# untitled.net
KiCad netlist of a schematic drawn in EAGLE
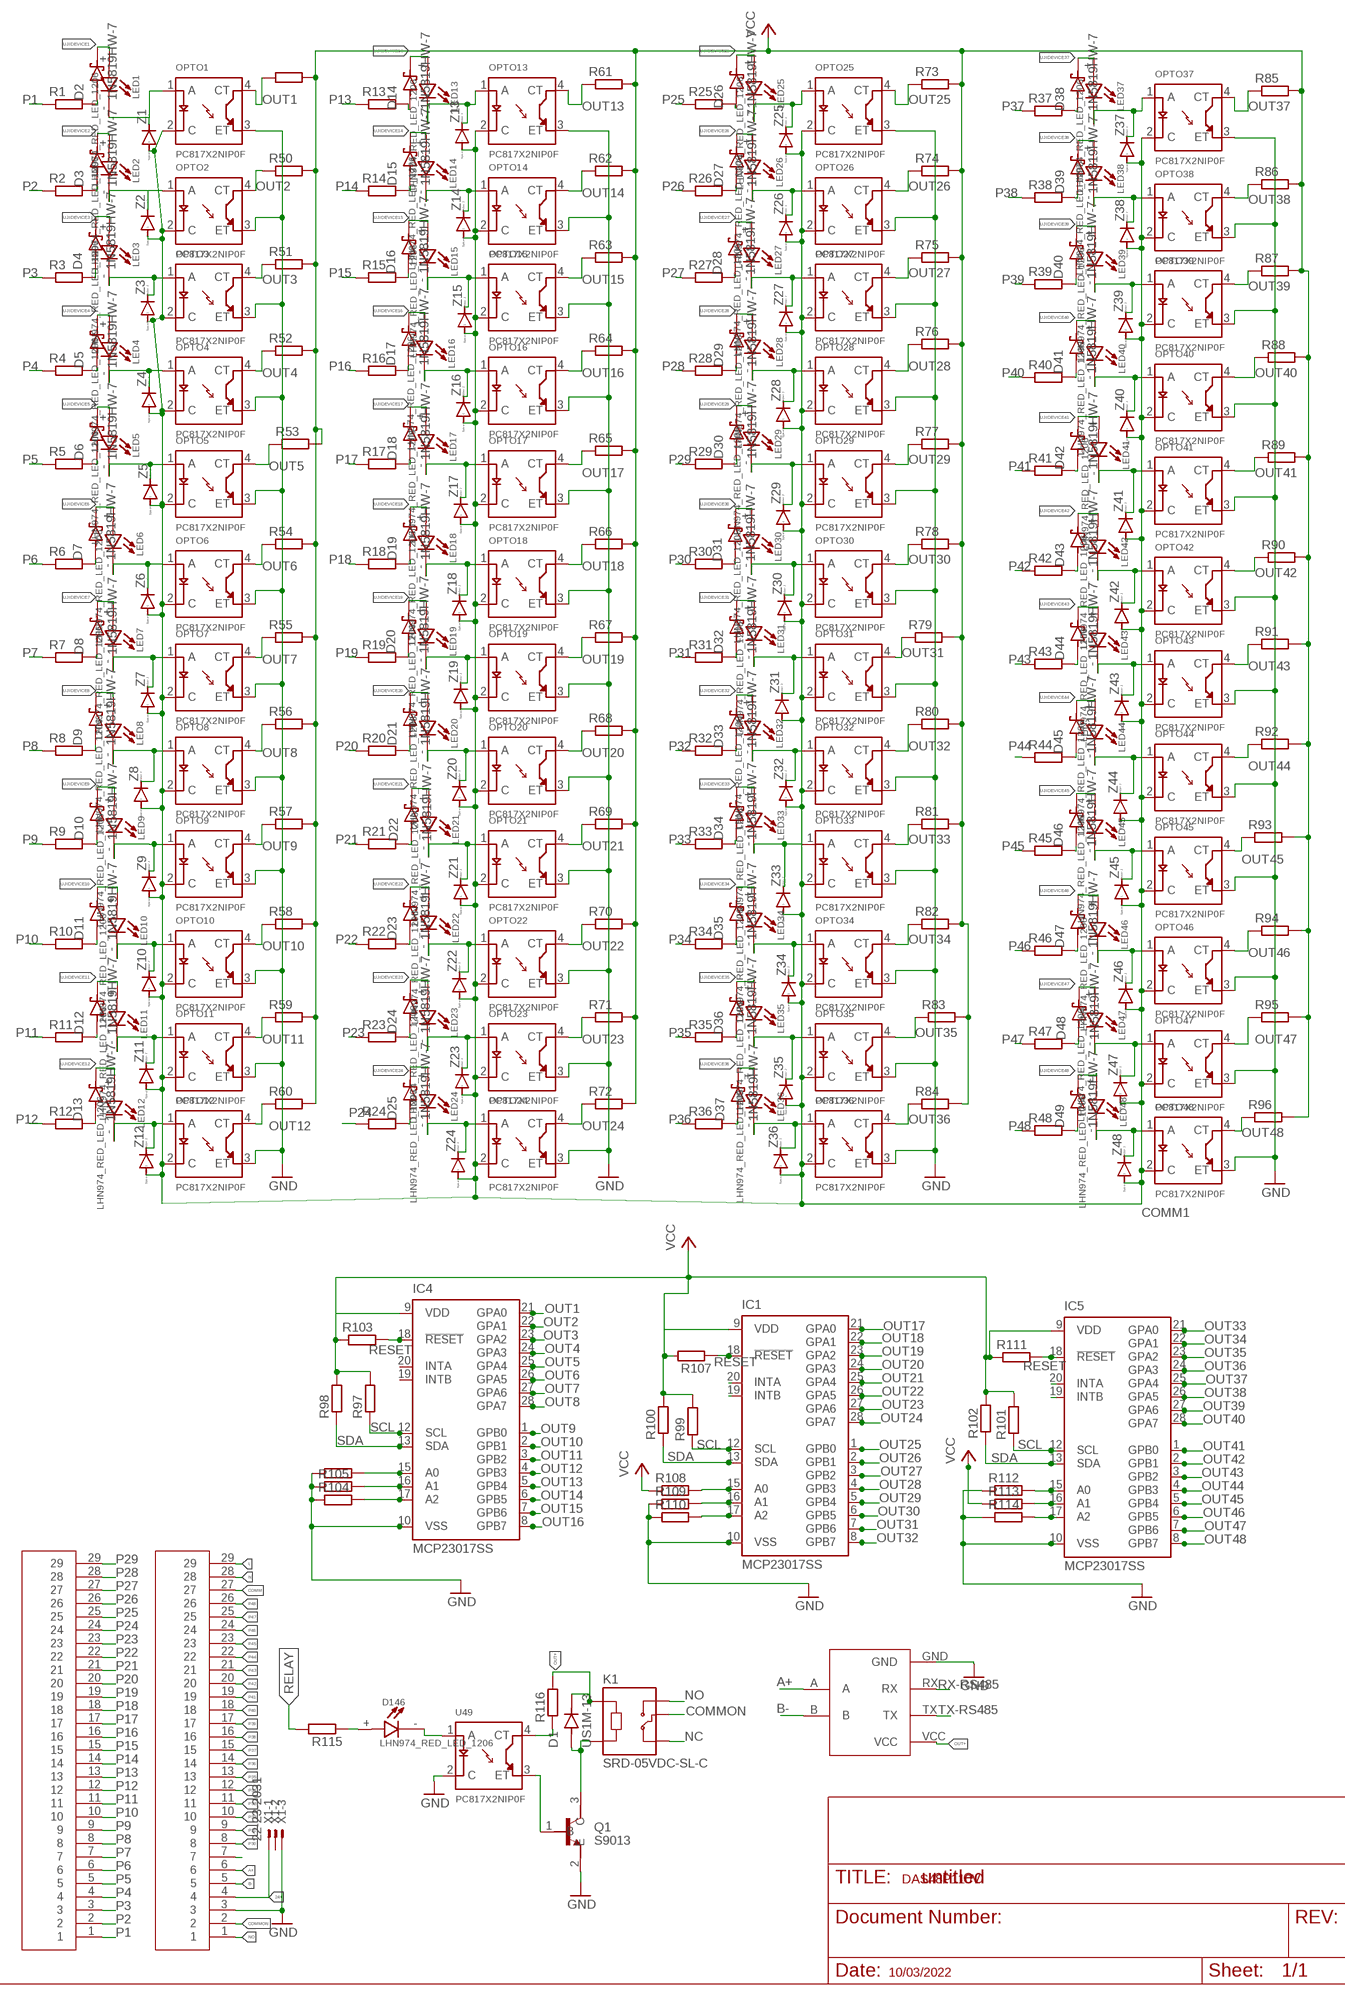
[diagram p0: schematic, sheet 1, part 1 of 2]
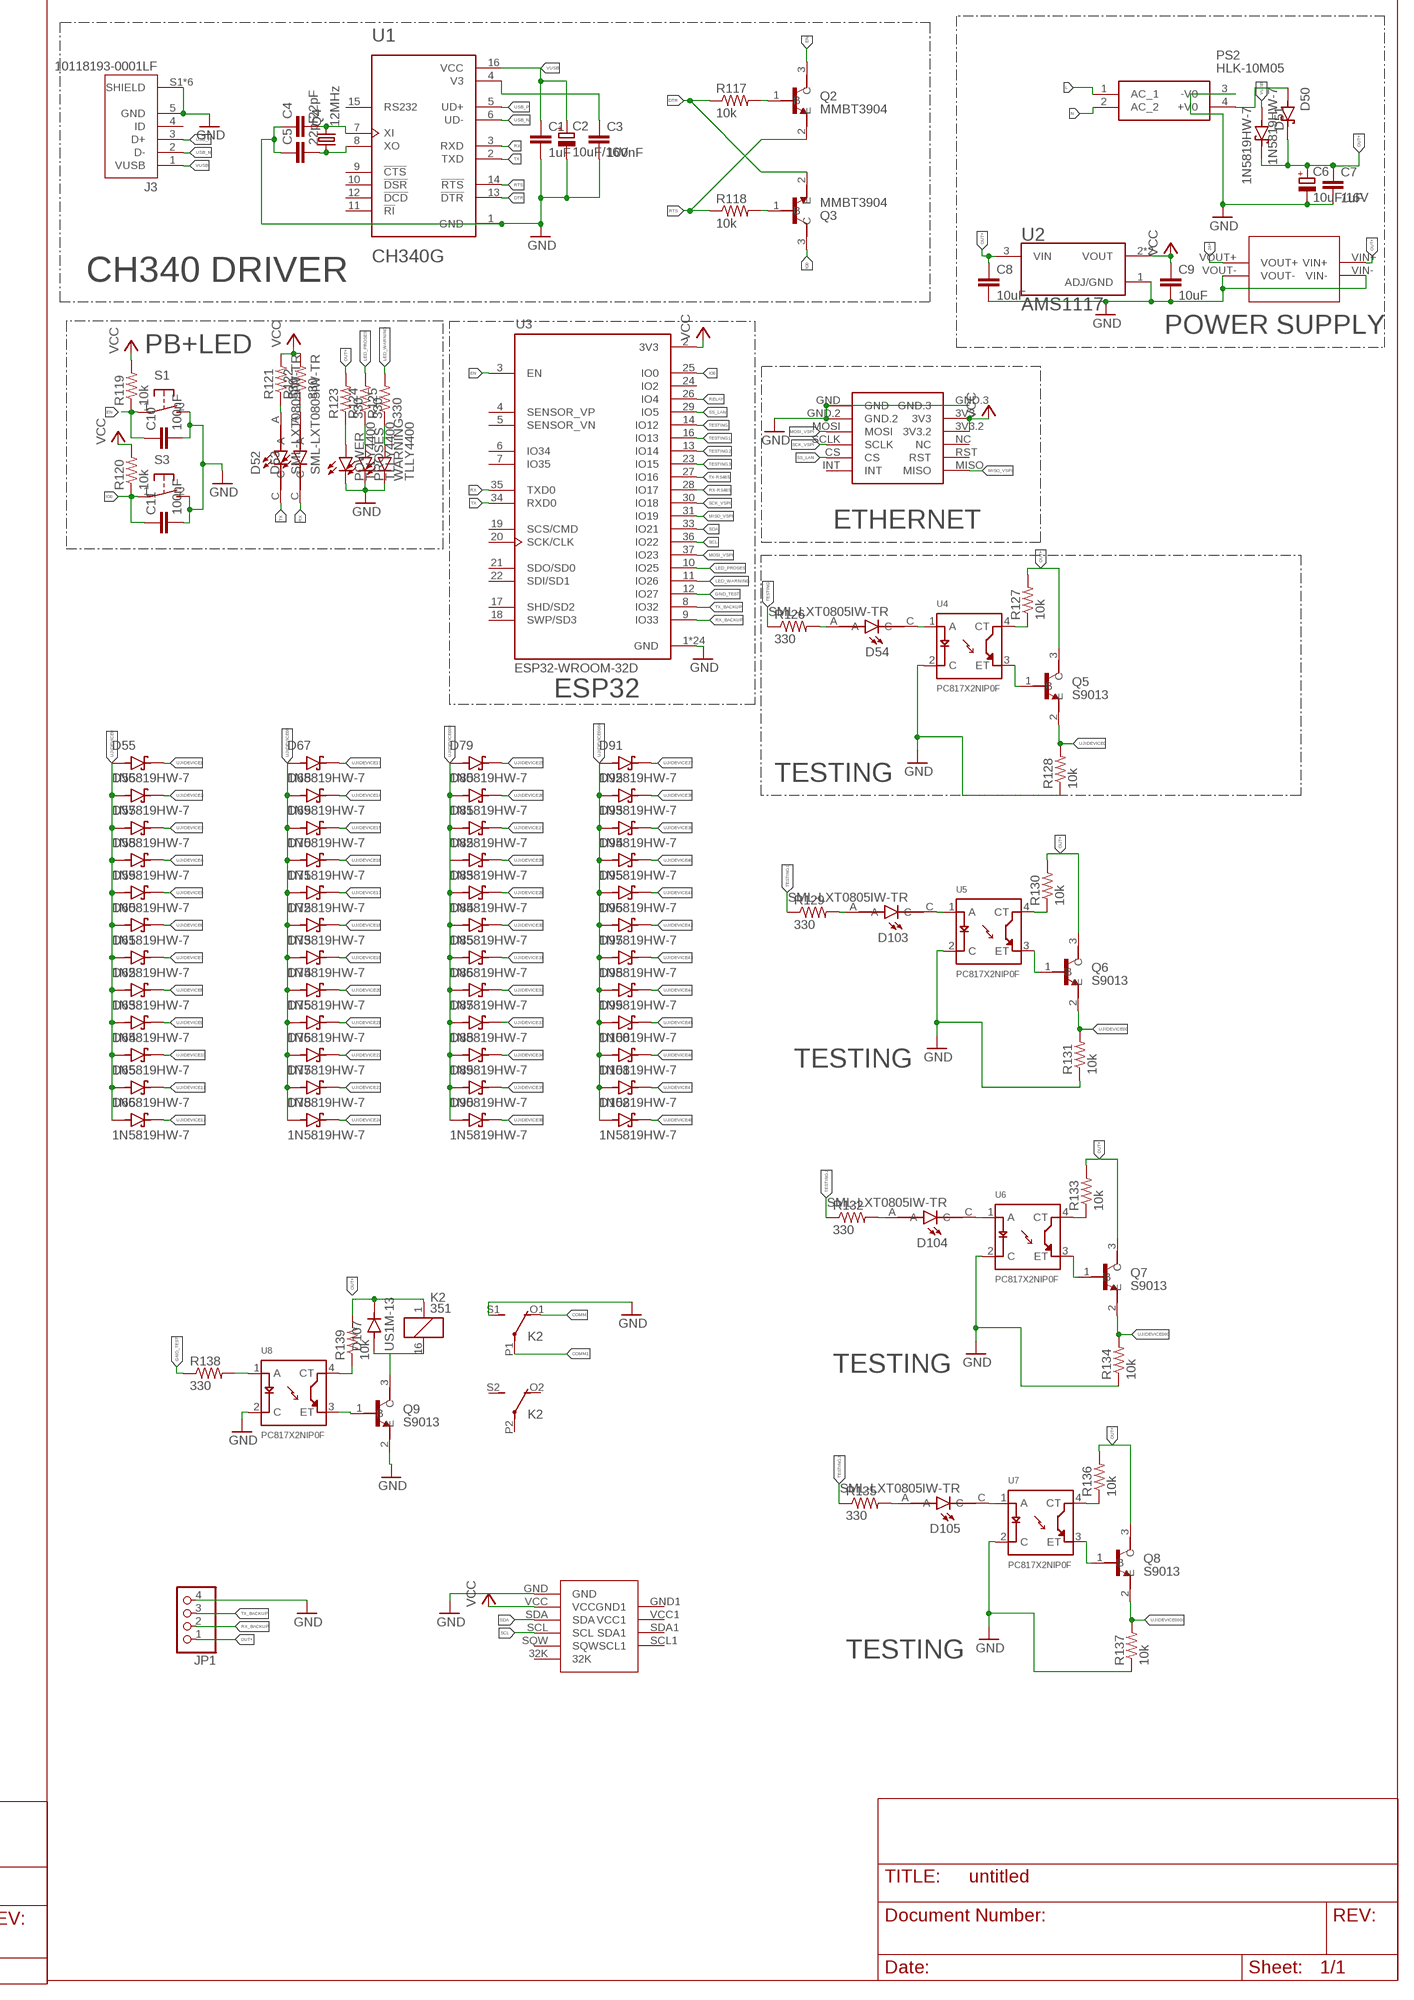
[diagram p1: schematic, sheet 1, part 2 of 2]

(export (version "E")
  (design (tool "Eeschema 10.0.6"))
  (components
    (comp (ref "C1")
      (value "1uF")
      (footprint "eagle-import:C0805K")
      (libsource (lib "eagle-import") (part "C-EUC0805K"))
    )
    (comp (ref "C2")
      (value "10uF/16V")
      (footprint "eagle-import:153CLV-0505")
      (libsource (lib "eagle-import") (part "CPOL-EU153CLV-0505"))
    )
    (comp (ref "C3")
      (value "100nF")
      (footprint "eagle-import:C0805K")
      (libsource (lib "eagle-import") (part "C-EUC0805K"))
    )
    (comp (ref "C4")
      (value "22pF")
      (footprint "eagle-import:C0805K")
      (libsource (lib "eagle-import") (part "C-EUC0805K"))
    )
    (comp (ref "C5")
      (value "22pF")
      (footprint "eagle-import:C0805K")
      (libsource (lib "eagle-import") (part "C-EUC0805K"))
    )
    (comp (ref "C6")
      (value "10uF/16V")
      (footprint "eagle-import:153CLV-0505")
      (libsource (lib "eagle-import") (part "CPOL-EU153CLV-0505"))
    )
    (comp (ref "C7")
      (value "1uF")
      (footprint "eagle-import:C0805K")
      (libsource (lib "eagle-import") (part "C-EUC0805K"))
    )
    (comp (ref "C8")
      (value "10uF")
      (footprint "eagle-import:C0805K")
      (libsource (lib "eagle-import") (part "C-EUC0805K"))
    )
    (comp (ref "C9")
      (value "10uF")
      (footprint "eagle-import:C0805K")
      (libsource (lib "eagle-import") (part "C-EUC0805K"))
    )
    (comp (ref "C10")
      (value "100nF")
      (footprint "eagle-import:C0805K")
      (libsource (lib "eagle-import") (part "C-EUC0805K"))
    )
    (comp (ref "C11")
      (value "100nF")
      (footprint "eagle-import:C0805K")
      (libsource (lib "eagle-import") (part "C-EUC0805K"))
    )
    (comp (ref "D1")
      (value "US1M-13")
      (footprint "eagle-import:DIOM5226X240N")
      (fields (field (name "MF") "Diodes Incorporated"))
      (libsource (lib "eagle-import") (part "US1M-13"))
    )
    (comp (ref "D2")
      (value "1N5819HW-7")
      (footprint "eagle-import:SOD3715X145N")
      (fields (field (name "MF") "Diodes Inc."))
      (libsource (lib "eagle-import") (part "1N5819HW-7"))
    )
    (comp (ref "D3")
      (value "1N5819HW-7")
      (footprint "eagle-import:SOD3715X145N")
      (fields (field (name "MF") "Diodes Inc."))
      (libsource (lib "eagle-import") (part "1N5819HW-7"))
    )
    (comp (ref "D4")
      (value "1N5819HW-7")
      (footprint "eagle-import:SOD3715X145N")
      (fields (field (name "MF") "Diodes Inc."))
      (libsource (lib "eagle-import") (part "1N5819HW-7"))
    )
    (comp (ref "D5")
      (value "1N5819HW-7")
      (footprint "eagle-import:SOD3715X145N")
      (fields (field (name "MF") "Diodes Inc."))
      (libsource (lib "eagle-import") (part "1N5819HW-7"))
    )
    (comp (ref "D6")
      (value "1N5819HW-7")
      (footprint "eagle-import:SOD3715X145N")
      (fields (field (name "MF") "Diodes Inc."))
      (libsource (lib "eagle-import") (part "1N5819HW-7"))
    )
    (comp (ref "D7")
      (value "1N5819HW-7")
      (footprint "eagle-import:SOD3715X145N")
      (fields (field (name "MF") "Diodes Inc."))
      (libsource (lib "eagle-import") (part "1N5819HW-7"))
    )
    (comp (ref "D8")
      (value "1N5819HW-7")
      (footprint "eagle-import:SOD3715X145N")
      (fields (field (name "MF") "Diodes Inc."))
      (libsource (lib "eagle-import") (part "1N5819HW-7"))
    )
    (comp (ref "D9")
      (value "1N5819HW-7")
      (footprint "eagle-import:SOD3715X145N")
      (fields (field (name "MF") "Diodes Inc."))
      (libsource (lib "eagle-import") (part "1N5819HW-7"))
    )
    (comp (ref "D10")
      (value "1N5819HW-7")
      (footprint "eagle-import:SOD3715X145N")
      (fields (field (name "MF") "Diodes Inc."))
      (libsource (lib "eagle-import") (part "1N5819HW-7"))
    )
    (comp (ref "D11")
      (value "1N5819HW-7")
      (footprint "eagle-import:SOD3715X145N")
      (fields (field (name "MF") "Diodes Inc."))
      (libsource (lib "eagle-import") (part "1N5819HW-7"))
    )
    (comp (ref "D12")
      (value "1N5819HW-7")
      (footprint "eagle-import:SOD3715X145N")
      (fields (field (name "MF") "Diodes Inc."))
      (libsource (lib "eagle-import") (part "1N5819HW-7"))
    )
    (comp (ref "D13")
      (value "1N5819HW-7")
      (footprint "eagle-import:SOD3715X145N")
      (fields (field (name "MF") "Diodes Inc."))
      (libsource (lib "eagle-import") (part "1N5819HW-7"))
    )
    (comp (ref "D14")
      (value "1N5819HW-7")
      (footprint "eagle-import:SOD3715X145N")
      (fields (field (name "MF") "Diodes Inc."))
      (libsource (lib "eagle-import") (part "1N5819HW-7"))
    )
    (comp (ref "D15")
      (value "1N5819HW-7")
      (footprint "eagle-import:SOD3715X145N")
      (fields (field (name "MF") "Diodes Inc."))
      (libsource (lib "eagle-import") (part "1N5819HW-7"))
    )
    (comp (ref "D16")
      (value "1N5819HW-7")
      (footprint "eagle-import:SOD3715X145N")
      (fields (field (name "MF") "Diodes Inc."))
      (libsource (lib "eagle-import") (part "1N5819HW-7"))
    )
    (comp (ref "D17")
      (value "1N5819HW-7")
      (footprint "eagle-import:SOD3715X145N")
      (fields (field (name "MF") "Diodes Inc."))
      (libsource (lib "eagle-import") (part "1N5819HW-7"))
    )
    (comp (ref "D18")
      (value "1N5819HW-7")
      (footprint "eagle-import:SOD3715X145N")
      (fields (field (name "MF") "Diodes Inc."))
      (libsource (lib "eagle-import") (part "1N5819HW-7"))
    )
    (comp (ref "D19")
      (value "1N5819HW-7")
      (footprint "eagle-import:SOD3715X145N")
      (fields (field (name "MF") "Diodes Inc."))
      (libsource (lib "eagle-import") (part "1N5819HW-7"))
    )
    (comp (ref "D20")
      (value "1N5819HW-7")
      (footprint "eagle-import:SOD3715X145N")
      (fields (field (name "MF") "Diodes Inc."))
      (libsource (lib "eagle-import") (part "1N5819HW-7"))
    )
    (comp (ref "D21")
      (value "1N5819HW-7")
      (footprint "eagle-import:SOD3715X145N")
      (fields (field (name "MF") "Diodes Inc."))
      (libsource (lib "eagle-import") (part "1N5819HW-7"))
    )
    (comp (ref "D22")
      (value "1N5819HW-7")
      (footprint "eagle-import:SOD3715X145N")
      (fields (field (name "MF") "Diodes Inc."))
      (libsource (lib "eagle-import") (part "1N5819HW-7"))
    )
    (comp (ref "D23")
      (value "1N5819HW-7")
      (footprint "eagle-import:SOD3715X145N")
      (fields (field (name "MF") "Diodes Inc."))
      (libsource (lib "eagle-import") (part "1N5819HW-7"))
    )
    (comp (ref "D24")
      (value "1N5819HW-7")
      (footprint "eagle-import:SOD3715X145N")
      (fields (field (name "MF") "Diodes Inc."))
      (libsource (lib "eagle-import") (part "1N5819HW-7"))
    )
    (comp (ref "D25")
      (value "1N5819HW-7")
      (footprint "eagle-import:SOD3715X145N")
      (fields (field (name "MF") "Diodes Inc."))
      (libsource (lib "eagle-import") (part "1N5819HW-7"))
    )
    (comp (ref "D26")
      (value "1N5819HW-7")
      (footprint "eagle-import:SOD3715X145N")
      (fields (field (name "MF") "Diodes Inc."))
      (libsource (lib "eagle-import") (part "1N5819HW-7"))
    )
    (comp (ref "D27")
      (value "1N5819HW-7")
      (footprint "eagle-import:SOD3715X145N")
      (fields (field (name "MF") "Diodes Inc."))
      (libsource (lib "eagle-import") (part "1N5819HW-7"))
    )
    (comp (ref "D28")
      (value "1N5819HW-7")
      (footprint "eagle-import:SOD3715X145N")
      (fields (field (name "MF") "Diodes Inc."))
      (libsource (lib "eagle-import") (part "1N5819HW-7"))
    )
    (comp (ref "D29")
      (value "1N5819HW-7")
      (footprint "eagle-import:SOD3715X145N")
      (fields (field (name "MF") "Diodes Inc."))
      (libsource (lib "eagle-import") (part "1N5819HW-7"))
    )
    (comp (ref "D30")
      (value "1N5819HW-7")
      (footprint "eagle-import:SOD3715X145N")
      (fields (field (name "MF") "Diodes Inc."))
      (libsource (lib "eagle-import") (part "1N5819HW-7"))
    )
    (comp (ref "D31")
      (value "1N5819HW-7")
      (footprint "eagle-import:SOD3715X145N")
      (fields (field (name "MF") "Diodes Inc."))
      (libsource (lib "eagle-import") (part "1N5819HW-7"))
    )
    (comp (ref "D32")
      (value "1N5819HW-7")
      (footprint "eagle-import:SOD3715X145N")
      (fields (field (name "MF") "Diodes Inc."))
      (libsource (lib "eagle-import") (part "1N5819HW-7"))
    )
    (comp (ref "D33")
      (value "1N5819HW-7")
      (footprint "eagle-import:SOD3715X145N")
      (fields (field (name "MF") "Diodes Inc."))
      (libsource (lib "eagle-import") (part "1N5819HW-7"))
    )
    (comp (ref "D34")
      (value "1N5819HW-7")
      (footprint "eagle-import:SOD3715X145N")
      (fields (field (name "MF") "Diodes Inc."))
      (libsource (lib "eagle-import") (part "1N5819HW-7"))
    )
    (comp (ref "D35")
      (value "1N5819HW-7")
      (footprint "eagle-import:SOD3715X145N")
      (fields (field (name "MF") "Diodes Inc."))
      (libsource (lib "eagle-import") (part "1N5819HW-7"))
    )
    (comp (ref "D36")
      (value "1N5819HW-7")
      (footprint "eagle-import:SOD3715X145N")
      (fields (field (name "MF") "Diodes Inc."))
      (libsource (lib "eagle-import") (part "1N5819HW-7"))
    )
    (comp (ref "D37")
      (value "1N5819HW-7")
      (footprint "eagle-import:SOD3715X145N")
      (fields (field (name "MF") "Diodes Inc."))
      (libsource (lib "eagle-import") (part "1N5819HW-7"))
    )
    (comp (ref "D38")
      (value "1N5819HW-7")
      (footprint "eagle-import:SOD3715X145N")
      (fields (field (name "MF") "Diodes Inc."))
      (libsource (lib "eagle-import") (part "1N5819HW-7"))
    )
    (comp (ref "D39")
      (value "1N5819HW-7")
      (footprint "eagle-import:SOD3715X145N")
      (fields (field (name "MF") "Diodes Inc."))
      (libsource (lib "eagle-import") (part "1N5819HW-7"))
    )
    (comp (ref "D40")
      (value "1N5819HW-7")
      (footprint "eagle-import:SOD3715X145N")
      (fields (field (name "MF") "Diodes Inc."))
      (libsource (lib "eagle-import") (part "1N5819HW-7"))
    )
    (comp (ref "D41")
      (value "1N5819HW-7")
      (footprint "eagle-import:SOD3715X145N")
      (fields (field (name "MF") "Diodes Inc."))
      (libsource (lib "eagle-import") (part "1N5819HW-7"))
    )
    (comp (ref "D42")
      (value "1N5819HW-7")
      (footprint "eagle-import:SOD3715X145N")
      (fields (field (name "MF") "Diodes Inc."))
      (libsource (lib "eagle-import") (part "1N5819HW-7"))
    )
    (comp (ref "D43")
      (value "1N5819HW-7")
      (footprint "eagle-import:SOD3715X145N")
      (fields (field (name "MF") "Diodes Inc."))
      (libsource (lib "eagle-import") (part "1N5819HW-7"))
    )
    (comp (ref "D44")
      (value "1N5819HW-7")
      (footprint "eagle-import:SOD3715X145N")
      (fields (field (name "MF") "Diodes Inc."))
      (libsource (lib "eagle-import") (part "1N5819HW-7"))
    )
    (comp (ref "D45")
      (value "1N5819HW-7")
      (footprint "eagle-import:SOD3715X145N")
      (fields (field (name "MF") "Diodes Inc."))
      (libsource (lib "eagle-import") (part "1N5819HW-7"))
    )
    (comp (ref "D46")
      (value "1N5819HW-7")
      (footprint "eagle-import:SOD3715X145N")
      (fields (field (name "MF") "Diodes Inc."))
      (libsource (lib "eagle-import") (part "1N5819HW-7"))
    )
    (comp (ref "D47")
      (value "1N5819HW-7")
      (footprint "eagle-import:SOD3715X145N")
      (fields (field (name "MF") "Diodes Inc."))
      (libsource (lib "eagle-import") (part "1N5819HW-7"))
    )
    (comp (ref "D48")
      (value "1N5819HW-7")
      (footprint "eagle-import:SOD3715X145N")
      (fields (field (name "MF") "Diodes Inc."))
      (libsource (lib "eagle-import") (part "1N5819HW-7"))
    )
    (comp (ref "D49")
      (value "1N5819HW-7")
      (footprint "eagle-import:SOD3715X145N")
      (fields (field (name "MF") "Diodes Inc."))
      (libsource (lib "eagle-import") (part "1N5819HW-7"))
    )
    (comp (ref "D50")
      (value "1N5819HW-7")
      (footprint "eagle-import:SOD3715X145N")
      (fields (field (name "MF") "Diodes Inc."))
      (libsource (lib "eagle-import") (part "1N5819HW-7"))
    )
    (comp (ref "D51")
      (value "1N5819HW-7")
      (footprint "eagle-import:SOD3715X145N")
      (fields (field (name "MF") "Diodes Inc."))
      (libsource (lib "eagle-import") (part "1N5819HW-7"))
    )
    (comp (ref "D52")
      (value "SML-LXT0805IW-TR")
      (footprint "eagle-import:LEDC2012X120N")
      (fields (field (name "MF") "Lumex Opto/Components"))
      (libsource (lib "eagle-import") (part "SML-LXT0805IW-TR"))
    )
    (comp (ref "D53")
      (value "SML-LXT0805IW-TR")
      (footprint "eagle-import:LEDC2012X120N")
      (fields (field (name "MF") "Lumex Opto/Components"))
      (libsource (lib "eagle-import") (part "SML-LXT0805IW-TR"))
    )
    (comp (ref "D54")
      (value "SML-LXT0805IW-TR")
      (footprint "eagle-import:LEDC2012X120N")
      (fields (field (name "MF") "Lumex Opto/Components"))
      (libsource (lib "eagle-import") (part "SML-LXT0805IW-TR"))
    )
    (comp (ref "D55")
      (value "1N5819HW-7")
      (footprint "eagle-import:SOD3715X145N")
      (fields (field (name "MF") "Diodes Inc."))
      (libsource (lib "eagle-import") (part "1N5819HW-7"))
    )
    (comp (ref "D56")
      (value "1N5819HW-7")
      (footprint "eagle-import:SOD3715X145N")
      (fields (field (name "MF") "Diodes Inc."))
      (libsource (lib "eagle-import") (part "1N5819HW-7"))
    )
    (comp (ref "D57")
      (value "1N5819HW-7")
      (footprint "eagle-import:SOD3715X145N")
      (fields (field (name "MF") "Diodes Inc."))
      (libsource (lib "eagle-import") (part "1N5819HW-7"))
    )
    (comp (ref "D58")
      (value "1N5819HW-7")
      (footprint "eagle-import:SOD3715X145N")
      (fields (field (name "MF") "Diodes Inc."))
      (libsource (lib "eagle-import") (part "1N5819HW-7"))
    )
    (comp (ref "D59")
      (value "1N5819HW-7")
      (footprint "eagle-import:SOD3715X145N")
      (fields (field (name "MF") "Diodes Inc."))
      (libsource (lib "eagle-import") (part "1N5819HW-7"))
    )
    (comp (ref "D60")
      (value "1N5819HW-7")
      (footprint "eagle-import:SOD3715X145N")
      (fields (field (name "MF") "Diodes Inc."))
      (libsource (lib "eagle-import") (part "1N5819HW-7"))
    )
    (comp (ref "D61")
      (value "1N5819HW-7")
      (footprint "eagle-import:SOD3715X145N")
      (fields (field (name "MF") "Diodes Inc."))
      (libsource (lib "eagle-import") (part "1N5819HW-7"))
    )
    (comp (ref "D62")
      (value "1N5819HW-7")
      (footprint "eagle-import:SOD3715X145N")
      (fields (field (name "MF") "Diodes Inc."))
      (libsource (lib "eagle-import") (part "1N5819HW-7"))
    )
    (comp (ref "D63")
      (value "1N5819HW-7")
      (footprint "eagle-import:SOD3715X145N")
      (fields (field (name "MF") "Diodes Inc."))
      (libsource (lib "eagle-import") (part "1N5819HW-7"))
    )
    (comp (ref "D64")
      (value "1N5819HW-7")
      (footprint "eagle-import:SOD3715X145N")
      (fields (field (name "MF") "Diodes Inc."))
      (libsource (lib "eagle-import") (part "1N5819HW-7"))
    )
    (comp (ref "D65")
      (value "1N5819HW-7")
      (footprint "eagle-import:SOD3715X145N")
      (fields (field (name "MF") "Diodes Inc."))
      (libsource (lib "eagle-import") (part "1N5819HW-7"))
    )
    (comp (ref "D66")
      (value "1N5819HW-7")
      (footprint "eagle-import:SOD3715X145N")
      (fields (field (name "MF") "Diodes Inc."))
      (libsource (lib "eagle-import") (part "1N5819HW-7"))
    )
    (comp (ref "D67")
      (value "1N5819HW-7")
      (footprint "eagle-import:SOD3715X145N")
      (fields (field (name "MF") "Diodes Inc."))
      (libsource (lib "eagle-import") (part "1N5819HW-7"))
    )
    (comp (ref "D68")
      (value "1N5819HW-7")
      (footprint "eagle-import:SOD3715X145N")
      (fields (field (name "MF") "Diodes Inc."))
      (libsource (lib "eagle-import") (part "1N5819HW-7"))
    )
    (comp (ref "D69")
      (value "1N5819HW-7")
      (footprint "eagle-import:SOD3715X145N")
      (fields (field (name "MF") "Diodes Inc."))
      (libsource (lib "eagle-import") (part "1N5819HW-7"))
    )
    (comp (ref "D70")
      (value "1N5819HW-7")
      (footprint "eagle-import:SOD3715X145N")
      (fields (field (name "MF") "Diodes Inc."))
      (libsource (lib "eagle-import") (part "1N5819HW-7"))
    )
    (comp (ref "D71")
      (value "1N5819HW-7")
      (footprint "eagle-import:SOD3715X145N")
      (fields (field (name "MF") "Diodes Inc."))
      (libsource (lib "eagle-import") (part "1N5819HW-7"))
    )
    (comp (ref "D72")
      (value "1N5819HW-7")
      (footprint "eagle-import:SOD3715X145N")
      (fields (field (name "MF") "Diodes Inc."))
      (libsource (lib "eagle-import") (part "1N5819HW-7"))
    )
    (comp (ref "D73")
      (value "1N5819HW-7")
      (footprint "eagle-import:SOD3715X145N")
      (fields (field (name "MF") "Diodes Inc."))
      (libsource (lib "eagle-import") (part "1N5819HW-7"))
    )
    (comp (ref "D74")
      (value "1N5819HW-7")
      (footprint "eagle-import:SOD3715X145N")
      (fields (field (name "MF") "Diodes Inc."))
      (libsource (lib "eagle-import") (part "1N5819HW-7"))
    )
    (comp (ref "D75")
      (value "1N5819HW-7")
      (footprint "eagle-import:SOD3715X145N")
      (fields (field (name "MF") "Diodes Inc."))
      (libsource (lib "eagle-import") (part "1N5819HW-7"))
    )
    (comp (ref "D76")
      (value "1N5819HW-7")
      (footprint "eagle-import:SOD3715X145N")
      (fields (field (name "MF") "Diodes Inc."))
      (libsource (lib "eagle-import") (part "1N5819HW-7"))
    )
    (comp (ref "D77")
      (value "1N5819HW-7")
      (footprint "eagle-import:SOD3715X145N")
      (fields (field (name "MF") "Diodes Inc."))
      (libsource (lib "eagle-import") (part "1N5819HW-7"))
    )
    (comp (ref "D78")
      (value "1N5819HW-7")
      (footprint "eagle-import:SOD3715X145N")
      (fields (field (name "MF") "Diodes Inc."))
      (libsource (lib "eagle-import") (part "1N5819HW-7"))
    )
    (comp (ref "D79")
      (value "1N5819HW-7")
      (footprint "eagle-import:SOD3715X145N")
      (fields (field (name "MF") "Diodes Inc."))
      (libsource (lib "eagle-import") (part "1N5819HW-7"))
    )
    (comp (ref "D80")
      (value "1N5819HW-7")
      (footprint "eagle-import:SOD3715X145N")
      (fields (field (name "MF") "Diodes Inc."))
      (libsource (lib "eagle-import") (part "1N5819HW-7"))
    )
    (comp (ref "D81")
      (value "1N5819HW-7")
      (footprint "eagle-import:SOD3715X145N")
      (fields (field (name "MF") "Diodes Inc."))
      (libsource (lib "eagle-import") (part "1N5819HW-7"))
    )
    (comp (ref "D82")
      (value "1N5819HW-7")
      (footprint "eagle-import:SOD3715X145N")
      (fields (field (name "MF") "Diodes Inc."))
      (libsource (lib "eagle-import") (part "1N5819HW-7"))
    )
    (comp (ref "D83")
      (value "1N5819HW-7")
      (footprint "eagle-import:SOD3715X145N")
      (fields (field (name "MF") "Diodes Inc."))
      (libsource (lib "eagle-import") (part "1N5819HW-7"))
    )
    (comp (ref "D84")
      (value "1N5819HW-7")
      (footprint "eagle-import:SOD3715X145N")
      (fields (field (name "MF") "Diodes Inc."))
      (libsource (lib "eagle-import") (part "1N5819HW-7"))
    )
    (comp (ref "D85")
      (value "1N5819HW-7")
      (footprint "eagle-import:SOD3715X145N")
      (fields (field (name "MF") "Diodes Inc."))
      (libsource (lib "eagle-import") (part "1N5819HW-7"))
    )
    (comp (ref "D86")
      (value "1N5819HW-7")
      (footprint "eagle-import:SOD3715X145N")
      (fields (field (name "MF") "Diodes Inc."))
      (libsource (lib "eagle-import") (part "1N5819HW-7"))
    )
    (comp (ref "D87")
      (value "1N5819HW-7")
      (footprint "eagle-import:SOD3715X145N")
      (fields (field (name "MF") "Diodes Inc."))
      (libsource (lib "eagle-import") (part "1N5819HW-7"))
    )
    (comp (ref "D88")
      (value "1N5819HW-7")
      (footprint "eagle-import:SOD3715X145N")
      (fields (field (name "MF") "Diodes Inc."))
      (libsource (lib "eagle-import") (part "1N5819HW-7"))
    )
    (comp (ref "D89")
      (value "1N5819HW-7")
      (footprint "eagle-import:SOD3715X145N")
      (fields (field (name "MF") "Diodes Inc."))
      (libsource (lib "eagle-import") (part "1N5819HW-7"))
    )
    (comp (ref "D90")
      (value "1N5819HW-7")
      (footprint "eagle-import:SOD3715X145N")
      (fields (field (name "MF") "Diodes Inc."))
      (libsource (lib "eagle-import") (part "1N5819HW-7"))
    )
    (comp (ref "D91")
      (value "1N5819HW-7")
      (footprint "eagle-import:SOD3715X145N")
      (fields (field (name "MF") "Diodes Inc."))
      (libsource (lib "eagle-import") (part "1N5819HW-7"))
    )
    (comp (ref "D92")
      (value "1N5819HW-7")
      (footprint "eagle-import:SOD3715X145N")
      (fields (field (name "MF") "Diodes Inc."))
      (libsource (lib "eagle-import") (part "1N5819HW-7"))
    )
    (comp (ref "D93")
      (value "1N5819HW-7")
      (footprint "eagle-import:SOD3715X145N")
      (fields (field (name "MF") "Diodes Inc."))
      (libsource (lib "eagle-import") (part "1N5819HW-7"))
    )
    (comp (ref "D94")
      (value "1N5819HW-7")
      (footprint "eagle-import:SOD3715X145N")
      (fields (field (name "MF") "Diodes Inc."))
      (libsource (lib "eagle-import") (part "1N5819HW-7"))
    )
    (comp (ref "D95")
      (value "1N5819HW-7")
      (footprint "eagle-import:SOD3715X145N")
      (fields (field (name "MF") "Diodes Inc."))
      (libsource (lib "eagle-import") (part "1N5819HW-7"))
    )
    (comp (ref "D96")
      (value "1N5819HW-7")
      (footprint "eagle-import:SOD3715X145N")
      (fields (field (name "MF") "Diodes Inc."))
      (libsource (lib "eagle-import") (part "1N5819HW-7"))
    )
    (comp (ref "D97")
      (value "1N5819HW-7")
      (footprint "eagle-import:SOD3715X145N")
      (fields (field (name "MF") "Diodes Inc."))
      (libsource (lib "eagle-import") (part "1N5819HW-7"))
    )
    (comp (ref "D98")
      (value "1N5819HW-7")
      (footprint "eagle-import:SOD3715X145N")
      (fields (field (name "MF") "Diodes Inc."))
      (libsource (lib "eagle-import") (part "1N5819HW-7"))
    )
    (comp (ref "D99")
      (value "1N5819HW-7")
      (footprint "eagle-import:SOD3715X145N")
      (fields (field (name "MF") "Diodes Inc."))
      (libsource (lib "eagle-import") (part "1N5819HW-7"))
    )
    (comp (ref "D100")
      (value "1N5819HW-7")
      (footprint "eagle-import:SOD3715X145N")
      (fields (field (name "MF") "Diodes Inc."))
      (libsource (lib "eagle-import") (part "1N5819HW-7"))
    )
    (comp (ref "D101")
      (value "1N5819HW-7")
      (footprint "eagle-import:SOD3715X145N")
      (fields (field (name "MF") "Diodes Inc."))
      (libsource (lib "eagle-import") (part "1N5819HW-7"))
    )
    (comp (ref "D102")
      (value "1N5819HW-7")
      (footprint "eagle-import:SOD3715X145N")
      (fields (field (name "MF") "Diodes Inc."))
      (libsource (lib "eagle-import") (part "1N5819HW-7"))
    )
    (comp (ref "D103")
      (value "SML-LXT0805IW-TR")
      (footprint "eagle-import:LEDC2012X120N")
      (fields (field (name "MF") "Lumex Opto/Components"))
      (libsource (lib "eagle-import") (part "SML-LXT0805IW-TR"))
    )
    (comp (ref "D104")
      (value "SML-LXT0805IW-TR")
      (footprint "eagle-import:LEDC2012X120N")
      (fields (field (name "MF") "Lumex Opto/Components"))
      (libsource (lib "eagle-import") (part "SML-LXT0805IW-TR"))
    )
    (comp (ref "D105")
      (value "SML-LXT0805IW-TR")
      (footprint "eagle-import:LEDC2012X120N")
      (fields (field (name "MF") "Lumex Opto/Components"))
      (libsource (lib "eagle-import") (part "SML-LXT0805IW-TR"))
    )
    (comp (ref "D107")
      (value "US1M-13")
      (footprint "eagle-import:DIOM5226X240N")
      (fields (field (name "MF") "Diodes Incorporated"))
      (libsource (lib "eagle-import") (part "US1M-13"))
    )
    (comp (ref "D146")
      (value "LHN974_RED_LED_1206")
      (footprint "eagle-import:LEDC3216X120N")
      (fields (field (name "MF") "Osram") (field (name "MP") "LHN974 RED LED 1206"))
      (libsource (lib "eagle-import") (part "LHN974_RED_LED_1206"))
    )
    (comp (ref "HEADER-29P1")
      (value "HEADER-29P")
      (footprint "eagle-import:HEADER-29P")
      (libsource (lib "eagle-import") (part "HEADER-29P"))
    )
    (comp (ref "HEADER-29P2")
      (value "HEADER-29P")
      (footprint "eagle-import:HEADER-29P")
      (libsource (lib "eagle-import") (part "HEADER-29P"))
    )
    (comp (ref "IC1")
      (value "MCP23017SS")
      (footprint "eagle-import:SSOP28DB")
      (libsource (lib "eagle-import") (part "MCP23017SS"))
    )
    (comp (ref "IC4")
      (value "MCP23017SS")
      (footprint "eagle-import:SSOP28DB")
      (libsource (lib "eagle-import") (part "MCP23017SS"))
    )
    (comp (ref "IC5")
      (value "MCP23017SS")
      (footprint "eagle-import:SSOP28DB")
      (libsource (lib "eagle-import") (part "MCP23017SS"))
    )
    (comp (ref "J3")
      (value "10118193-0001LF")
      (footprint "eagle-import:FCI_10118193-0001LF")
      (fields (field (name "MF") "FCI"))
      (libsource (lib "eagle-import") (part "10118193-0001LF"))
    )
    (comp (ref "JP1")
      (value "PINHD-1X4")
      (footprint "eagle-import:1X04")
      (libsource (lib "eagle-import") (part "PINHD-1X4"))
    )
    (comp (ref "K1")
      (value "SRD-05VDC-SL-C")
      (footprint "eagle-import:RELAY_SRD-05VDC-SL-C")
      (fields (field (name "MF") "Songle Relay"))
      (libsource (lib "eagle-import") (part "SRD-05VDC-SL-C"))
    )
    (comp (ref "K2")
      (value "351")
      (footprint "eagle-import:351")
      (libsource (lib "eagle-import") (part "351"))
    )
    (comp (ref "LED1")
      (value "LHN974_RED_LED_1206")
      (footprint "eagle-import:LEDC3216X120N")
      (fields (field (name "MF") "Osram") (field (name "MP") "LHN974 RED LED 1206"))
      (libsource (lib "eagle-import") (part "LHN974_RED_LED_1206"))
    )
    (comp (ref "LED2")
      (value "LHN974_RED_LED_1206")
      (footprint "eagle-import:LEDC3216X120N")
      (fields (field (name "MF") "Osram") (field (name "MP") "LHN974 RED LED 1206"))
      (libsource (lib "eagle-import") (part "LHN974_RED_LED_1206"))
    )
    (comp (ref "LED3")
      (value "LHN974_RED_LED_1206")
      (footprint "eagle-import:LEDC3216X120N")
      (fields (field (name "MF") "Osram") (field (name "MP") "LHN974 RED LED 1206"))
      (libsource (lib "eagle-import") (part "LHN974_RED_LED_1206"))
    )
    (comp (ref "LED4")
      (value "LHN974_RED_LED_1206")
      (footprint "eagle-import:LEDC3216X120N")
      (fields (field (name "MF") "Osram") (field (name "MP") "LHN974 RED LED 1206"))
      (libsource (lib "eagle-import") (part "LHN974_RED_LED_1206"))
    )
    (comp (ref "LED5")
      (value "LHN974_RED_LED_1206")
      (footprint "eagle-import:LEDC3216X120N")
      (fields (field (name "MF") "Osram") (field (name "MP") "LHN974 RED LED 1206"))
      (libsource (lib "eagle-import") (part "LHN974_RED_LED_1206"))
    )
    (comp (ref "LED6")
      (value "LHN974_RED_LED_1206")
      (footprint "eagle-import:LEDC3216X120N")
      (fields (field (name "MF") "Osram") (field (name "MP") "LHN974 RED LED 1206"))
      (libsource (lib "eagle-import") (part "LHN974_RED_LED_1206"))
    )
    (comp (ref "LED7")
      (value "LHN974_RED_LED_1206")
      (footprint "eagle-import:LEDC3216X120N")
      (fields (field (name "MF") "Osram") (field (name "MP") "LHN974 RED LED 1206"))
      (libsource (lib "eagle-import") (part "LHN974_RED_LED_1206"))
    )
    (comp (ref "LED8")
      (value "LHN974_RED_LED_1206")
      (footprint "eagle-import:LEDC3216X120N")
      (fields (field (name "MF") "Osram") (field (name "MP") "LHN974 RED LED 1206"))
      (libsource (lib "eagle-import") (part "LHN974_RED_LED_1206"))
    )
    (comp (ref "LED9")
      (value "LHN974_RED_LED_1206")
      (footprint "eagle-import:LEDC3216X120N")
      (fields (field (name "MF") "Osram") (field (name "MP") "LHN974 RED LED 1206"))
      (libsource (lib "eagle-import") (part "LHN974_RED_LED_1206"))
    )
    (comp (ref "LED10")
      (value "LHN974_RED_LED_1206")
      (footprint "eagle-import:LEDC3216X120N")
      (fields (field (name "MF") "Osram") (field (name "MP") "LHN974 RED LED 1206"))
      (libsource (lib "eagle-import") (part "LHN974_RED_LED_1206"))
    )
    (comp (ref "LED11")
      (value "LHN974_RED_LED_1206")
      (footprint "eagle-import:LEDC3216X120N")
      (fields (field (name "MF") "Osram") (field (name "MP") "LHN974 RED LED 1206"))
      (libsource (lib "eagle-import") (part "LHN974_RED_LED_1206"))
    )
    (comp (ref "LED12")
      (value "LHN974_RED_LED_1206")
      (footprint "eagle-import:LEDC3216X120N")
      (fields (field (name "MF") "Osram") (field (name "MP") "LHN974 RED LED 1206"))
      (libsource (lib "eagle-import") (part "LHN974_RED_LED_1206"))
    )
    (comp (ref "LED13")
      (value "LHN974_RED_LED_1206")
      (footprint "eagle-import:LEDC3216X120N")
      (fields (field (name "MF") "Osram") (field (name "MP") "LHN974 RED LED 1206"))
      (libsource (lib "eagle-import") (part "LHN974_RED_LED_1206"))
    )
    (comp (ref "LED14")
      (value "LHN974_RED_LED_1206")
      (footprint "eagle-import:LEDC3216X120N")
      (fields (field (name "MF") "Osram") (field (name "MP") "LHN974 RED LED 1206"))
      (libsource (lib "eagle-import") (part "LHN974_RED_LED_1206"))
    )
    (comp (ref "LED15")
      (value "LHN974_RED_LED_1206")
      (footprint "eagle-import:LEDC3216X120N")
      (fields (field (name "MF") "Osram") (field (name "MP") "LHN974 RED LED 1206"))
      (libsource (lib "eagle-import") (part "LHN974_RED_LED_1206"))
    )
    (comp (ref "LED16")
      (value "LHN974_RED_LED_1206")
      (footprint "eagle-import:LEDC3216X120N")
      (fields (field (name "MF") "Osram") (field (name "MP") "LHN974 RED LED 1206"))
      (libsource (lib "eagle-import") (part "LHN974_RED_LED_1206"))
    )
    (comp (ref "LED17")
      (value "LHN974_RED_LED_1206")
      (footprint "eagle-import:LEDC3216X120N")
      (fields (field (name "MF") "Osram") (field (name "MP") "LHN974 RED LED 1206"))
      (libsource (lib "eagle-import") (part "LHN974_RED_LED_1206"))
    )
    (comp (ref "LED18")
      (value "LHN974_RED_LED_1206")
      (footprint "eagle-import:LEDC3216X120N")
      (fields (field (name "MF") "Osram") (field (name "MP") "LHN974 RED LED 1206"))
      (libsource (lib "eagle-import") (part "LHN974_RED_LED_1206"))
    )
    (comp (ref "LED19")
      (value "LHN974_RED_LED_1206")
      (footprint "eagle-import:LEDC3216X120N")
      (fields (field (name "MF") "Osram") (field (name "MP") "LHN974 RED LED 1206"))
      (libsource (lib "eagle-import") (part "LHN974_RED_LED_1206"))
    )
    (comp (ref "LED20")
      (value "LHN974_RED_LED_1206")
      (footprint "eagle-import:LEDC3216X120N")
      (fields (field (name "MF") "Osram") (field (name "MP") "LHN974 RED LED 1206"))
      (libsource (lib "eagle-import") (part "LHN974_RED_LED_1206"))
    )
    (comp (ref "LED21")
      (value "LHN974_RED_LED_1206")
      (footprint "eagle-import:LEDC3216X120N")
      (fields (field (name "MF") "Osram") (field (name "MP") "LHN974 RED LED 1206"))
      (libsource (lib "eagle-import") (part "LHN974_RED_LED_1206"))
    )
    (comp (ref "LED22")
      (value "LHN974_RED_LED_1206")
      (footprint "eagle-import:LEDC3216X120N")
      (fields (field (name "MF") "Osram") (field (name "MP") "LHN974 RED LED 1206"))
      (libsource (lib "eagle-import") (part "LHN974_RED_LED_1206"))
    )
    (comp (ref "LED23")
      (value "LHN974_RED_LED_1206")
      (footprint "eagle-import:LEDC3216X120N")
      (fields (field (name "MF") "Osram") (field (name "MP") "LHN974 RED LED 1206"))
      (libsource (lib "eagle-import") (part "LHN974_RED_LED_1206"))
    )
    (comp (ref "LED24")
      (value "LHN974_RED_LED_1206")
      (footprint "eagle-import:LEDC3216X120N")
      (fields (field (name "MF") "Osram") (field (name "MP") "LHN974 RED LED 1206"))
      (libsource (lib "eagle-import") (part "LHN974_RED_LED_1206"))
    )
    (comp (ref "LED25")
      (value "LHN974_RED_LED_1206")
      (footprint "eagle-import:LEDC3216X120N")
      (fields (field (name "MF") "Osram") (field (name "MP") "LHN974 RED LED 1206"))
      (libsource (lib "eagle-import") (part "LHN974_RED_LED_1206"))
    )
    (comp (ref "LED26")
      (value "LHN974_RED_LED_1206")
      (footprint "eagle-import:LEDC3216X120N")
      (fields (field (name "MF") "Osram") (field (name "MP") "LHN974 RED LED 1206"))
      (libsource (lib "eagle-import") (part "LHN974_RED_LED_1206"))
    )
    (comp (ref "LED27")
      (value "LHN974_RED_LED_1206")
      (footprint "eagle-import:LEDC3216X120N")
      (fields (field (name "MF") "Osram") (field (name "MP") "LHN974 RED LED 1206"))
      (libsource (lib "eagle-import") (part "LHN974_RED_LED_1206"))
    )
    (comp (ref "LED28")
      (value "LHN974_RED_LED_1206")
      (footprint "eagle-import:LEDC3216X120N")
      (fields (field (name "MF") "Osram") (field (name "MP") "LHN974 RED LED 1206"))
      (libsource (lib "eagle-import") (part "LHN974_RED_LED_1206"))
    )
    (comp (ref "LED29")
      (value "LHN974_RED_LED_1206")
      (footprint "eagle-import:LEDC3216X120N")
      (fields (field (name "MF") "Osram") (field (name "MP") "LHN974 RED LED 1206"))
      (libsource (lib "eagle-import") (part "LHN974_RED_LED_1206"))
    )
    (comp (ref "LED30")
      (value "LHN974_RED_LED_1206")
      (footprint "eagle-import:LEDC3216X120N")
      (fields (field (name "MF") "Osram") (field (name "MP") "LHN974 RED LED 1206"))
      (libsource (lib "eagle-import") (part "LHN974_RED_LED_1206"))
    )
    (comp (ref "LED31")
      (value "LHN974_RED_LED_1206")
      (footprint "eagle-import:LEDC3216X120N")
      (fields (field (name "MF") "Osram") (field (name "MP") "LHN974 RED LED 1206"))
      (libsource (lib "eagle-import") (part "LHN974_RED_LED_1206"))
    )
    (comp (ref "LED32")
      (value "LHN974_RED_LED_1206")
      (footprint "eagle-import:LEDC3216X120N")
      (fields (field (name "MF") "Osram") (field (name "MP") "LHN974 RED LED 1206"))
      (libsource (lib "eagle-import") (part "LHN974_RED_LED_1206"))
    )
    (comp (ref "LED33")
      (value "LHN974_RED_LED_1206")
      (footprint "eagle-import:LEDC3216X120N")
      (fields (field (name "MF") "Osram") (field (name "MP") "LHN974 RED LED 1206"))
      (libsource (lib "eagle-import") (part "LHN974_RED_LED_1206"))
    )
    (comp (ref "LED34")
      (value "LHN974_RED_LED_1206")
      (footprint "eagle-import:LEDC3216X120N")
      (fields (field (name "MF") "Osram") (field (name "MP") "LHN974 RED LED 1206"))
      (libsource (lib "eagle-import") (part "LHN974_RED_LED_1206"))
    )
    (comp (ref "LED35")
      (value "LHN974_RED_LED_1206")
      (footprint "eagle-import:LEDC3216X120N")
      (fields (field (name "MF") "Osram") (field (name "MP") "LHN974 RED LED 1206"))
      (libsource (lib "eagle-import") (part "LHN974_RED_LED_1206"))
    )
    (comp (ref "LED36")
      (value "LHN974_RED_LED_1206")
      (footprint "eagle-import:LEDC3216X120N")
      (fields (field (name "MF") "Osram") (field (name "MP") "LHN974 RED LED 1206"))
      (libsource (lib "eagle-import") (part "LHN974_RED_LED_1206"))
    )
    (comp (ref "LED37")
      (value "LHN974_RED_LED_1206")
      (footprint "eagle-import:LEDC3216X120N")
      (fields (field (name "MF") "Osram") (field (name "MP") "LHN974 RED LED 1206"))
      (libsource (lib "eagle-import") (part "LHN974_RED_LED_1206"))
    )
    (comp (ref "LED38")
      (value "LHN974_RED_LED_1206")
      (footprint "eagle-import:LEDC3216X120N")
      (fields (field (name "MF") "Osram") (field (name "MP") "LHN974 RED LED 1206"))
      (libsource (lib "eagle-import") (part "LHN974_RED_LED_1206"))
    )
    (comp (ref "LED39")
      (value "LHN974_RED_LED_1206")
      (footprint "eagle-import:LEDC3216X120N")
      (fields (field (name "MF") "Osram") (field (name "MP") "LHN974 RED LED 1206"))
      (libsource (lib "eagle-import") (part "LHN974_RED_LED_1206"))
    )
    (comp (ref "LED40")
      (value "LHN974_RED_LED_1206")
      (footprint "eagle-import:LEDC3216X120N")
      (fields (field (name "MF") "Osram") (field (name "MP") "LHN974 RED LED 1206"))
      (libsource (lib "eagle-import") (part "LHN974_RED_LED_1206"))
    )
    (comp (ref "LED41")
      (value "LHN974_RED_LED_1206")
      (footprint "eagle-import:LEDC3216X120N")
      (fields (field (name "MF") "Osram") (field (name "MP") "LHN974 RED LED 1206"))
      (libsource (lib "eagle-import") (part "LHN974_RED_LED_1206"))
    )
    (comp (ref "LED42")
      (value "LHN974_RED_LED_1206")
      (footprint "eagle-import:LEDC3216X120N")
      (fields (field (name "MF") "Osram") (field (name "MP") "LHN974 RED LED 1206"))
      (libsource (lib "eagle-import") (part "LHN974_RED_LED_1206"))
    )
    (comp (ref "LED43")
      (value "LHN974_RED_LED_1206")
      (footprint "eagle-import:LEDC3216X120N")
      (fields (field (name "MF") "Osram") (field (name "MP") "LHN974 RED LED 1206"))
      (libsource (lib "eagle-import") (part "LHN974_RED_LED_1206"))
    )
    (comp (ref "LED44")
      (value "LHN974_RED_LED_1206")
      (footprint "eagle-import:LEDC3216X120N")
      (fields (field (name "MF") "Osram") (field (name "MP") "LHN974 RED LED 1206"))
      (libsource (lib "eagle-import") (part "LHN974_RED_LED_1206"))
    )
    (comp (ref "LED45")
      (value "LHN974_RED_LED_1206")
      (footprint "eagle-import:LEDC3216X120N")
      (fields (field (name "MF") "Osram") (field (name "MP") "LHN974 RED LED 1206"))
      (libsource (lib "eagle-import") (part "LHN974_RED_LED_1206"))
    )
    (comp (ref "LED46")
      (value "LHN974_RED_LED_1206")
      (footprint "eagle-import:LEDC3216X120N")
      (fields (field (name "MF") "Osram") (field (name "MP") "LHN974 RED LED 1206"))
      (libsource (lib "eagle-import") (part "LHN974_RED_LED_1206"))
    )
    (comp (ref "LED47")
      (value "LHN974_RED_LED_1206")
      (footprint "eagle-import:LEDC3216X120N")
      (fields (field (name "MF") "Osram") (field (name "MP") "LHN974 RED LED 1206"))
      (libsource (lib "eagle-import") (part "LHN974_RED_LED_1206"))
    )
    (comp (ref "LED48")
      (value "LHN974_RED_LED_1206")
      (footprint "eagle-import:LEDC3216X120N")
      (fields (field (name "MF") "Osram") (field (name "MP") "LHN974 RED LED 1206"))
      (libsource (lib "eagle-import") (part "LHN974_RED_LED_1206"))
    )
    (comp (ref "MT1")
      (value "MT3608")
      (footprint "eagle-import:MT3608")
      (libsource (lib "eagle-import") (part "MT3608"))
    )
    (comp (ref "OPTO1")
      (value "PC817X2NIP0F")
      (footprint "eagle-import:SOT254P975X400-4N")
      (fields (field (name "MF") "Sharp Microelectronics"))
      (libsource (lib "eagle-import") (part "PC817X2NIP0F"))
    )
    (comp (ref "OPTO2")
      (value "PC817X2NIP0F")
      (footprint "eagle-import:SOT254P975X400-4N")
      (fields (field (name "MF") "Sharp Microelectronics"))
      (libsource (lib "eagle-import") (part "PC817X2NIP0F"))
    )
    (comp (ref "OPTO3")
      (value "PC817X2NIP0F")
      (footprint "eagle-import:SOT254P975X400-4N")
      (fields (field (name "MF") "Sharp Microelectronics"))
      (libsource (lib "eagle-import") (part "PC817X2NIP0F"))
    )
    (comp (ref "OPTO4")
      (value "PC817X2NIP0F")
      (footprint "eagle-import:SOT254P975X400-4N")
      (fields (field (name "MF") "Sharp Microelectronics"))
      (libsource (lib "eagle-import") (part "PC817X2NIP0F"))
    )
    (comp (ref "OPTO5")
      (value "PC817X2NIP0F")
      (footprint "eagle-import:SOT254P975X400-4N")
      (fields (field (name "MF") "Sharp Microelectronics"))
      (libsource (lib "eagle-import") (part "PC817X2NIP0F"))
    )
    (comp (ref "OPTO6")
      (value "PC817X2NIP0F")
      (footprint "eagle-import:SOT254P975X400-4N")
      (fields (field (name "MF") "Sharp Microelectronics"))
      (libsource (lib "eagle-import") (part "PC817X2NIP0F"))
    )
    (comp (ref "OPTO7")
      (value "PC817X2NIP0F")
      (footprint "eagle-import:SOT254P975X400-4N")
      (fields (field (name "MF") "Sharp Microelectronics"))
      (libsource (lib "eagle-import") (part "PC817X2NIP0F"))
    )
    (comp (ref "OPTO8")
      (value "PC817X2NIP0F")
      (footprint "eagle-import:SOT254P975X400-4N")
      (fields (field (name "MF") "Sharp Microelectronics"))
      (libsource (lib "eagle-import") (part "PC817X2NIP0F"))
    )
    (comp (ref "OPTO9")
      (value "PC817X2NIP0F")
      (footprint "eagle-import:SOT254P975X400-4N")
      (fields (field (name "MF") "Sharp Microelectronics"))
      (libsource (lib "eagle-import") (part "PC817X2NIP0F"))
    )
    (comp (ref "OPTO10")
      (value "PC817X2NIP0F")
      (footprint "eagle-import:SOT254P975X400-4N")
      (fields (field (name "MF") "Sharp Microelectronics"))
      (libsource (lib "eagle-import") (part "PC817X2NIP0F"))
    )
    (comp (ref "OPTO11")
      (value "PC817X2NIP0F")
      (footprint "eagle-import:SOT254P975X400-4N")
      (fields (field (name "MF") "Sharp Microelectronics"))
      (libsource (lib "eagle-import") (part "PC817X2NIP0F"))
    )
    (comp (ref "OPTO12")
      (value "PC817X2NIP0F")
      (footprint "eagle-import:SOT254P975X400-4N")
      (fields (field (name "MF") "Sharp Microelectronics"))
      (libsource (lib "eagle-import") (part "PC817X2NIP0F"))
    )
    (comp (ref "OPTO13")
      (value "PC817X2NIP0F")
      (footprint "eagle-import:SOT254P975X400-4N")
      (fields (field (name "MF") "Sharp Microelectronics"))
      (libsource (lib "eagle-import") (part "PC817X2NIP0F"))
    )
    (comp (ref "OPTO14")
      (value "PC817X2NIP0F")
      (footprint "eagle-import:SOT254P975X400-4N")
      (fields (field (name "MF") "Sharp Microelectronics"))
      (libsource (lib "eagle-import") (part "PC817X2NIP0F"))
    )
    (comp (ref "OPTO15")
      (value "PC817X2NIP0F")
      (footprint "eagle-import:SOT254P975X400-4N")
      (fields (field (name "MF") "Sharp Microelectronics"))
      (libsource (lib "eagle-import") (part "PC817X2NIP0F"))
    )
    (comp (ref "OPTO16")
      (value "PC817X2NIP0F")
      (footprint "eagle-import:SOT254P975X400-4N")
      (fields (field (name "MF") "Sharp Microelectronics"))
      (libsource (lib "eagle-import") (part "PC817X2NIP0F"))
    )
    (comp (ref "OPTO17")
      (value "PC817X2NIP0F")
      (footprint "eagle-import:SOT254P975X400-4N")
      (fields (field (name "MF") "Sharp Microelectronics"))
      (libsource (lib "eagle-import") (part "PC817X2NIP0F"))
    )
    (comp (ref "OPTO18")
      (value "PC817X2NIP0F")
      (footprint "eagle-import:SOT254P975X400-4N")
      (fields (field (name "MF") "Sharp Microelectronics"))
      (libsource (lib "eagle-import") (part "PC817X2NIP0F"))
    )
    (comp (ref "OPTO19")
      (value "PC817X2NIP0F")
      (footprint "eagle-import:SOT254P975X400-4N")
      (fields (field (name "MF") "Sharp Microelectronics"))
      (libsource (lib "eagle-import") (part "PC817X2NIP0F"))
    )
    (comp (ref "OPTO20")
      (value "PC817X2NIP0F")
      (footprint "eagle-import:SOT254P975X400-4N")
      (fields (field (name "MF") "Sharp Microelectronics"))
      (libsource (lib "eagle-import") (part "PC817X2NIP0F"))
    )
    (comp (ref "OPTO21")
      (value "PC817X2NIP0F")
      (footprint "eagle-import:SOT254P975X400-4N")
      (fields (field (name "MF") "Sharp Microelectronics"))
      (libsource (lib "eagle-import") (part "PC817X2NIP0F"))
    )
    (comp (ref "OPTO22")
      (value "PC817X2NIP0F")
      (footprint "eagle-import:SOT254P975X400-4N")
      (fields (field (name "MF") "Sharp Microelectronics"))
      (libsource (lib "eagle-import") (part "PC817X2NIP0F"))
    )
    (comp (ref "OPTO23")
      (value "PC817X2NIP0F")
      (footprint "eagle-import:SOT254P975X400-4N")
      (fields (field (name "MF") "Sharp Microelectronics"))
      (libsource (lib "eagle-import") (part "PC817X2NIP0F"))
    )
    (comp (ref "OPTO24")
      (value "PC817X2NIP0F")
      (footprint "eagle-import:SOT254P975X400-4N")
      (fields (field (name "MF") "Sharp Microelectronics"))
      (libsource (lib "eagle-import") (part "PC817X2NIP0F"))
    )
    (comp (ref "OPTO25")
      (value "PC817X2NIP0F")
      (footprint "eagle-import:SOT254P975X400-4N")
      (fields (field (name "MF") "Sharp Microelectronics"))
      (libsource (lib "eagle-import") (part "PC817X2NIP0F"))
    )
    (comp (ref "OPTO26")
      (value "PC817X2NIP0F")
      (footprint "eagle-import:SOT254P975X400-4N")
      (fields (field (name "MF") "Sharp Microelectronics"))
      (libsource (lib "eagle-import") (part "PC817X2NIP0F"))
    )
    (comp (ref "OPTO27")
      (value "PC817X2NIP0F")
      (footprint "eagle-import:SOT254P975X400-4N")
      (fields (field (name "MF") "Sharp Microelectronics"))
      (libsource (lib "eagle-import") (part "PC817X2NIP0F"))
    )
    (comp (ref "OPTO28")
      (value "PC817X2NIP0F")
      (footprint "eagle-import:SOT254P975X400-4N")
      (fields (field (name "MF") "Sharp Microelectronics"))
      (libsource (lib "eagle-import") (part "PC817X2NIP0F"))
    )
    (comp (ref "OPTO29")
      (value "PC817X2NIP0F")
      (footprint "eagle-import:SOT254P975X400-4N")
      (fields (field (name "MF") "Sharp Microelectronics"))
      (libsource (lib "eagle-import") (part "PC817X2NIP0F"))
    )
    (comp (ref "OPTO30")
      (value "PC817X2NIP0F")
      (footprint "eagle-import:SOT254P975X400-4N")
      (fields (field (name "MF") "Sharp Microelectronics"))
      (libsource (lib "eagle-import") (part "PC817X2NIP0F"))
    )
    (comp (ref "OPTO31")
      (value "PC817X2NIP0F")
      (footprint "eagle-import:SOT254P975X400-4N")
      (fields (field (name "MF") "Sharp Microelectronics"))
      (libsource (lib "eagle-import") (part "PC817X2NIP0F"))
    )
    (comp (ref "OPTO32")
      (value "PC817X2NIP0F")
      (footprint "eagle-import:SOT254P975X400-4N")
      (fields (field (name "MF") "Sharp Microelectronics"))
      (libsource (lib "eagle-import") (part "PC817X2NIP0F"))
    )
    (comp (ref "OPTO33")
      (value "PC817X2NIP0F")
      (footprint "eagle-import:SOT254P975X400-4N")
      (fields (field (name "MF") "Sharp Microelectronics"))
      (libsource (lib "eagle-import") (part "PC817X2NIP0F"))
    )
    (comp (ref "OPTO34")
      (value "PC817X2NIP0F")
      (footprint "eagle-import:SOT254P975X400-4N")
      (fields (field (name "MF") "Sharp Microelectronics"))
      (libsource (lib "eagle-import") (part "PC817X2NIP0F"))
    )
    (comp (ref "OPTO35")
      (value "PC817X2NIP0F")
      (footprint "eagle-import:SOT254P975X400-4N")
      (fields (field (name "MF") "Sharp Microelectronics"))
      (libsource (lib "eagle-import") (part "PC817X2NIP0F"))
    )
    (comp (ref "OPTO36")
      (value "PC817X2NIP0F")
      (footprint "eagle-import:SOT254P975X400-4N")
      (fields (field (name "MF") "Sharp Microelectronics"))
      (libsource (lib "eagle-import") (part "PC817X2NIP0F"))
    )
    (comp (ref "OPTO37")
      (value "PC817X2NIP0F")
      (footprint "eagle-import:SOT254P975X400-4N")
      (fields (field (name "MF") "Sharp Microelectronics"))
      (libsource (lib "eagle-import") (part "PC817X2NIP0F"))
    )
    (comp (ref "OPTO38")
      (value "PC817X2NIP0F")
      (footprint "eagle-import:SOT254P975X400-4N")
      (fields (field (name "MF") "Sharp Microelectronics"))
      (libsource (lib "eagle-import") (part "PC817X2NIP0F"))
    )
    (comp (ref "OPTO39")
      (value "PC817X2NIP0F")
      (footprint "eagle-import:SOT254P975X400-4N")
      (fields (field (name "MF") "Sharp Microelectronics"))
      (libsource (lib "eagle-import") (part "PC817X2NIP0F"))
    )
    (comp (ref "OPTO40")
      (value "PC817X2NIP0F")
      (footprint "eagle-import:SOT254P975X400-4N")
      (fields (field (name "MF") "Sharp Microelectronics"))
      (libsource (lib "eagle-import") (part "PC817X2NIP0F"))
    )
    (comp (ref "OPTO41")
      (value "PC817X2NIP0F")
      (footprint "eagle-import:SOT254P975X400-4N")
      (fields (field (name "MF") "Sharp Microelectronics"))
      (libsource (lib "eagle-import") (part "PC817X2NIP0F"))
    )
    (comp (ref "OPTO42")
      (value "PC817X2NIP0F")
      (footprint "eagle-import:SOT254P975X400-4N")
      (fields (field (name "MF") "Sharp Microelectronics"))
      (libsource (lib "eagle-import") (part "PC817X2NIP0F"))
    )
    (comp (ref "OPTO43")
      (value "PC817X2NIP0F")
      (footprint "eagle-import:SOT254P975X400-4N")
      (fields (field (name "MF") "Sharp Microelectronics"))
      (libsource (lib "eagle-import") (part "PC817X2NIP0F"))
    )
    (comp (ref "OPTO44")
      (value "PC817X2NIP0F")
      (footprint "eagle-import:SOT254P975X400-4N")
      (fields (field (name "MF") "Sharp Microelectronics"))
      (libsource (lib "eagle-import") (part "PC817X2NIP0F"))
    )
    (comp (ref "OPTO45")
      (value "PC817X2NIP0F")
      (footprint "eagle-import:SOT254P975X400-4N")
      (fields (field (name "MF") "Sharp Microelectronics"))
      (libsource (lib "eagle-import") (part "PC817X2NIP0F"))
    )
    (comp (ref "OPTO46")
      (value "PC817X2NIP0F")
      (footprint "eagle-import:SOT254P975X400-4N")
      (fields (field (name "MF") "Sharp Microelectronics"))
      (libsource (lib "eagle-import") (part "PC817X2NIP0F"))
    )
    (comp (ref "OPTO47")
      (value "PC817X2NIP0F")
      (footprint "eagle-import:SOT254P975X400-4N")
      (fields (field (name "MF") "Sharp Microelectronics"))
      (libsource (lib "eagle-import") (part "PC817X2NIP0F"))
    )
    (comp (ref "OPTO48")
      (value "PC817X2NIP0F")
      (footprint "eagle-import:SOT254P975X400-4N")
      (fields (field (name "MF") "Sharp Microelectronics"))
      (libsource (lib "eagle-import") (part "PC817X2NIP0F"))
    )
    (comp (ref "POWER")
      (value "TLLY4400")
      (footprint "eagle-import:LED3MM")
      (fields (field (name "MF") "VISHAY SEMICONDUCTOR"))
      (libsource (lib "eagle-import") (part "TLLY4400"))
    )
    (comp (ref "PROSES")
      (value "TLLY4400")
      (footprint "eagle-import:LED3MM")
      (fields (field (name "MF") "VISHAY SEMICONDUCTOR"))
      (libsource (lib "eagle-import") (part "TLLY4400"))
    )
    (comp (ref "PS2")
      (value "HLK-10M05")
      (footprint "eagle-import:HLK10M05")
      (fields (field (name "MF") "Hi-link"))
      (libsource (lib "eagle-import") (part "HLK-10M05"))
    )
    (comp (ref "Q1")
      (value "S9013")
      (footprint "eagle-import:SOT95P240X120-3N")
      (fields (field (name "MF") "JCET"))
      (libsource (lib "eagle-import") (part "S9013"))
    )
    (comp (ref "Q2")
      (value "MMBT3904")
      (footprint "eagle-import:SOT95P240X120-3N")
      (fields (field (name "MF") "ON Semiconductor"))
      (libsource (lib "eagle-import") (part "MMBT3904"))
    )
    (comp (ref "Q3")
      (value "MMBT3904")
      (footprint "eagle-import:SOT95P240X120-3N")
      (fields (field (name "MF") "ON Semiconductor"))
      (libsource (lib "eagle-import") (part "MMBT3904"))
    )
    (comp (ref "Q4")
      (value "12MHz")
      (footprint "eagle-import:SM49")
      (libsource (lib "eagle-import") (part "CRYSTALSM49"))
    )
    (comp (ref "Q5")
      (value "S9013")
      (footprint "eagle-import:SOT95P240X120-3N")
      (fields (field (name "MF") "JCET"))
      (libsource (lib "eagle-import") (part "S9013"))
    )
    (comp (ref "Q6")
      (value "S9013")
      (footprint "eagle-import:SOT95P240X120-3N")
      (fields (field (name "MF") "JCET"))
      (libsource (lib "eagle-import") (part "S9013"))
    )
    (comp (ref "Q7")
      (value "S9013")
      (footprint "eagle-import:SOT95P240X120-3N")
      (fields (field (name "MF") "JCET"))
      (libsource (lib "eagle-import") (part "S9013"))
    )
    (comp (ref "Q8")
      (value "S9013")
      (footprint "eagle-import:SOT95P240X120-3N")
      (fields (field (name "MF") "JCET"))
      (libsource (lib "eagle-import") (part "S9013"))
    )
    (comp (ref "Q9")
      (value "S9013")
      (footprint "eagle-import:SOT95P240X120-3N")
      (fields (field (name "MF") "JCET"))
      (libsource (lib "eagle-import") (part "S9013"))
    )
    (comp (ref "R1")
      (value "R-EU_0617/17")
      (footprint "eagle-import:0617_17")
      (libsource (lib "eagle-import") (part "R-EU_0617/17"))
    )
    (comp (ref "R2")
      (value "R-EU_0617/17")
      (footprint "eagle-import:0617_17")
      (libsource (lib "eagle-import") (part "R-EU_0617/17"))
    )
    (comp (ref "R3")
      (value "R-EU_0617/17")
      (footprint "eagle-import:0617_17")
      (libsource (lib "eagle-import") (part "R-EU_0617/17"))
    )
    (comp (ref "R4")
      (value "R-EU_0617/17")
      (footprint "eagle-import:0617_17")
      (libsource (lib "eagle-import") (part "R-EU_0617/17"))
    )
    (comp (ref "R5")
      (value "R-EU_0617/17")
      (footprint "eagle-import:0617_17")
      (libsource (lib "eagle-import") (part "R-EU_0617/17"))
    )
    (comp (ref "R6")
      (value "R-EU_0617/17")
      (footprint "eagle-import:0617_17")
      (libsource (lib "eagle-import") (part "R-EU_0617/17"))
    )
    (comp (ref "R7")
      (value "R-EU_0617/17")
      (footprint "eagle-import:0617_17")
      (libsource (lib "eagle-import") (part "R-EU_0617/17"))
    )
    (comp (ref "R8")
      (value "R-EU_0617/17")
      (footprint "eagle-import:0617_17")
      (libsource (lib "eagle-import") (part "R-EU_0617/17"))
    )
    (comp (ref "R9")
      (value "R-EU_0617/17")
      (footprint "eagle-import:0617_17")
      (libsource (lib "eagle-import") (part "R-EU_0617/17"))
    )
    (comp (ref "R10")
      (value "R-EU_0617/17")
      (footprint "eagle-import:0617_17")
      (libsource (lib "eagle-import") (part "R-EU_0617/17"))
    )
    (comp (ref "R11")
      (value "R-EU_0617/17")
      (footprint "eagle-import:0617_17")
      (libsource (lib "eagle-import") (part "R-EU_0617/17"))
    )
    (comp (ref "R12")
      (value "R-EU_0617/17")
      (footprint "eagle-import:0617_17")
      (libsource (lib "eagle-import") (part "R-EU_0617/17"))
    )
    (comp (ref "R13")
      (value "R-EU_0617/17")
      (footprint "eagle-import:0617_17")
      (libsource (lib "eagle-import") (part "R-EU_0617/17"))
    )
    (comp (ref "R14")
      (value "R-EU_0617/17")
      (footprint "eagle-import:0617_17")
      (libsource (lib "eagle-import") (part "R-EU_0617/17"))
    )
    (comp (ref "R15")
      (value "R-EU_0617/17")
      (footprint "eagle-import:0617_17")
      (libsource (lib "eagle-import") (part "R-EU_0617/17"))
    )
    (comp (ref "R16")
      (value "R-EU_0617/17")
      (footprint "eagle-import:0617_17")
      (libsource (lib "eagle-import") (part "R-EU_0617/17"))
    )
    (comp (ref "R17")
      (value "R-EU_0617/17")
      (footprint "eagle-import:0617_17")
      (libsource (lib "eagle-import") (part "R-EU_0617/17"))
    )
    (comp (ref "R18")
      (value "R-EU_0617/17")
      (footprint "eagle-import:0617_17")
      (libsource (lib "eagle-import") (part "R-EU_0617/17"))
    )
    (comp (ref "R19")
      (value "R-EU_0617/17")
      (footprint "eagle-import:0617_17")
      (libsource (lib "eagle-import") (part "R-EU_0617/17"))
    )
    (comp (ref "R20")
      (value "R-EU_0617/17")
      (footprint "eagle-import:0617_17")
      (libsource (lib "eagle-import") (part "R-EU_0617/17"))
    )
    (comp (ref "R21")
      (value "R-EU_0617/17")
      (footprint "eagle-import:0617_17")
      (libsource (lib "eagle-import") (part "R-EU_0617/17"))
    )
    (comp (ref "R22")
      (value "R-EU_0617/17")
      (footprint "eagle-import:0617_17")
      (libsource (lib "eagle-import") (part "R-EU_0617/17"))
    )
    (comp (ref "R23")
      (value "R-EU_0617/17")
      (footprint "eagle-import:0617_17")
      (libsource (lib "eagle-import") (part "R-EU_0617/17"))
    )
    (comp (ref "R24")
      (value "R-EU_0617/17")
      (footprint "eagle-import:0617_17")
      (libsource (lib "eagle-import") (part "R-EU_0617/17"))
    )
    (comp (ref "R25")
      (value "R-EU_0617/17")
      (footprint "eagle-import:0617_17")
      (libsource (lib "eagle-import") (part "R-EU_0617/17"))
    )
    (comp (ref "R26")
      (value "R-EU_0617/17")
      (footprint "eagle-import:0617_17")
      (libsource (lib "eagle-import") (part "R-EU_0617/17"))
    )
    (comp (ref "R27")
      (value "R-EU_0617/17")
      (footprint "eagle-import:0617_17")
      (libsource (lib "eagle-import") (part "R-EU_0617/17"))
    )
    (comp (ref "R28")
      (value "R-EU_0617/17")
      (footprint "eagle-import:0617_17")
      (libsource (lib "eagle-import") (part "R-EU_0617/17"))
    )
    (comp (ref "R29")
      (value "R-EU_0617/17")
      (footprint "eagle-import:0617_17")
      (libsource (lib "eagle-import") (part "R-EU_0617/17"))
    )
    (comp (ref "R30")
      (value "R-EU_0617/17")
      (footprint "eagle-import:0617_17")
      (libsource (lib "eagle-import") (part "R-EU_0617/17"))
    )
    (comp (ref "R31")
      (value "R-EU_0617/17")
      (footprint "eagle-import:0617_17")
      (libsource (lib "eagle-import") (part "R-EU_0617/17"))
    )
    (comp (ref "R32")
      (value "R-EU_0617/17")
      (footprint "eagle-import:0617_17")
      (libsource (lib "eagle-import") (part "R-EU_0617/17"))
    )
    (comp (ref "R33")
      (value "R-EU_0617/17")
      (footprint "eagle-import:0617_17")
      (libsource (lib "eagle-import") (part "R-EU_0617/17"))
    )
    (comp (ref "R34")
      (value "R-EU_0617/17")
      (footprint "eagle-import:0617_17")
      (libsource (lib "eagle-import") (part "R-EU_0617/17"))
    )
    (comp (ref "R35")
      (value "R-EU_0617/17")
      (footprint "eagle-import:0617_17")
      (libsource (lib "eagle-import") (part "R-EU_0617/17"))
    )
    (comp (ref "R36")
      (value "R-EU_0617/17")
      (footprint "eagle-import:0617_17")
      (libsource (lib "eagle-import") (part "R-EU_0617/17"))
    )
    (comp (ref "R37")
      (value "R-EU_0617/17")
      (footprint "eagle-import:0617_17")
      (libsource (lib "eagle-import") (part "R-EU_0617/17"))
    )
    (comp (ref "R38")
      (value "R-EU_0617/17")
      (footprint "eagle-import:0617_17")
      (libsource (lib "eagle-import") (part "R-EU_0617/17"))
    )
    (comp (ref "R39")
      (value "R-EU_0617/17")
      (footprint "eagle-import:0617_17")
      (libsource (lib "eagle-import") (part "R-EU_0617/17"))
    )
    (comp (ref "R40")
      (value "R-EU_0617/17")
      (footprint "eagle-import:0617_17")
      (libsource (lib "eagle-import") (part "R-EU_0617/17"))
    )
    (comp (ref "R41")
      (value "R-EU_0617/17")
      (footprint "eagle-import:0617_17")
      (libsource (lib "eagle-import") (part "R-EU_0617/17"))
    )
    (comp (ref "R42")
      (value "R-EU_0617/17")
      (footprint "eagle-import:0617_17")
      (libsource (lib "eagle-import") (part "R-EU_0617/17"))
    )
    (comp (ref "R43")
      (value "R-EU_0617/17")
      (footprint "eagle-import:0617_17")
      (libsource (lib "eagle-import") (part "R-EU_0617/17"))
    )
    (comp (ref "R44")
      (value "R-EU_0617/17")
      (footprint "eagle-import:0617_17")
      (libsource (lib "eagle-import") (part "R-EU_0617/17"))
    )
    (comp (ref "R45")
      (value "R-EU_0617/17")
      (footprint "eagle-import:0617_17")
      (libsource (lib "eagle-import") (part "R-EU_0617/17"))
    )
    (comp (ref "R46")
      (value "R-EU_0617/17")
      (footprint "eagle-import:0617_17")
      (libsource (lib "eagle-import") (part "R-EU_0617/17"))
    )
    (comp (ref "R47")
      (value "R-EU_0617/17")
      (footprint "eagle-import:0617_17")
      (libsource (lib "eagle-import") (part "R-EU_0617/17"))
    )
    (comp (ref "R48")
      (value "R-EU_0617/17")
      (footprint "eagle-import:0617_17")
      (libsource (lib "eagle-import") (part "R-EU_0617/17"))
    )
    (comp (ref "R49")
      (value "R-EU_R0805")
      (footprint "eagle-import:R0805")
      (libsource (lib "eagle-import") (part "R-EU_R0805"))
    )
    (comp (ref "R50")
      (value "R-EU_R0805")
      (footprint "eagle-import:R0805")
      (libsource (lib "eagle-import") (part "R-EU_R0805"))
    )
    (comp (ref "R51")
      (value "R-EU_R0805")
      (footprint "eagle-import:R0805")
      (libsource (lib "eagle-import") (part "R-EU_R0805"))
    )
    (comp (ref "R52")
      (value "R-EU_R0805")
      (footprint "eagle-import:R0805")
      (libsource (lib "eagle-import") (part "R-EU_R0805"))
    )
    (comp (ref "R53")
      (value "R-EU_R0805")
      (footprint "eagle-import:R0805")
      (libsource (lib "eagle-import") (part "R-EU_R0805"))
    )
    (comp (ref "R54")
      (value "R-EU_R0805")
      (footprint "eagle-import:R0805")
      (libsource (lib "eagle-import") (part "R-EU_R0805"))
    )
    (comp (ref "R55")
      (value "R-EU_R0805")
      (footprint "eagle-import:R0805")
      (libsource (lib "eagle-import") (part "R-EU_R0805"))
    )
    (comp (ref "R56")
      (value "R-EU_R0805")
      (footprint "eagle-import:R0805")
      (libsource (lib "eagle-import") (part "R-EU_R0805"))
    )
    (comp (ref "R57")
      (value "R-EU_R0805")
      (footprint "eagle-import:R0805")
      (libsource (lib "eagle-import") (part "R-EU_R0805"))
    )
    (comp (ref "R58")
      (value "R-EU_R0805")
      (footprint "eagle-import:R0805")
      (libsource (lib "eagle-import") (part "R-EU_R0805"))
    )
    (comp (ref "R59")
      (value "R-EU_R0805")
      (footprint "eagle-import:R0805")
      (libsource (lib "eagle-import") (part "R-EU_R0805"))
    )
    (comp (ref "R60")
      (value "R-EU_R0805")
      (footprint "eagle-import:R0805")
      (libsource (lib "eagle-import") (part "R-EU_R0805"))
    )
    (comp (ref "R61")
      (value "R-EU_R0805")
      (footprint "eagle-import:R0805")
      (libsource (lib "eagle-import") (part "R-EU_R0805"))
    )
    (comp (ref "R62")
      (value "R-EU_R0805")
      (footprint "eagle-import:R0805")
      (libsource (lib "eagle-import") (part "R-EU_R0805"))
    )
    (comp (ref "R63")
      (value "R-EU_R0805")
      (footprint "eagle-import:R0805")
      (libsource (lib "eagle-import") (part "R-EU_R0805"))
    )
    (comp (ref "R64")
      (value "R-EU_R0805")
      (footprint "eagle-import:R0805")
      (libsource (lib "eagle-import") (part "R-EU_R0805"))
    )
    (comp (ref "R65")
      (value "R-EU_R0805")
      (footprint "eagle-import:R0805")
      (libsource (lib "eagle-import") (part "R-EU_R0805"))
    )
    (comp (ref "R66")
      (value "R-EU_R0805")
      (footprint "eagle-import:R0805")
      (libsource (lib "eagle-import") (part "R-EU_R0805"))
    )
    (comp (ref "R67")
      (value "R-EU_R0805")
      (footprint "eagle-import:R0805")
      (libsource (lib "eagle-import") (part "R-EU_R0805"))
    )
    (comp (ref "R68")
      (value "R-EU_R0805")
      (footprint "eagle-import:R0805")
      (libsource (lib "eagle-import") (part "R-EU_R0805"))
    )
    (comp (ref "R69")
      (value "R-EU_R0805")
      (footprint "eagle-import:R0805")
      (libsource (lib "eagle-import") (part "R-EU_R0805"))
    )
    (comp (ref "R70")
      (value "R-EU_R0805")
      (footprint "eagle-import:R0805")
      (libsource (lib "eagle-import") (part "R-EU_R0805"))
    )
    (comp (ref "R71")
      (value "R-EU_R0805")
      (footprint "eagle-import:R0805")
      (libsource (lib "eagle-import") (part "R-EU_R0805"))
    )
    (comp (ref "R72")
      (value "R-EU_R0805")
      (footprint "eagle-import:R0805")
      (libsource (lib "eagle-import") (part "R-EU_R0805"))
    )
    (comp (ref "R73")
      (value "R-EU_R0805")
      (footprint "eagle-import:R0805")
      (libsource (lib "eagle-import") (part "R-EU_R0805"))
    )
    (comp (ref "R74")
      (value "R-EU_R0805")
      (footprint "eagle-import:R0805")
      (libsource (lib "eagle-import") (part "R-EU_R0805"))
    )
    (comp (ref "R75")
      (value "R-EU_R0805")
      (footprint "eagle-import:R0805")
      (libsource (lib "eagle-import") (part "R-EU_R0805"))
    )
    (comp (ref "R76")
      (value "R-EU_R0805")
      (footprint "eagle-import:R0805")
      (libsource (lib "eagle-import") (part "R-EU_R0805"))
    )
    (comp (ref "R77")
      (value "R-EU_R0805")
      (footprint "eagle-import:R0805")
      (libsource (lib "eagle-import") (part "R-EU_R0805"))
    )
    (comp (ref "R78")
      (value "R-EU_R0805")
      (footprint "eagle-import:R0805")
      (libsource (lib "eagle-import") (part "R-EU_R0805"))
    )
    (comp (ref "R79")
      (value "R-EU_R0805")
      (footprint "eagle-import:R0805")
      (libsource (lib "eagle-import") (part "R-EU_R0805"))
    )
    (comp (ref "R80")
      (value "R-EU_R0805")
      (footprint "eagle-import:R0805")
      (libsource (lib "eagle-import") (part "R-EU_R0805"))
    )
    (comp (ref "R81")
      (value "R-EU_R0805")
      (footprint "eagle-import:R0805")
      (libsource (lib "eagle-import") (part "R-EU_R0805"))
    )
    (comp (ref "R82")
      (value "R-EU_R0805")
      (footprint "eagle-import:R0805")
      (libsource (lib "eagle-import") (part "R-EU_R0805"))
    )
    (comp (ref "R83")
      (value "R-EU_R0805")
      (footprint "eagle-import:R0805")
      (libsource (lib "eagle-import") (part "R-EU_R0805"))
    )
    (comp (ref "R84")
      (value "R-EU_R0805")
      (footprint "eagle-import:R0805")
      (libsource (lib "eagle-import") (part "R-EU_R0805"))
    )
    (comp (ref "R85")
      (value "R-EU_R0805")
      (footprint "eagle-import:R0805")
      (libsource (lib "eagle-import") (part "R-EU_R0805"))
    )
    (comp (ref "R86")
      (value "R-EU_R0805")
      (footprint "eagle-import:R0805")
      (libsource (lib "eagle-import") (part "R-EU_R0805"))
    )
    (comp (ref "R87")
      (value "R-EU_R0805")
      (footprint "eagle-import:R0805")
      (libsource (lib "eagle-import") (part "R-EU_R0805"))
    )
    (comp (ref "R88")
      (value "R-EU_R0805")
      (footprint "eagle-import:R0805")
      (libsource (lib "eagle-import") (part "R-EU_R0805"))
    )
    (comp (ref "R89")
      (value "R-EU_R0805")
      (footprint "eagle-import:R0805")
      (libsource (lib "eagle-import") (part "R-EU_R0805"))
    )
    (comp (ref "R90")
      (value "R-EU_R0805")
      (footprint "eagle-import:R0805")
      (libsource (lib "eagle-import") (part "R-EU_R0805"))
    )
    (comp (ref "R91")
      (value "R-EU_R0805")
      (footprint "eagle-import:R0805")
      (libsource (lib "eagle-import") (part "R-EU_R0805"))
    )
    (comp (ref "R92")
      (value "R-EU_R0805")
      (footprint "eagle-import:R0805")
      (libsource (lib "eagle-import") (part "R-EU_R0805"))
    )
    (comp (ref "R93")
      (value "R-EU_R0805")
      (footprint "eagle-import:R0805")
      (libsource (lib "eagle-import") (part "R-EU_R0805"))
    )
    (comp (ref "R94")
      (value "R-EU_R0805")
      (footprint "eagle-import:R0805")
      (libsource (lib "eagle-import") (part "R-EU_R0805"))
    )
    (comp (ref "R95")
      (value "R-EU_R0805")
      (footprint "eagle-import:R0805")
      (libsource (lib "eagle-import") (part "R-EU_R0805"))
    )
    (comp (ref "R96")
      (value "R-EU_R0805")
      (footprint "eagle-import:R0805")
      (libsource (lib "eagle-import") (part "R-EU_R0805"))
    )
    (comp (ref "R97")
      (value "R-EU_R0805")
      (footprint "eagle-import:R0805")
      (libsource (lib "eagle-import") (part "R-EU_R0805"))
    )
    (comp (ref "R98")
      (value "R-EU_R0805")
      (footprint "eagle-import:R0805")
      (libsource (lib "eagle-import") (part "R-EU_R0805"))
    )
    (comp (ref "R99")
      (value "R-EU_R0805")
      (footprint "eagle-import:R0805")
      (libsource (lib "eagle-import") (part "R-EU_R0805"))
    )
    (comp (ref "R100")
      (value "R-EU_R0805")
      (footprint "eagle-import:R0805")
      (libsource (lib "eagle-import") (part "R-EU_R0805"))
    )
    (comp (ref "R101")
      (value "R-EU_R0805")
      (footprint "eagle-import:R0805")
      (libsource (lib "eagle-import") (part "R-EU_R0805"))
    )
    (comp (ref "R102")
      (value "R-EU_R0805")
      (footprint "eagle-import:R0805")
      (libsource (lib "eagle-import") (part "R-EU_R0805"))
    )
    (comp (ref "R103")
      (value "R-EU_R0805")
      (footprint "eagle-import:R0805")
      (libsource (lib "eagle-import") (part "R-EU_R0805"))
    )
    (comp (ref "R104")
      (value "R-EU_R0805")
      (footprint "eagle-import:R0805")
      (libsource (lib "eagle-import") (part "R-EU_R0805"))
    )
    (comp (ref "R105")
      (value "R-EU_R0805")
      (footprint "eagle-import:R0805")
      (libsource (lib "eagle-import") (part "R-EU_R0805"))
    )
    (comp (ref "R106")
      (value "R-EU_R0805")
      (footprint "eagle-import:R0805")
      (libsource (lib "eagle-import") (part "R-EU_R0805"))
    )
    (comp (ref "R107")
      (value "R-EU_R0805")
      (footprint "eagle-import:R0805")
      (libsource (lib "eagle-import") (part "R-EU_R0805"))
    )
    (comp (ref "R108")
      (value "R-EU_R0805")
      (footprint "eagle-import:R0805")
      (libsource (lib "eagle-import") (part "R-EU_R0805"))
    )
    (comp (ref "R109")
      (value "R-EU_R0805")
      (footprint "eagle-import:R0805")
      (libsource (lib "eagle-import") (part "R-EU_R0805"))
    )
    (comp (ref "R110")
      (value "R-EU_R0805")
      (footprint "eagle-import:R0805")
      (libsource (lib "eagle-import") (part "R-EU_R0805"))
    )
    (comp (ref "R111")
      (value "R-EU_R0805")
      (footprint "eagle-import:R0805")
      (libsource (lib "eagle-import") (part "R-EU_R0805"))
    )
    (comp (ref "R112")
      (value "R-EU_R0805")
      (footprint "eagle-import:R0805")
      (libsource (lib "eagle-import") (part "R-EU_R0805"))
    )
    (comp (ref "R113")
      (value "R-EU_R0805")
      (footprint "eagle-import:R0805")
      (libsource (lib "eagle-import") (part "R-EU_R0805"))
    )
    (comp (ref "R114")
      (value "R-EU_R0805")
      (footprint "eagle-import:R0805")
      (libsource (lib "eagle-import") (part "R-EU_R0805"))
    )
    (comp (ref "R115")
      (value "R-EU_R0805")
      (footprint "eagle-import:R0805")
      (libsource (lib "eagle-import") (part "R-EU_R0805"))
    )
    (comp (ref "R116")
      (value "R-EU_R0805")
      (footprint "eagle-import:R0805")
      (libsource (lib "eagle-import") (part "R-EU_R0805"))
    )
    (comp (ref "R117")
      (value "10k")
      (footprint "eagle-import:M0805")
      (libsource (lib "eagle-import") (part "R-US_M0805"))
    )
    (comp (ref "R118")
      (value "10k")
      (footprint "eagle-import:M0805")
      (libsource (lib "eagle-import") (part "R-US_M0805"))
    )
    (comp (ref "R119")
      (value "10k")
      (footprint "eagle-import:M0805")
      (libsource (lib "eagle-import") (part "R-US_M0805"))
    )
    (comp (ref "R120")
      (value "10k")
      (footprint "eagle-import:M0805")
      (libsource (lib "eagle-import") (part "R-US_M0805"))
    )
    (comp (ref "R121")
      (value "330")
      (footprint "eagle-import:M0805")
      (libsource (lib "eagle-import") (part "R-US_M0805"))
    )
    (comp (ref "R122")
      (value "330")
      (footprint "eagle-import:M0805")
      (libsource (lib "eagle-import") (part "R-US_M0805"))
    )
    (comp (ref "R123")
      (value "330")
      (footprint "eagle-import:M0805")
      (libsource (lib "eagle-import") (part "R-US_M0805"))
    )
    (comp (ref "R124")
      (value "330")
      (footprint "eagle-import:M0805")
      (libsource (lib "eagle-import") (part "R-US_M0805"))
    )
    (comp (ref "R125")
      (value "330")
      (footprint "eagle-import:M0805")
      (libsource (lib "eagle-import") (part "R-US_M0805"))
    )
    (comp (ref "R126")
      (value "330")
      (footprint "eagle-import:M0805")
      (libsource (lib "eagle-import") (part "R-US_M0805"))
    )
    (comp (ref "R127")
      (value "10k")
      (footprint "eagle-import:M0805")
      (libsource (lib "eagle-import") (part "R-US_M0805"))
    )
    (comp (ref "R128")
      (value "10k")
      (footprint "eagle-import:M0805")
      (libsource (lib "eagle-import") (part "R-US_M0805"))
    )
    (comp (ref "R129")
      (value "330")
      (footprint "eagle-import:M0805")
      (libsource (lib "eagle-import") (part "R-US_M0805"))
    )
    (comp (ref "R130")
      (value "10k")
      (footprint "eagle-import:M0805")
      (libsource (lib "eagle-import") (part "R-US_M0805"))
    )
    (comp (ref "R131")
      (value "10k")
      (footprint "eagle-import:M0805")
      (libsource (lib "eagle-import") (part "R-US_M0805"))
    )
    (comp (ref "R132")
      (value "330")
      (footprint "eagle-import:M0805")
      (libsource (lib "eagle-import") (part "R-US_M0805"))
    )
    (comp (ref "R133")
      (value "10k")
      (footprint "eagle-import:M0805")
      (libsource (lib "eagle-import") (part "R-US_M0805"))
    )
    (comp (ref "R134")
      (value "10k")
      (footprint "eagle-import:M0805")
      (libsource (lib "eagle-import") (part "R-US_M0805"))
    )
    (comp (ref "R135")
      (value "330")
      (footprint "eagle-import:M0805")
      (libsource (lib "eagle-import") (part "R-US_M0805"))
    )
    (comp (ref "R136")
      (value "10k")
      (footprint "eagle-import:M0805")
      (libsource (lib "eagle-import") (part "R-US_M0805"))
    )
    (comp (ref "R137")
      (value "10k")
      (footprint "eagle-import:M0805")
      (libsource (lib "eagle-import") (part "R-US_M0805"))
    )
    (comp (ref "R138")
      (value "330")
      (footprint "eagle-import:M0805")
      (libsource (lib "eagle-import") (part "R-US_M0805"))
    )
    (comp (ref "R139")
      (value "10k")
      (footprint "eagle-import:M0805")
      (libsource (lib "eagle-import") (part "R-US_M0805"))
    )
    (comp (ref "RTC1")
      (value "RTC3231")
      (footprint "eagle-import:RTC3231")
      (libsource (lib "eagle-import") (part "RTC3231"))
    )
    (comp (ref "S1")
      (value "31-XX")
      (footprint "eagle-import:B3F-31XX")
      (fields (field (name "MPN") "B3F-3100"))
      (libsource (lib "eagle-import") (part "31-XX"))
    )
    (comp (ref "S3")
      (value "31-XX")
      (footprint "eagle-import:B3F-31XX")
      (fields (field (name "MPN") "B3F-3100"))
      (libsource (lib "eagle-import") (part "31-XX"))
    )
    (comp (ref "TTL-RS1")
      (value "TTL-RS485")
      (footprint "eagle-import:TTL-RS485")
      (libsource (lib "eagle-import") (part "TTL-RS485"))
    )
    (comp (ref "U$1")
      (value "MINI_W5500")
      (footprint "eagle-import:MINI_W5500")
      (libsource (lib "eagle-import") (part "MINI_W5500"))
    )
    (comp (ref "U1")
      (value "CH340G")
      (footprint "eagle-import:SOIC127P600X180-16N")
      (fields (field (name "MF") "WCH") (field (name "MP") "Ch340G"))
      (libsource (lib "eagle-import") (part "CH340G"))
    )
    (comp (ref "U2")
      (value "AMS1117")
      (footprint "eagle-import:SOT229P700X180-4N")
      (fields (field (name "MF") "Advanced Monolithic Systems"))
      (libsource (lib "eagle-import") (part "AMS1117"))
    )
    (comp (ref "U3")
      (value "ESP32-WROOM-32D")
      (footprint "eagle-import:MODULE_ESP32-WROOM-32D")
      (fields (field (name "MF") "Espressif Systems"))
      (libsource (lib "eagle-import") (part "ESP32-WROOM-32D"))
    )
    (comp (ref "U4")
      (value "PC817X2NIP0F")
      (footprint "eagle-import:SOT254P975X400-4N")
      (fields (field (name "MF") "Sharp Microelectronics"))
      (libsource (lib "eagle-import") (part "PC817X2NIP0F"))
    )
    (comp (ref "U5")
      (value "PC817X2NIP0F")
      (footprint "eagle-import:SOT254P975X400-4N")
      (fields (field (name "MF") "Sharp Microelectronics"))
      (libsource (lib "eagle-import") (part "PC817X2NIP0F"))
    )
    (comp (ref "U6")
      (value "PC817X2NIP0F")
      (footprint "eagle-import:SOT254P975X400-4N")
      (fields (field (name "MF") "Sharp Microelectronics"))
      (libsource (lib "eagle-import") (part "PC817X2NIP0F"))
    )
    (comp (ref "U7")
      (value "PC817X2NIP0F")
      (footprint "eagle-import:SOT254P975X400-4N")
      (fields (field (name "MF") "Sharp Microelectronics"))
      (libsource (lib "eagle-import") (part "PC817X2NIP0F"))
    )
    (comp (ref "U8")
      (value "PC817X2NIP0F")
      (footprint "eagle-import:SOT254P975X400-4N")
      (fields (field (name "MF") "Sharp Microelectronics"))
      (libsource (lib "eagle-import") (part "PC817X2NIP0F"))
    )
    (comp (ref "U49")
      (value "PC817X2NIP0F")
      (footprint "eagle-import:SOT254P975X400-4N")
      (fields (field (name "MF") "Sharp Microelectronics"))
      (libsource (lib "eagle-import") (part "PC817X2NIP0F"))
    )
    (comp (ref "WARNING")
      (value "TLLY4400")
      (footprint "eagle-import:LED3MM")
      (fields (field (name "MF") "VISHAY SEMICONDUCTOR"))
      (libsource (lib "eagle-import") (part "TLLY4400"))
    )
    (comp (ref "X1")
      (value "22-23-2031")
      (footprint "eagle-import:22-23-2031")
      (fields (field (name "MF") "MOLEX"))
      (libsource (lib "eagle-import") (part "22-23-2031"))
    )
    (comp (ref "Z1")
      (value "DIODE-SOD123")
      (footprint "eagle-import:SOD123")
      (libsource (lib "eagle-import") (part "DIODE-SOD123"))
    )
    (comp (ref "Z2")
      (value "DIODE-SOD123")
      (footprint "eagle-import:SOD123")
      (libsource (lib "eagle-import") (part "DIODE-SOD123"))
    )
    (comp (ref "Z3")
      (value "DIODE-SOD123")
      (footprint "eagle-import:SOD123")
      (libsource (lib "eagle-import") (part "DIODE-SOD123"))
    )
    (comp (ref "Z4")
      (value "DIODE-SOD123")
      (footprint "eagle-import:SOD123")
      (libsource (lib "eagle-import") (part "DIODE-SOD123"))
    )
    (comp (ref "Z5")
      (value "DIODE-SOD123")
      (footprint "eagle-import:SOD123")
      (libsource (lib "eagle-import") (part "DIODE-SOD123"))
    )
    (comp (ref "Z6")
      (value "DIODE-SOD123")
      (footprint "eagle-import:SOD123")
      (libsource (lib "eagle-import") (part "DIODE-SOD123"))
    )
    (comp (ref "Z7")
      (value "DIODE-SOD123")
      (footprint "eagle-import:SOD123")
      (libsource (lib "eagle-import") (part "DIODE-SOD123"))
    )
    (comp (ref "Z8")
      (value "DIODE-SOD123")
      (footprint "eagle-import:SOD123")
      (libsource (lib "eagle-import") (part "DIODE-SOD123"))
    )
    (comp (ref "Z9")
      (value "DIODE-SOD123")
      (footprint "eagle-import:SOD123")
      (libsource (lib "eagle-import") (part "DIODE-SOD123"))
    )
    (comp (ref "Z10")
      (value "DIODE-SOD123")
      (footprint "eagle-import:SOD123")
      (libsource (lib "eagle-import") (part "DIODE-SOD123"))
    )
    (comp (ref "Z11")
      (value "DIODE-SOD123")
      (footprint "eagle-import:SOD123")
      (libsource (lib "eagle-import") (part "DIODE-SOD123"))
    )
    (comp (ref "Z12")
      (value "DIODE-SOD123")
      (footprint "eagle-import:SOD123")
      (libsource (lib "eagle-import") (part "DIODE-SOD123"))
    )
    (comp (ref "Z13")
      (value "DIODE-SOD123")
      (footprint "eagle-import:SOD123")
      (libsource (lib "eagle-import") (part "DIODE-SOD123"))
    )
    (comp (ref "Z14")
      (value "DIODE-SOD123")
      (footprint "eagle-import:SOD123")
      (libsource (lib "eagle-import") (part "DIODE-SOD123"))
    )
    (comp (ref "Z15")
      (value "DIODE-SOD123")
      (footprint "eagle-import:SOD123")
      (libsource (lib "eagle-import") (part "DIODE-SOD123"))
    )
    (comp (ref "Z16")
      (value "DIODE-SOD123")
      (footprint "eagle-import:SOD123")
      (libsource (lib "eagle-import") (part "DIODE-SOD123"))
    )
    (comp (ref "Z17")
      (value "DIODE-SOD123")
      (footprint "eagle-import:SOD123")
      (libsource (lib "eagle-import") (part "DIODE-SOD123"))
    )
    (comp (ref "Z18")
      (value "DIODE-SOD123")
      (footprint "eagle-import:SOD123")
      (libsource (lib "eagle-import") (part "DIODE-SOD123"))
    )
    (comp (ref "Z19")
      (value "DIODE-SOD123")
      (footprint "eagle-import:SOD123")
      (libsource (lib "eagle-import") (part "DIODE-SOD123"))
    )
    (comp (ref "Z20")
      (value "DIODE-SOD123")
      (footprint "eagle-import:SOD123")
      (libsource (lib "eagle-import") (part "DIODE-SOD123"))
    )
    (comp (ref "Z21")
      (value "DIODE-SOD123")
      (footprint "eagle-import:SOD123")
      (libsource (lib "eagle-import") (part "DIODE-SOD123"))
    )
    (comp (ref "Z22")
      (value "DIODE-SOD123")
      (footprint "eagle-import:SOD123")
      (libsource (lib "eagle-import") (part "DIODE-SOD123"))
    )
    (comp (ref "Z23")
      (value "DIODE-SOD123")
      (footprint "eagle-import:SOD123")
      (libsource (lib "eagle-import") (part "DIODE-SOD123"))
    )
    (comp (ref "Z24")
      (value "DIODE-SOD123")
      (footprint "eagle-import:SOD123")
      (libsource (lib "eagle-import") (part "DIODE-SOD123"))
    )
    (comp (ref "Z25")
      (value "DIODE-SOD123")
      (footprint "eagle-import:SOD123")
      (libsource (lib "eagle-import") (part "DIODE-SOD123"))
    )
    (comp (ref "Z26")
      (value "DIODE-SOD123")
      (footprint "eagle-import:SOD123")
      (libsource (lib "eagle-import") (part "DIODE-SOD123"))
    )
    (comp (ref "Z27")
      (value "DIODE-SOD123")
      (footprint "eagle-import:SOD123")
      (libsource (lib "eagle-import") (part "DIODE-SOD123"))
    )
    (comp (ref "Z28")
      (value "DIODE-SOD123")
      (footprint "eagle-import:SOD123")
      (libsource (lib "eagle-import") (part "DIODE-SOD123"))
    )
    (comp (ref "Z29")
      (value "DIODE-SOD123")
      (footprint "eagle-import:SOD123")
      (libsource (lib "eagle-import") (part "DIODE-SOD123"))
    )
    (comp (ref "Z30")
      (value "DIODE-SOD123")
      (footprint "eagle-import:SOD123")
      (libsource (lib "eagle-import") (part "DIODE-SOD123"))
    )
    (comp (ref "Z31")
      (value "DIODE-SOD123")
      (footprint "eagle-import:SOD123")
      (libsource (lib "eagle-import") (part "DIODE-SOD123"))
    )
    (comp (ref "Z32")
      (value "DIODE-SOD123")
      (footprint "eagle-import:SOD123")
      (libsource (lib "eagle-import") (part "DIODE-SOD123"))
    )
    (comp (ref "Z33")
      (value "DIODE-SOD123")
      (footprint "eagle-import:SOD123")
      (libsource (lib "eagle-import") (part "DIODE-SOD123"))
    )
    (comp (ref "Z34")
      (value "DIODE-SOD123")
      (footprint "eagle-import:SOD123")
      (libsource (lib "eagle-import") (part "DIODE-SOD123"))
    )
    (comp (ref "Z35")
      (value "DIODE-SOD123")
      (footprint "eagle-import:SOD123")
      (libsource (lib "eagle-import") (part "DIODE-SOD123"))
    )
    (comp (ref "Z36")
      (value "DIODE-SOD123")
      (footprint "eagle-import:SOD123")
      (libsource (lib "eagle-import") (part "DIODE-SOD123"))
    )
    (comp (ref "Z37")
      (value "DIODE-SOD123")
      (footprint "eagle-import:SOD123")
      (libsource (lib "eagle-import") (part "DIODE-SOD123"))
    )
    (comp (ref "Z38")
      (value "DIODE-SOD123")
      (footprint "eagle-import:SOD123")
      (libsource (lib "eagle-import") (part "DIODE-SOD123"))
    )
    (comp (ref "Z39")
      (value "DIODE-SOD123")
      (footprint "eagle-import:SOD123")
      (libsource (lib "eagle-import") (part "DIODE-SOD123"))
    )
    (comp (ref "Z40")
      (value "DIODE-SOD123")
      (footprint "eagle-import:SOD123")
      (libsource (lib "eagle-import") (part "DIODE-SOD123"))
    )
    (comp (ref "Z41")
      (value "DIODE-SOD123")
      (footprint "eagle-import:SOD123")
      (libsource (lib "eagle-import") (part "DIODE-SOD123"))
    )
    (comp (ref "Z42")
      (value "DIODE-SOD123")
      (footprint "eagle-import:SOD123")
      (libsource (lib "eagle-import") (part "DIODE-SOD123"))
    )
    (comp (ref "Z43")
      (value "DIODE-SOD123")
      (footprint "eagle-import:SOD123")
      (libsource (lib "eagle-import") (part "DIODE-SOD123"))
    )
    (comp (ref "Z44")
      (value "DIODE-SOD123")
      (footprint "eagle-import:SOD123")
      (libsource (lib "eagle-import") (part "DIODE-SOD123"))
    )
    (comp (ref "Z45")
      (value "DIODE-SOD123")
      (footprint "eagle-import:SOD123")
      (libsource (lib "eagle-import") (part "DIODE-SOD123"))
    )
    (comp (ref "Z46")
      (value "DIODE-SOD123")
      (footprint "eagle-import:SOD123")
      (libsource (lib "eagle-import") (part "DIODE-SOD123"))
    )
    (comp (ref "Z47")
      (value "DIODE-SOD123")
      (footprint "eagle-import:SOD123")
      (libsource (lib "eagle-import") (part "DIODE-SOD123"))
    )
    (comp (ref "Z48")
      (value "DIODE-SOD123")
      (footprint "eagle-import:SOD123")
      (libsource (lib "eagle-import") (part "DIODE-SOD123"))
    )
  )
  (nets
    (net (code "1") (name "/NC") (class "Default")
      (node (ref "K1") (pin "NC") (pinfunction "NC_NC") (pintype "passive"))
    )
    (net (code "2") (name "/OUT1") (class "Default")
      (node (ref "IC4") (pin "21") (pinfunction "GPA0_21") (pintype "bidirectional"))
      (node (ref "OPTO1") (pin "4") (pinfunction "CT_4") (pintype "passive"))
      (node (ref "R49") (pin "1") (pinfunction "1_1") (pintype "passive"))
    )
    (net (code "3") (name "/OUT2") (class "Default")
      (node (ref "IC4") (pin "22") (pinfunction "GPA1_22") (pintype "bidirectional"))
      (node (ref "OPTO2") (pin "4") (pinfunction "CT_4") (pintype "passive"))
      (node (ref "R50") (pin "1") (pinfunction "1_1") (pintype "passive"))
    )
    (net (code "4") (name "/OUT3") (class "Default")
      (node (ref "IC4") (pin "23") (pinfunction "GPA2_23") (pintype "bidirectional"))
      (node (ref "OPTO3") (pin "4") (pinfunction "CT_4") (pintype "passive"))
      (node (ref "R51") (pin "1") (pinfunction "1_1") (pintype "passive"))
    )
    (net (code "5") (name "/OUT4") (class "Default")
      (node (ref "IC4") (pin "24") (pinfunction "GPA3_24") (pintype "bidirectional"))
      (node (ref "OPTO4") (pin "4") (pinfunction "CT_4") (pintype "passive"))
      (node (ref "R52") (pin "1") (pinfunction "1_1") (pintype "passive"))
    )
    (net (code "6") (name "/OUT5") (class "Default")
      (node (ref "IC4") (pin "25") (pinfunction "GPA4_25") (pintype "bidirectional"))
      (node (ref "OPTO5") (pin "4") (pinfunction "CT_4") (pintype "passive"))
      (node (ref "R53") (pin "1") (pinfunction "1_1") (pintype "passive"))
    )
    (net (code "7") (name "/OUT6") (class "Default")
      (node (ref "IC4") (pin "26") (pinfunction "GPA5_26") (pintype "bidirectional"))
      (node (ref "OPTO6") (pin "4") (pinfunction "CT_4") (pintype "passive"))
      (node (ref "R54") (pin "1") (pinfunction "1_1") (pintype "passive"))
    )
    (net (code "8") (name "/OUT7") (class "Default")
      (node (ref "IC4") (pin "27") (pinfunction "GPA6_27") (pintype "bidirectional"))
      (node (ref "OPTO7") (pin "4") (pinfunction "CT_4") (pintype "passive"))
      (node (ref "R55") (pin "1") (pinfunction "1_1") (pintype "passive"))
    )
    (net (code "9") (name "/OUT8") (class "Default")
      (node (ref "IC4") (pin "28") (pinfunction "GPA7_28") (pintype "bidirectional"))
      (node (ref "OPTO8") (pin "4") (pinfunction "CT_4") (pintype "passive"))
      (node (ref "R56") (pin "1") (pinfunction "1_1") (pintype "passive"))
    )
    (net (code "10") (name "/OUT9") (class "Default")
      (node (ref "IC4") (pin "1") (pinfunction "GPB0_1") (pintype "bidirectional"))
      (node (ref "OPTO9") (pin "4") (pinfunction "CT_4") (pintype "passive"))
      (node (ref "R57") (pin "1") (pinfunction "1_1") (pintype "passive"))
    )
    (net (code "11") (name "/OUT10") (class "Default")
      (node (ref "IC4") (pin "2") (pinfunction "GPB1_2") (pintype "bidirectional"))
      (node (ref "OPTO10") (pin "4") (pinfunction "CT_4") (pintype "passive"))
      (node (ref "R58") (pin "1") (pinfunction "1_1") (pintype "passive"))
    )
    (net (code "12") (name "/OUT11") (class "Default")
      (node (ref "IC4") (pin "3") (pinfunction "GPB2_3") (pintype "bidirectional"))
      (node (ref "OPTO11") (pin "4") (pinfunction "CT_4") (pintype "passive"))
      (node (ref "R59") (pin "1") (pinfunction "1_1") (pintype "passive"))
    )
    (net (code "13") (name "/OUT12") (class "Default")
      (node (ref "IC4") (pin "4") (pinfunction "GPB3_4") (pintype "bidirectional"))
      (node (ref "OPTO12") (pin "4") (pinfunction "CT_4") (pintype "passive"))
      (node (ref "R60") (pin "1") (pinfunction "1_1") (pintype "passive"))
    )
    (net (code "14") (name "/OUT13") (class "Default")
      (node (ref "IC4") (pin "5") (pinfunction "GPB4_5") (pintype "bidirectional"))
      (node (ref "OPTO13") (pin "4") (pinfunction "CT_4") (pintype "passive"))
      (node (ref "R61") (pin "1") (pinfunction "1_1") (pintype "passive"))
    )
    (net (code "15") (name "/OUT14") (class "Default")
      (node (ref "IC4") (pin "6") (pinfunction "GPB5_6") (pintype "bidirectional"))
      (node (ref "OPTO14") (pin "4") (pinfunction "CT_4") (pintype "passive"))
      (node (ref "R62") (pin "1") (pinfunction "1_1") (pintype "passive"))
    )
    (net (code "16") (name "/OUT15") (class "Default")
      (node (ref "IC4") (pin "7") (pinfunction "GPB6_7") (pintype "bidirectional"))
      (node (ref "OPTO15") (pin "4") (pinfunction "CT_4") (pintype "passive"))
      (node (ref "R63") (pin "1") (pinfunction "1_1") (pintype "passive"))
    )
    (net (code "17") (name "/OUT16") (class "Default")
      (node (ref "IC4") (pin "8") (pinfunction "GPB7_8") (pintype "bidirectional"))
      (node (ref "OPTO16") (pin "4") (pinfunction "CT_4") (pintype "passive"))
      (node (ref "R64") (pin "1") (pinfunction "1_1") (pintype "passive"))
    )
    (net (code "18") (name "/OUT17") (class "Default")
      (node (ref "IC1") (pin "21") (pinfunction "GPA0_21") (pintype "bidirectional"))
      (node (ref "OPTO17") (pin "4") (pinfunction "CT_4") (pintype "passive"))
      (node (ref "R65") (pin "1") (pinfunction "1_1") (pintype "passive"))
    )
    (net (code "19") (name "/OUT18") (class "Default")
      (node (ref "IC1") (pin "22") (pinfunction "GPA1_22") (pintype "bidirectional"))
      (node (ref "OPTO18") (pin "4") (pinfunction "CT_4") (pintype "passive"))
      (node (ref "R66") (pin "1") (pinfunction "1_1") (pintype "passive"))
    )
    (net (code "20") (name "/OUT19") (class "Default")
      (node (ref "IC1") (pin "23") (pinfunction "GPA2_23") (pintype "bidirectional"))
      (node (ref "OPTO19") (pin "4") (pinfunction "CT_4") (pintype "passive"))
      (node (ref "R67") (pin "1") (pinfunction "1_1") (pintype "passive"))
    )
    (net (code "21") (name "/OUT20") (class "Default")
      (node (ref "IC1") (pin "24") (pinfunction "GPA3_24") (pintype "bidirectional"))
      (node (ref "OPTO20") (pin "4") (pinfunction "CT_4") (pintype "passive"))
      (node (ref "R68") (pin "1") (pinfunction "1_1") (pintype "passive"))
    )
    (net (code "22") (name "/OUT21") (class "Default")
      (node (ref "IC1") (pin "25") (pinfunction "GPA4_25") (pintype "bidirectional"))
      (node (ref "OPTO21") (pin "4") (pinfunction "CT_4") (pintype "passive"))
      (node (ref "R69") (pin "1") (pinfunction "1_1") (pintype "passive"))
    )
    (net (code "23") (name "/OUT22") (class "Default")
      (node (ref "IC1") (pin "26") (pinfunction "GPA5_26") (pintype "bidirectional"))
      (node (ref "OPTO22") (pin "4") (pinfunction "CT_4") (pintype "passive"))
      (node (ref "R70") (pin "1") (pinfunction "1_1") (pintype "passive"))
    )
    (net (code "24") (name "/OUT23") (class "Default")
      (node (ref "IC1") (pin "27") (pinfunction "GPA6_27") (pintype "bidirectional"))
      (node (ref "OPTO23") (pin "4") (pinfunction "CT_4") (pintype "passive"))
      (node (ref "R71") (pin "1") (pinfunction "1_1") (pintype "passive"))
    )
    (net (code "25") (name "/OUT24") (class "Default")
      (node (ref "IC1") (pin "28") (pinfunction "GPA7_28") (pintype "bidirectional"))
      (node (ref "OPTO24") (pin "4") (pinfunction "CT_4") (pintype "passive"))
      (node (ref "R72") (pin "1") (pinfunction "1_1") (pintype "passive"))
    )
    (net (code "26") (name "/OUT25") (class "Default")
      (node (ref "IC1") (pin "1") (pinfunction "GPB0_1") (pintype "bidirectional"))
      (node (ref "OPTO25") (pin "4") (pinfunction "CT_4") (pintype "passive"))
      (node (ref "R73") (pin "1") (pinfunction "1_1") (pintype "passive"))
    )
    (net (code "27") (name "/OUT26") (class "Default")
      (node (ref "IC1") (pin "2") (pinfunction "GPB1_2") (pintype "bidirectional"))
      (node (ref "OPTO26") (pin "4") (pinfunction "CT_4") (pintype "passive"))
      (node (ref "R74") (pin "1") (pinfunction "1_1") (pintype "passive"))
    )
    (net (code "28") (name "/OUT27") (class "Default")
      (node (ref "IC1") (pin "3") (pinfunction "GPB2_3") (pintype "bidirectional"))
      (node (ref "OPTO27") (pin "4") (pinfunction "CT_4") (pintype "passive"))
      (node (ref "R75") (pin "1") (pinfunction "1_1") (pintype "passive"))
    )
    (net (code "29") (name "/OUT28") (class "Default")
      (node (ref "IC1") (pin "4") (pinfunction "GPB3_4") (pintype "bidirectional"))
      (node (ref "OPTO28") (pin "4") (pinfunction "CT_4") (pintype "passive"))
      (node (ref "R76") (pin "1") (pinfunction "1_1") (pintype "passive"))
    )
    (net (code "30") (name "/OUT29") (class "Default")
      (node (ref "IC1") (pin "5") (pinfunction "GPB4_5") (pintype "bidirectional"))
      (node (ref "OPTO29") (pin "4") (pinfunction "CT_4") (pintype "passive"))
      (node (ref "R77") (pin "1") (pinfunction "1_1") (pintype "passive"))
    )
    (net (code "31") (name "/OUT30") (class "Default")
      (node (ref "IC1") (pin "6") (pinfunction "GPB5_6") (pintype "bidirectional"))
      (node (ref "OPTO30") (pin "4") (pinfunction "CT_4") (pintype "passive"))
      (node (ref "R78") (pin "1") (pinfunction "1_1") (pintype "passive"))
    )
    (net (code "32") (name "/OUT31") (class "Default")
      (node (ref "IC1") (pin "7") (pinfunction "GPB6_7") (pintype "bidirectional"))
      (node (ref "OPTO31") (pin "4") (pinfunction "CT_4") (pintype "passive"))
      (node (ref "R79") (pin "1") (pinfunction "1_1") (pintype "passive"))
    )
    (net (code "33") (name "/OUT32") (class "Default")
      (node (ref "IC1") (pin "8") (pinfunction "GPB7_8") (pintype "bidirectional"))
      (node (ref "OPTO32") (pin "4") (pinfunction "CT_4") (pintype "passive"))
      (node (ref "R80") (pin "1") (pinfunction "1_1") (pintype "passive"))
    )
    (net (code "34") (name "/OUT33") (class "Default")
      (node (ref "IC5") (pin "21") (pinfunction "GPA0_21") (pintype "bidirectional"))
      (node (ref "OPTO33") (pin "4") (pinfunction "CT_4") (pintype "passive"))
      (node (ref "R81") (pin "1") (pinfunction "1_1") (pintype "passive"))
    )
    (net (code "35") (name "/OUT34") (class "Default")
      (node (ref "IC5") (pin "22") (pinfunction "GPA1_22") (pintype "bidirectional"))
      (node (ref "OPTO34") (pin "4") (pinfunction "CT_4") (pintype "passive"))
      (node (ref "R82") (pin "1") (pinfunction "1_1") (pintype "passive"))
    )
    (net (code "36") (name "/OUT35") (class "Default")
      (node (ref "IC5") (pin "23") (pinfunction "GPA2_23") (pintype "bidirectional"))
      (node (ref "OPTO35") (pin "4") (pinfunction "CT_4") (pintype "passive"))
      (node (ref "R83") (pin "1") (pinfunction "1_1") (pintype "passive"))
    )
    (net (code "37") (name "/OUT36") (class "Default")
      (node (ref "IC5") (pin "24") (pinfunction "GPA3_24") (pintype "bidirectional"))
      (node (ref "OPTO36") (pin "4") (pinfunction "CT_4") (pintype "passive"))
      (node (ref "R84") (pin "1") (pinfunction "1_1") (pintype "passive"))
    )
    (net (code "38") (name "/OUT37") (class "Default")
      (node (ref "IC5") (pin "25") (pinfunction "GPA4_25") (pintype "bidirectional"))
      (node (ref "OPTO37") (pin "4") (pinfunction "CT_4") (pintype "passive"))
      (node (ref "R85") (pin "1") (pinfunction "1_1") (pintype "passive"))
    )
    (net (code "39") (name "/OUT38") (class "Default")
      (node (ref "IC5") (pin "26") (pinfunction "GPA5_26") (pintype "bidirectional"))
      (node (ref "OPTO38") (pin "4") (pinfunction "CT_4") (pintype "passive"))
      (node (ref "R86") (pin "1") (pinfunction "1_1") (pintype "passive"))
    )
    (net (code "40") (name "/OUT39") (class "Default")
      (node (ref "IC5") (pin "27") (pinfunction "GPA6_27") (pintype "bidirectional"))
      (node (ref "OPTO39") (pin "4") (pinfunction "CT_4") (pintype "passive"))
      (node (ref "R87") (pin "1") (pinfunction "1_1") (pintype "passive"))
    )
    (net (code "41") (name "/OUT40") (class "Default")
      (node (ref "IC5") (pin "28") (pinfunction "GPA7_28") (pintype "bidirectional"))
      (node (ref "OPTO40") (pin "4") (pinfunction "CT_4") (pintype "passive"))
      (node (ref "R88") (pin "1") (pinfunction "1_1") (pintype "passive"))
    )
    (net (code "42") (name "/OUT41") (class "Default")
      (node (ref "IC5") (pin "1") (pinfunction "GPB0_1") (pintype "bidirectional"))
      (node (ref "OPTO41") (pin "4") (pinfunction "CT_4") (pintype "passive"))
      (node (ref "R89") (pin "1") (pinfunction "1_1") (pintype "passive"))
    )
    (net (code "43") (name "/OUT42") (class "Default")
      (node (ref "IC5") (pin "2") (pinfunction "GPB1_2") (pintype "bidirectional"))
      (node (ref "OPTO42") (pin "4") (pinfunction "CT_4") (pintype "passive"))
      (node (ref "R90") (pin "1") (pinfunction "1_1") (pintype "passive"))
    )
    (net (code "44") (name "/OUT43") (class "Default")
      (node (ref "IC5") (pin "3") (pinfunction "GPB2_3") (pintype "bidirectional"))
      (node (ref "OPTO43") (pin "4") (pinfunction "CT_4") (pintype "passive"))
      (node (ref "R91") (pin "1") (pinfunction "1_1") (pintype "passive"))
    )
    (net (code "45") (name "/OUT44") (class "Default")
      (node (ref "IC5") (pin "4") (pinfunction "GPB3_4") (pintype "bidirectional"))
      (node (ref "OPTO44") (pin "4") (pinfunction "CT_4") (pintype "passive"))
      (node (ref "R92") (pin "1") (pinfunction "1_1") (pintype "passive"))
    )
    (net (code "46") (name "/OUT45") (class "Default")
      (node (ref "IC5") (pin "5") (pinfunction "GPB4_5") (pintype "bidirectional"))
      (node (ref "OPTO45") (pin "4") (pinfunction "CT_4") (pintype "passive"))
      (node (ref "R93") (pin "1") (pinfunction "1_1") (pintype "passive"))
    )
    (net (code "47") (name "/OUT46") (class "Default")
      (node (ref "IC5") (pin "6") (pinfunction "GPB5_6") (pintype "bidirectional"))
      (node (ref "OPTO46") (pin "4") (pinfunction "CT_4") (pintype "passive"))
      (node (ref "R94") (pin "1") (pinfunction "1_1") (pintype "passive"))
    )
    (net (code "48") (name "/OUT47") (class "Default")
      (node (ref "IC5") (pin "7") (pinfunction "GPB6_7") (pintype "bidirectional"))
      (node (ref "OPTO47") (pin "4") (pinfunction "CT_4") (pintype "passive"))
      (node (ref "R95") (pin "1") (pinfunction "1_1") (pintype "passive"))
    )
    (net (code "49") (name "/OUT48") (class "Default")
      (node (ref "IC5") (pin "8") (pinfunction "GPB7_8") (pintype "bidirectional"))
      (node (ref "OPTO48") (pin "4") (pinfunction "CT_4") (pintype "passive"))
      (node (ref "R96") (pin "1") (pinfunction "1_1") (pintype "passive"))
    )
    (net (code "50") (name "/P1") (class "Default")
      (node (ref "HEADER-29P1") (pin "1") (pinfunction "1_1") (pintype "bidirectional"))
      (node (ref "R1") (pin "1") (pinfunction "1_1") (pintype "passive"))
    )
    (net (code "51") (name "/P2") (class "Default")
      (node (ref "HEADER-29P1") (pin "2") (pinfunction "2_2") (pintype "bidirectional"))
      (node (ref "R2") (pin "1") (pinfunction "1_1") (pintype "passive"))
    )
    (net (code "52") (name "/P3") (class "Default")
      (node (ref "HEADER-29P1") (pin "3") (pinfunction "3_3") (pintype "bidirectional"))
      (node (ref "R3") (pin "1") (pinfunction "1_1") (pintype "passive"))
    )
    (net (code "53") (name "/P4") (class "Default")
      (node (ref "HEADER-29P1") (pin "4") (pinfunction "4_4") (pintype "bidirectional"))
      (node (ref "R4") (pin "1") (pinfunction "1_1") (pintype "passive"))
    )
    (net (code "54") (name "/P5") (class "Default")
      (node (ref "HEADER-29P1") (pin "5") (pinfunction "5_5") (pintype "bidirectional"))
      (node (ref "R5") (pin "1") (pinfunction "1_1") (pintype "passive"))
    )
    (net (code "55") (name "/P6") (class "Default")
      (node (ref "HEADER-29P1") (pin "6") (pinfunction "6_6") (pintype "bidirectional"))
      (node (ref "R6") (pin "1") (pinfunction "1_1") (pintype "passive"))
    )
    (net (code "56") (name "/P7") (class "Default")
      (node (ref "HEADER-29P1") (pin "7") (pinfunction "7_7") (pintype "bidirectional"))
      (node (ref "R7") (pin "1") (pinfunction "1_1") (pintype "passive"))
    )
    (net (code "57") (name "/P8") (class "Default")
      (node (ref "HEADER-29P1") (pin "8") (pinfunction "8_8") (pintype "bidirectional"))
      (node (ref "R8") (pin "1") (pinfunction "1_1") (pintype "passive"))
    )
    (net (code "58") (name "/P9") (class "Default")
      (node (ref "HEADER-29P1") (pin "9") (pinfunction "9_9") (pintype "bidirectional"))
      (node (ref "R9") (pin "1") (pinfunction "1_1") (pintype "passive"))
    )
    (net (code "59") (name "/P10") (class "Default")
      (node (ref "HEADER-29P1") (pin "10") (pinfunction "10_10") (pintype "bidirectional"))
      (node (ref "R10") (pin "1") (pinfunction "1_1") (pintype "passive"))
    )
    (net (code "60") (name "/P11") (class "Default")
      (node (ref "HEADER-29P1") (pin "11") (pinfunction "11_11") (pintype "bidirectional"))
      (node (ref "R11") (pin "1") (pinfunction "1_1") (pintype "passive"))
    )
    (net (code "61") (name "/P12") (class "Default")
      (node (ref "HEADER-29P1") (pin "12") (pinfunction "12_12") (pintype "bidirectional"))
      (node (ref "R12") (pin "1") (pinfunction "1_1") (pintype "passive"))
    )
    (net (code "62") (name "/P13") (class "Default")
      (node (ref "HEADER-29P1") (pin "13") (pinfunction "13_13") (pintype "bidirectional"))
      (node (ref "R13") (pin "1") (pinfunction "1_1") (pintype "passive"))
    )
    (net (code "63") (name "/P14") (class "Default")
      (node (ref "HEADER-29P1") (pin "14") (pinfunction "14_14") (pintype "bidirectional"))
      (node (ref "R14") (pin "1") (pinfunction "1_1") (pintype "passive"))
    )
    (net (code "64") (name "/P15") (class "Default")
      (node (ref "HEADER-29P1") (pin "15") (pinfunction "15_15") (pintype "bidirectional"))
      (node (ref "R15") (pin "1") (pinfunction "1_1") (pintype "passive"))
    )
    (net (code "65") (name "/P16") (class "Default")
      (node (ref "HEADER-29P1") (pin "16") (pinfunction "16_16") (pintype "bidirectional"))
      (node (ref "R16") (pin "1") (pinfunction "1_1") (pintype "passive"))
    )
    (net (code "66") (name "/P17") (class "Default")
      (node (ref "HEADER-29P1") (pin "17") (pinfunction "17_17") (pintype "bidirectional"))
      (node (ref "R17") (pin "1") (pinfunction "1_1") (pintype "passive"))
    )
    (net (code "67") (name "/P18") (class "Default")
      (node (ref "HEADER-29P1") (pin "18") (pinfunction "18_18") (pintype "bidirectional"))
      (node (ref "R18") (pin "1") (pinfunction "1_1") (pintype "passive"))
    )
    (net (code "68") (name "/P19") (class "Default")
      (node (ref "HEADER-29P1") (pin "19") (pinfunction "19_19") (pintype "bidirectional"))
      (node (ref "R19") (pin "1") (pinfunction "1_1") (pintype "passive"))
    )
    (net (code "69") (name "/P20") (class "Default")
      (node (ref "HEADER-29P1") (pin "20") (pinfunction "20_20") (pintype "bidirectional"))
      (node (ref "R20") (pin "1") (pinfunction "1_1") (pintype "passive"))
    )
    (net (code "70") (name "/P21") (class "Default")
      (node (ref "HEADER-29P1") (pin "21") (pinfunction "21_21") (pintype "bidirectional"))
      (node (ref "R21") (pin "1") (pinfunction "1_1") (pintype "passive"))
    )
    (net (code "71") (name "/P22") (class "Default")
      (node (ref "HEADER-29P1") (pin "22") (pinfunction "22_22") (pintype "bidirectional"))
      (node (ref "R22") (pin "1") (pinfunction "1_1") (pintype "passive"))
    )
    (net (code "72") (name "/P23") (class "Default")
      (node (ref "HEADER-29P1") (pin "23") (pinfunction "23_23") (pintype "bidirectional"))
      (node (ref "R23") (pin "1") (pinfunction "1_1") (pintype "passive"))
    )
    (net (code "73") (name "/P24") (class "Default")
      (node (ref "HEADER-29P1") (pin "24") (pinfunction "24_24") (pintype "bidirectional"))
      (node (ref "R24") (pin "1") (pinfunction "1_1") (pintype "passive"))
    )
    (net (code "74") (name "/P25") (class "Default")
      (node (ref "HEADER-29P1") (pin "25") (pinfunction "25_25") (pintype "bidirectional"))
      (node (ref "R25") (pin "1") (pinfunction "1_1") (pintype "passive"))
    )
    (net (code "75") (name "/P26") (class "Default")
      (node (ref "HEADER-29P1") (pin "26") (pinfunction "26_26") (pintype "bidirectional"))
      (node (ref "R26") (pin "1") (pinfunction "1_1") (pintype "passive"))
    )
    (net (code "76") (name "/P27") (class "Default")
      (node (ref "HEADER-29P1") (pin "27") (pinfunction "27_27") (pintype "bidirectional"))
      (node (ref "R27") (pin "1") (pinfunction "1_1") (pintype "passive"))
    )
    (net (code "77") (name "/P28") (class "Default")
      (node (ref "HEADER-29P1") (pin "28") (pinfunction "28_28") (pintype "bidirectional"))
      (node (ref "R28") (pin "1") (pinfunction "1_1") (pintype "passive"))
    )
    (net (code "78") (name "/P29") (class "Default")
      (node (ref "HEADER-29P1") (pin "29") (pinfunction "29_29") (pintype "bidirectional"))
      (node (ref "R29") (pin "1") (pinfunction "1_1") (pintype "passive"))
    )
    (net (code "79") (name "/RESET") (class "Default")
      (node (ref "IC1") (pin "18") (pinfunction "~{RESET}_18") (pintype "input"))
      (node (ref "IC4") (pin "18") (pinfunction "~{RESET}_18") (pintype "input"))
      (node (ref "IC5") (pin "18") (pinfunction "~{RESET}_18") (pintype "input"))
      (node (ref "R103") (pin "2") (pinfunction "2_2") (pintype "passive"))
      (node (ref "R107") (pin "1") (pinfunction "1_1") (pintype "passive"))
      (node (ref "R111") (pin "2") (pinfunction "2_2") (pintype "passive"))
    )
    (net (code "80") (name "24+") (class "Default")
      (node (ref "HEADER-29P2") (pin "4") (pinfunction "4_4") (pintype "bidirectional"))
      (node (ref "MT1") (pin "VOUT+") (pinfunction "VOUT+_VOUT+") (pintype "bidirectional"))
      (node (ref "X1") (pin "1") (pinfunction "S_1") (pintype "passive"))
    )
    (net (code "81") (name "A+") (class "Default")
      (node (ref "HEADER-29P2") (pin "6") (pinfunction "6_6") (pintype "bidirectional"))
      (node (ref "TTL-RS1") (pin "A") (pinfunction "A_A") (pintype "bidirectional"))
    )
    (net (code "82") (name "B-") (class "Default")
      (node (ref "HEADER-29P2") (pin "5") (pinfunction "5_5") (pintype "bidirectional"))
      (node (ref "TTL-RS1") (pin "B") (pinfunction "B_B") (pintype "bidirectional"))
    )
    (net (code "83") (name "COMM") (class "Default")
      (node (ref "HEADER-29P2") (pin "27") (pinfunction "27_27") (pintype "bidirectional"))
      (node (ref "K2") (pin "O1") (pinfunction "O_O1") (pintype "passive"))
    )
    (net (code "84") (name "COMM1") (class "Default")
      (node (ref "K2") (pin "P1") (pinfunction "P_P1") (pintype "passive"))
      (node (ref "OPTO1") (pin "2") (pinfunction "C_2") (pintype "passive"))
      (node (ref "OPTO10") (pin "2") (pinfunction "C_2") (pintype "passive"))
      (node (ref "OPTO11") (pin "2") (pinfunction "C_2") (pintype "passive"))
      (node (ref "OPTO12") (pin "2") (pinfunction "C_2") (pintype "passive"))
      (node (ref "OPTO13") (pin "2") (pinfunction "C_2") (pintype "passive"))
      (node (ref "OPTO14") (pin "2") (pinfunction "C_2") (pintype "passive"))
      (node (ref "OPTO15") (pin "2") (pinfunction "C_2") (pintype "passive"))
      (node (ref "OPTO16") (pin "2") (pinfunction "C_2") (pintype "passive"))
      (node (ref "OPTO17") (pin "2") (pinfunction "C_2") (pintype "passive"))
      (node (ref "OPTO18") (pin "2") (pinfunction "C_2") (pintype "passive"))
      (node (ref "OPTO19") (pin "2") (pinfunction "C_2") (pintype "passive"))
      (node (ref "OPTO2") (pin "2") (pinfunction "C_2") (pintype "passive"))
      (node (ref "OPTO20") (pin "2") (pinfunction "C_2") (pintype "passive"))
      (node (ref "OPTO21") (pin "2") (pinfunction "C_2") (pintype "passive"))
      (node (ref "OPTO22") (pin "2") (pinfunction "C_2") (pintype "passive"))
      (node (ref "OPTO23") (pin "2") (pinfunction "C_2") (pintype "passive"))
      (node (ref "OPTO24") (pin "2") (pinfunction "C_2") (pintype "passive"))
      (node (ref "OPTO25") (pin "2") (pinfunction "C_2") (pintype "passive"))
      (node (ref "OPTO26") (pin "2") (pinfunction "C_2") (pintype "passive"))
      (node (ref "OPTO27") (pin "2") (pinfunction "C_2") (pintype "passive"))
      (node (ref "OPTO28") (pin "2") (pinfunction "C_2") (pintype "passive"))
      (node (ref "OPTO29") (pin "2") (pinfunction "C_2") (pintype "passive"))
      (node (ref "OPTO3") (pin "2") (pinfunction "C_2") (pintype "passive"))
      (node (ref "OPTO30") (pin "2") (pinfunction "C_2") (pintype "passive"))
      (node (ref "OPTO31") (pin "2") (pinfunction "C_2") (pintype "passive"))
      (node (ref "OPTO32") (pin "2") (pinfunction "C_2") (pintype "passive"))
      (node (ref "OPTO33") (pin "2") (pinfunction "C_2") (pintype "passive"))
      (node (ref "OPTO34") (pin "2") (pinfunction "C_2") (pintype "passive"))
      (node (ref "OPTO35") (pin "2") (pinfunction "C_2") (pintype "passive"))
      (node (ref "OPTO36") (pin "2") (pinfunction "C_2") (pintype "passive"))
      (node (ref "OPTO37") (pin "2") (pinfunction "C_2") (pintype "passive"))
      (node (ref "OPTO38") (pin "2") (pinfunction "C_2") (pintype "passive"))
      (node (ref "OPTO39") (pin "2") (pinfunction "C_2") (pintype "passive"))
      (node (ref "OPTO4") (pin "2") (pinfunction "C_2") (pintype "passive"))
      (node (ref "OPTO40") (pin "2") (pinfunction "C_2") (pintype "passive"))
      (node (ref "OPTO41") (pin "2") (pinfunction "C_2") (pintype "passive"))
      (node (ref "OPTO42") (pin "2") (pinfunction "C_2") (pintype "passive"))
      (node (ref "OPTO43") (pin "2") (pinfunction "C_2") (pintype "passive"))
      (node (ref "OPTO44") (pin "2") (pinfunction "C_2") (pintype "passive"))
      (node (ref "OPTO45") (pin "2") (pinfunction "C_2") (pintype "passive"))
      (node (ref "OPTO46") (pin "2") (pinfunction "C_2") (pintype "passive"))
      (node (ref "OPTO47") (pin "2") (pinfunction "C_2") (pintype "passive"))
      (node (ref "OPTO48") (pin "2") (pinfunction "C_2") (pintype "passive"))
      (node (ref "OPTO5") (pin "2") (pinfunction "C_2") (pintype "passive"))
      (node (ref "OPTO6") (pin "2") (pinfunction "C_2") (pintype "passive"))
      (node (ref "OPTO7") (pin "2") (pinfunction "C_2") (pintype "passive"))
      (node (ref "OPTO8") (pin "2") (pinfunction "C_2") (pintype "passive"))
      (node (ref "OPTO9") (pin "2") (pinfunction "C_2") (pintype "passive"))
      (node (ref "Z1") (pin "A") (pinfunction "A_A") (pintype "passive"))
      (node (ref "Z10") (pin "A") (pinfunction "A_A") (pintype "passive"))
      (node (ref "Z11") (pin "A") (pinfunction "A_A") (pintype "passive"))
      (node (ref "Z12") (pin "A") (pinfunction "A_A") (pintype "passive"))
      (node (ref "Z13") (pin "A") (pinfunction "A_A") (pintype "passive"))
      (node (ref "Z14") (pin "A") (pinfunction "A_A") (pintype "passive"))
      (node (ref "Z15") (pin "A") (pinfunction "A_A") (pintype "passive"))
      (node (ref "Z16") (pin "A") (pinfunction "A_A") (pintype "passive"))
      (node (ref "Z17") (pin "A") (pinfunction "A_A") (pintype "passive"))
      (node (ref "Z18") (pin "A") (pinfunction "A_A") (pintype "passive"))
      (node (ref "Z19") (pin "A") (pinfunction "A_A") (pintype "passive"))
      (node (ref "Z2") (pin "A") (pinfunction "A_A") (pintype "passive"))
      (node (ref "Z20") (pin "A") (pinfunction "A_A") (pintype "passive"))
      (node (ref "Z21") (pin "A") (pinfunction "A_A") (pintype "passive"))
      (node (ref "Z22") (pin "A") (pinfunction "A_A") (pintype "passive"))
      (node (ref "Z23") (pin "A") (pinfunction "A_A") (pintype "passive"))
      (node (ref "Z24") (pin "A") (pinfunction "A_A") (pintype "passive"))
      (node (ref "Z25") (pin "A") (pinfunction "A_A") (pintype "passive"))
      (node (ref "Z26") (pin "A") (pinfunction "A_A") (pintype "passive"))
      (node (ref "Z27") (pin "A") (pinfunction "A_A") (pintype "passive"))
      (node (ref "Z28") (pin "A") (pinfunction "A_A") (pintype "passive"))
      (node (ref "Z29") (pin "A") (pinfunction "A_A") (pintype "passive"))
      (node (ref "Z3") (pin "A") (pinfunction "A_A") (pintype "passive"))
      (node (ref "Z30") (pin "A") (pinfunction "A_A") (pintype "passive"))
      (node (ref "Z31") (pin "A") (pinfunction "A_A") (pintype "passive"))
      (node (ref "Z32") (pin "A") (pinfunction "A_A") (pintype "passive"))
      (node (ref "Z33") (pin "A") (pinfunction "A_A") (pintype "passive"))
      (node (ref "Z34") (pin "A") (pinfunction "A_A") (pintype "passive"))
      (node (ref "Z35") (pin "A") (pinfunction "A_A") (pintype "passive"))
      (node (ref "Z36") (pin "A") (pinfunction "A_A") (pintype "passive"))
      (node (ref "Z37") (pin "A") (pinfunction "A_A") (pintype "passive"))
      (node (ref "Z38") (pin "A") (pinfunction "A_A") (pintype "passive"))
      (node (ref "Z39") (pin "A") (pinfunction "A_A") (pintype "passive"))
      (node (ref "Z4") (pin "A") (pinfunction "A_A") (pintype "passive"))
      (node (ref "Z40") (pin "A") (pinfunction "A_A") (pintype "passive"))
      (node (ref "Z41") (pin "A") (pinfunction "A_A") (pintype "passive"))
      (node (ref "Z42") (pin "A") (pinfunction "A_A") (pintype "passive"))
      (node (ref "Z43") (pin "A") (pinfunction "A_A") (pintype "passive"))
      (node (ref "Z44") (pin "A") (pinfunction "A_A") (pintype "passive"))
      (node (ref "Z45") (pin "A") (pinfunction "A_A") (pintype "passive"))
      (node (ref "Z46") (pin "A") (pinfunction "A_A") (pintype "passive"))
      (node (ref "Z47") (pin "A") (pinfunction "A_A") (pintype "passive"))
      (node (ref "Z48") (pin "A") (pinfunction "A_A") (pintype "passive"))
      (node (ref "Z5") (pin "A") (pinfunction "A_A") (pintype "passive"))
      (node (ref "Z6") (pin "A") (pinfunction "A_A") (pintype "passive"))
      (node (ref "Z7") (pin "A") (pinfunction "A_A") (pintype "passive"))
      (node (ref "Z8") (pin "A") (pinfunction "A_A") (pintype "passive"))
      (node (ref "Z9") (pin "A") (pinfunction "A_A") (pintype "passive"))
    )
    (net (code "85") (name "COMMON") (class "Default")
      (node (ref "HEADER-29P2") (pin "2") (pinfunction "2_2") (pintype "bidirectional"))
      (node (ref "K1") (pin "COM") (pinfunction "COM_COM") (pintype "passive"))
    )
    (net (code "86") (name "DTR") (class "Default")
      (node (ref "Q3") (pin "2") (pinfunction "E_2") (pintype "passive"))
      (node (ref "R117") (pin "1") (pinfunction "1_1") (pintype "passive"))
      (node (ref "U1") (pin "13") (pinfunction "~{DTR}_13") (pintype "output"))
    )
    (net (code "87") (name "EN") (class "Default")
      (node (ref "C10") (pin "1") (pinfunction "1_1") (pintype "passive"))
      (node (ref "Q2") (pin "3") (pinfunction "C_3") (pintype "passive"))
      (node (ref "R119") (pin "1") (pinfunction "1_1") (pintype "passive"))
      (node (ref "S1") (pin "1") (pinfunction "P_1") (pintype "passive"))
      (node (ref "U3") (pin "3") (pinfunction "EN_3") (pintype "input"))
    )
    (net (code "88") (name "GND") (class "Default")
      (node (ref "C1") (pin "2") (pinfunction "2_2") (pintype "passive"))
      (node (ref "C10") (pin "2") (pinfunction "2_2") (pintype "passive"))
      (node (ref "C11") (pin "2") (pinfunction "2_2") (pintype "passive"))
      (node (ref "C2") (pin "-") (pinfunction "-_-") (pintype "passive"))
      (node (ref "C3") (pin "2") (pinfunction "2_2") (pintype "passive"))
      (node (ref "C4") (pin "1") (pinfunction "1_1") (pintype "passive"))
      (node (ref "C5") (pin "1") (pinfunction "1_1") (pintype "passive"))
      (node (ref "C6") (pin "-") (pinfunction "-_-") (pintype "passive"))
      (node (ref "C7") (pin "2") (pinfunction "2_2") (pintype "passive"))
      (node (ref "C8") (pin "2") (pinfunction "2_2") (pintype "passive"))
      (node (ref "C9") (pin "2") (pinfunction "2_2") (pintype "passive"))
      (node (ref "HEADER-29P2") (pin "3") (pinfunction "3_3") (pintype "bidirectional"))
      (node (ref "IC1") (pin "10") (pinfunction "VSS_10") (pintype "power_in"))
      (node (ref "IC4") (pin "10") (pinfunction "VSS_10") (pintype "power_in"))
      (node (ref "IC5") (pin "10") (pinfunction "VSS_10") (pintype "power_in"))
      (node (ref "J3") (pin "5") (pinfunction "GND_5") (pintype "passive"))
      (node (ref "J3") (pin "S1") (pinfunction "SHIELD_S1") (pintype "passive"))
      (node (ref "J3") (pin "S2") (pinfunction "SHIELD_S2") (pintype "passive"))
      (node (ref "J3") (pin "S3") (pinfunction "SHIELD_S3") (pintype "passive"))
      (node (ref "J3") (pin "S4") (pinfunction "SHIELD_S4") (pintype "passive"))
      (node (ref "J3") (pin "S5") (pinfunction "SHIELD_S5") (pintype "passive"))
      (node (ref "J3") (pin "S6") (pinfunction "SHIELD_S6") (pintype "passive"))
      (node (ref "JP1") (pin "4") (pinfunction "4_4") (pintype "passive"))
      (node (ref "K2") (pin "S1") (pinfunction "S_S1") (pintype "passive"))
      (node (ref "MT1") (pin "VIN-") (pinfunction "VIN-_VIN-") (pintype "bidirectional"))
      (node (ref "MT1") (pin "VOUT-") (pinfunction "VOUT-_VOUT-") (pintype "bidirectional"))
      (node (ref "OPTO1") (pin "3") (pinfunction "ET_3") (pintype "passive"))
      (node (ref "OPTO10") (pin "3") (pinfunction "ET_3") (pintype "passive"))
      (node (ref "OPTO11") (pin "3") (pinfunction "ET_3") (pintype "passive"))
      (node (ref "OPTO12") (pin "3") (pinfunction "ET_3") (pintype "passive"))
      (node (ref "OPTO13") (pin "3") (pinfunction "ET_3") (pintype "passive"))
      (node (ref "OPTO14") (pin "3") (pinfunction "ET_3") (pintype "passive"))
      (node (ref "OPTO15") (pin "3") (pinfunction "ET_3") (pintype "passive"))
      (node (ref "OPTO16") (pin "3") (pinfunction "ET_3") (pintype "passive"))
      (node (ref "OPTO17") (pin "3") (pinfunction "ET_3") (pintype "passive"))
      (node (ref "OPTO18") (pin "3") (pinfunction "ET_3") (pintype "passive"))
      (node (ref "OPTO19") (pin "3") (pinfunction "ET_3") (pintype "passive"))
      (node (ref "OPTO2") (pin "3") (pinfunction "ET_3") (pintype "passive"))
      (node (ref "OPTO20") (pin "3") (pinfunction "ET_3") (pintype "passive"))
      (node (ref "OPTO21") (pin "3") (pinfunction "ET_3") (pintype "passive"))
      (node (ref "OPTO22") (pin "3") (pinfunction "ET_3") (pintype "passive"))
      (node (ref "OPTO23") (pin "3") (pinfunction "ET_3") (pintype "passive"))
      (node (ref "OPTO24") (pin "3") (pinfunction "ET_3") (pintype "passive"))
      (node (ref "OPTO25") (pin "3") (pinfunction "ET_3") (pintype "passive"))
      (node (ref "OPTO26") (pin "3") (pinfunction "ET_3") (pintype "passive"))
      (node (ref "OPTO27") (pin "3") (pinfunction "ET_3") (pintype "passive"))
      (node (ref "OPTO28") (pin "3") (pinfunction "ET_3") (pintype "passive"))
      (node (ref "OPTO29") (pin "3") (pinfunction "ET_3") (pintype "passive"))
      (node (ref "OPTO3") (pin "3") (pinfunction "ET_3") (pintype "passive"))
      (node (ref "OPTO30") (pin "3") (pinfunction "ET_3") (pintype "passive"))
      (node (ref "OPTO31") (pin "3") (pinfunction "ET_3") (pintype "passive"))
      (node (ref "OPTO32") (pin "3") (pinfunction "ET_3") (pintype "passive"))
      (node (ref "OPTO33") (pin "3") (pinfunction "ET_3") (pintype "passive"))
      (node (ref "OPTO34") (pin "3") (pinfunction "ET_3") (pintype "passive"))
      (node (ref "OPTO35") (pin "3") (pinfunction "ET_3") (pintype "passive"))
      (node (ref "OPTO36") (pin "3") (pinfunction "ET_3") (pintype "passive"))
      (node (ref "OPTO37") (pin "3") (pinfunction "ET_3") (pintype "passive"))
      (node (ref "OPTO38") (pin "3") (pinfunction "ET_3") (pintype "passive"))
      (node (ref "OPTO39") (pin "3") (pinfunction "ET_3") (pintype "passive"))
      (node (ref "OPTO4") (pin "3") (pinfunction "ET_3") (pintype "passive"))
      (node (ref "OPTO40") (pin "3") (pinfunction "ET_3") (pintype "passive"))
      (node (ref "OPTO41") (pin "3") (pinfunction "ET_3") (pintype "passive"))
      (node (ref "OPTO42") (pin "3") (pinfunction "ET_3") (pintype "passive"))
      (node (ref "OPTO43") (pin "3") (pinfunction "ET_3") (pintype "passive"))
      (node (ref "OPTO44") (pin "3") (pinfunction "ET_3") (pintype "passive"))
      (node (ref "OPTO45") (pin "3") (pinfunction "ET_3") (pintype "passive"))
      (node (ref "OPTO46") (pin "3") (pinfunction "ET_3") (pintype "passive"))
      (node (ref "OPTO47") (pin "3") (pinfunction "ET_3") (pintype "passive"))
      (node (ref "OPTO48") (pin "3") (pinfunction "ET_3") (pintype "passive"))
      (node (ref "OPTO5") (pin "3") (pinfunction "ET_3") (pintype "passive"))
      (node (ref "OPTO6") (pin "3") (pinfunction "ET_3") (pintype "passive"))
      (node (ref "OPTO7") (pin "3") (pinfunction "ET_3") (pintype "passive"))
      (node (ref "OPTO8") (pin "3") (pinfunction "ET_3") (pintype "passive"))
      (node (ref "OPTO9") (pin "3") (pinfunction "ET_3") (pintype "passive"))
      (node (ref "POWER") (pin "K") (pinfunction "C_K") (pintype "passive"))
      (node (ref "PROSES") (pin "K") (pinfunction "C_K") (pintype "passive"))
      (node (ref "PS2") (pin "3") (pinfunction "-V0_3") (pintype "bidirectional"))
      (node (ref "Q1") (pin "2") (pinfunction "E_2") (pintype "passive"))
      (node (ref "Q9") (pin "2") (pinfunction "E_2") (pintype "passive"))
      (node (ref "R104") (pin "1") (pinfunction "1_1") (pintype "passive"))
      (node (ref "R105") (pin "1") (pinfunction "1_1") (pintype "passive"))
      (node (ref "R106") (pin "1") (pinfunction "1_1") (pintype "passive"))
      (node (ref "R109") (pin "1") (pinfunction "1_1") (pintype "passive"))
      (node (ref "R110") (pin "1") (pinfunction "1_1") (pintype "passive"))
      (node (ref "R112") (pin "1") (pinfunction "1_1") (pintype "passive"))
      (node (ref "R114") (pin "1") (pinfunction "1_1") (pintype "passive"))
      (node (ref "R128") (pin "1") (pinfunction "1_1") (pintype "passive"))
      (node (ref "R131") (pin "1") (pinfunction "1_1") (pintype "passive"))
      (node (ref "R134") (pin "1") (pinfunction "1_1") (pintype "passive"))
      (node (ref "R137") (pin "1") (pinfunction "1_1") (pintype "passive"))
      (node (ref "RTC1") (pin "GND") (pinfunction "GND_GND") (pintype "bidirectional"))
      (node (ref "S1") (pin "2") (pinfunction "S_2") (pintype "passive"))
      (node (ref "S3") (pin "2") (pinfunction "S_2") (pintype "passive"))
      (node (ref "TTL-RS1") (pin "GND") (pinfunction "GND_GND") (pintype "bidirectional"))
      (node (ref "U$1") (pin "GND") (pinfunction "GND_GND") (pintype "bidirectional"))
      (node (ref "U$1") (pin "GND.2") (pinfunction "GND.2_GND.2") (pintype "bidirectional"))
      (node (ref "U$1") (pin "GND.3") (pinfunction "GND.3_GND.3") (pintype "bidirectional"))
      (node (ref "U1") (pin "1") (pinfunction "GND_1") (pintype "power_in"))
      (node (ref "U2") (pin "1") (pinfunction "ADJ/GND_1") (pintype "power_in"))
      (node (ref "U3") (pin "1") (pinfunction "GND_1") (pintype "power_in"))
      (node (ref "U3") (pin "15") (pinfunction "GND_15") (pintype "power_in"))
      (node (ref "U3") (pin "38") (pinfunction "GND_38") (pintype "power_in"))
      (node (ref "U3") (pin "39_1") (pinfunction "GND_39_1") (pintype "power_in"))
      (node (ref "U3") (pin "39_10") (pinfunction "GND_39_10") (pintype "power_in"))
      (node (ref "U3") (pin "39_11") (pinfunction "GND_39_11") (pintype "power_in"))
      (node (ref "U3") (pin "39_12") (pinfunction "GND_39_12") (pintype "power_in"))
      (node (ref "U3") (pin "39_13") (pinfunction "GND_39_13") (pintype "power_in"))
      (node (ref "U3") (pin "39_14") (pinfunction "GND_39_14") (pintype "power_in"))
      (node (ref "U3") (pin "39_15") (pinfunction "GND_39_15") (pintype "power_in"))
      (node (ref "U3") (pin "39_16") (pinfunction "GND_39_16") (pintype "power_in"))
      (node (ref "U3") (pin "39_17") (pinfunction "GND_39_17") (pintype "power_in"))
      (node (ref "U3") (pin "39_18") (pinfunction "GND_39_18") (pintype "power_in"))
      (node (ref "U3") (pin "39_19") (pinfunction "GND_39_19") (pintype "power_in"))
      (node (ref "U3") (pin "39_2") (pinfunction "GND_39_2") (pintype "power_in"))
      (node (ref "U3") (pin "39_20") (pinfunction "GND_39_20") (pintype "power_in"))
      (node (ref "U3") (pin "39_21") (pinfunction "GND_39_21") (pintype "power_in"))
      (node (ref "U3") (pin "39_3") (pinfunction "GND_39_3") (pintype "power_in"))
      (node (ref "U3") (pin "39_4") (pinfunction "GND_39_4") (pintype "power_in"))
      (node (ref "U3") (pin "39_5") (pinfunction "GND_39_5") (pintype "power_in"))
      (node (ref "U3") (pin "39_6") (pinfunction "GND_39_6") (pintype "power_in"))
      (node (ref "U3") (pin "39_7") (pinfunction "GND_39_7") (pintype "power_in"))
      (node (ref "U3") (pin "39_8") (pinfunction "GND_39_8") (pintype "power_in"))
      (node (ref "U3") (pin "39_9") (pinfunction "GND_39_9") (pintype "power_in"))
      (node (ref "U4") (pin "2") (pinfunction "C_2") (pintype "passive"))
      (node (ref "U49") (pin "2") (pinfunction "C_2") (pintype "passive"))
      (node (ref "U5") (pin "2") (pinfunction "C_2") (pintype "passive"))
      (node (ref "U6") (pin "2") (pinfunction "C_2") (pintype "passive"))
      (node (ref "U7") (pin "2") (pinfunction "C_2") (pintype "passive"))
      (node (ref "U8") (pin "2") (pinfunction "C_2") (pintype "passive"))
      (node (ref "WARNING") (pin "K") (pinfunction "C_K") (pintype "passive"))
      (node (ref "X1") (pin "3") (pinfunction "S_3") (pintype "passive"))
    )
    (net (code "89") (name "GND_TEST") (class "Default")
      (node (ref "R138") (pin "1") (pinfunction "1_1") (pintype "passive"))
      (node (ref "U3") (pin "12") (pinfunction "IO27_12") (pintype "bidirectional"))
    )
    (net (code "90") (name "IO0") (class "Default")
      (node (ref "C11") (pin "1") (pinfunction "1_1") (pintype "passive"))
      (node (ref "Q3") (pin "3") (pinfunction "C_3") (pintype "passive"))
      (node (ref "R120") (pin "1") (pinfunction "1_1") (pintype "passive"))
      (node (ref "S3") (pin "1") (pinfunction "P_1") (pintype "passive"))
      (node (ref "U3") (pin "25") (pinfunction "IO0_25") (pintype "bidirectional"))
    )
    (net (code "91") (name "L") (class "Default")
      (node (ref "HEADER-29P2") (pin "29") (pinfunction "29_29") (pintype "bidirectional"))
      (node (ref "PS2") (pin "1") (pinfunction "AC_1_1") (pintype "bidirectional"))
    )
    (net (code "92") (name "LED_PROSES") (class "Default")
      (node (ref "R124") (pin "2") (pinfunction "2_2") (pintype "passive"))
      (node (ref "U3") (pin "10") (pinfunction "IO25_10") (pintype "bidirectional"))
    )
    (net (code "93") (name "LED_WARNING") (class "Default")
      (node (ref "R125") (pin "2") (pinfunction "2_2") (pintype "passive"))
      (node (ref "U3") (pin "11") (pinfunction "IO26_11") (pintype "bidirectional"))
    )
    (net (code "94") (name "MISO_VSPI") (class "Default")
      (node (ref "U$1") (pin "MISO") (pinfunction "MISO_MISO") (pintype "bidirectional"))
      (node (ref "U3") (pin "31") (pinfunction "IO19_31") (pintype "bidirectional"))
    )
    (net (code "95") (name "MOSI_VSPI") (class "Default")
      (node (ref "U$1") (pin "MOSI") (pinfunction "MOSI_MOSI") (pintype "bidirectional"))
      (node (ref "U3") (pin "37") (pinfunction "IO23_37") (pintype "bidirectional"))
    )
    (net (code "96") (name "N") (class "Default")
      (node (ref "HEADER-29P2") (pin "28") (pinfunction "28_28") (pintype "bidirectional"))
      (node (ref "PS2") (pin "2") (pinfunction "AC_2_2") (pintype "bidirectional"))
    )
    (net (code "97") (name "NO") (class "Default")
      (node (ref "HEADER-29P2") (pin "1") (pinfunction "1_1") (pintype "bidirectional"))
      (node (ref "K1") (pin "NO") (pinfunction "NO_NO") (pintype "passive"))
    )
    (net (code "98") (name "Net-(D2-PadA)") (class "Default")
      (node (ref "D2") (pin "A") (pinfunction "A_A") (pintype "passive"))
      (node (ref "R1") (pin "2") (pinfunction "2_2") (pintype "passive"))
    )
    (net (code "99") (name "Net-(D3-PadA)") (class "Default")
      (node (ref "D3") (pin "A") (pinfunction "A_A") (pintype "passive"))
      (node (ref "R2") (pin "2") (pinfunction "2_2") (pintype "passive"))
    )
    (net (code "100") (name "Net-(D4-PadA)") (class "Default")
      (node (ref "D4") (pin "A") (pinfunction "A_A") (pintype "passive"))
      (node (ref "R3") (pin "2") (pinfunction "2_2") (pintype "passive"))
    )
    (net (code "101") (name "Net-(D5-PadA)") (class "Default")
      (node (ref "D5") (pin "A") (pinfunction "A_A") (pintype "passive"))
      (node (ref "R4") (pin "2") (pinfunction "2_2") (pintype "passive"))
    )
    (net (code "102") (name "Net-(D6-PadA)") (class "Default")
      (node (ref "D6") (pin "A") (pinfunction "A_A") (pintype "passive"))
      (node (ref "R5") (pin "2") (pinfunction "2_2") (pintype "passive"))
    )
    (net (code "103") (name "Net-(D7-PadA)") (class "Default")
      (node (ref "D7") (pin "A") (pinfunction "A_A") (pintype "passive"))
      (node (ref "R6") (pin "2") (pinfunction "2_2") (pintype "passive"))
    )
    (net (code "104") (name "Net-(D8-PadA)") (class "Default")
      (node (ref "D8") (pin "A") (pinfunction "A_A") (pintype "passive"))
      (node (ref "R7") (pin "2") (pinfunction "2_2") (pintype "passive"))
    )
    (net (code "105") (name "Net-(D9-PadA)") (class "Default")
      (node (ref "D9") (pin "A") (pinfunction "A_A") (pintype "passive"))
      (node (ref "R8") (pin "2") (pinfunction "2_2") (pintype "passive"))
    )
    (net (code "106") (name "Net-(D10-PadA)") (class "Default")
      (node (ref "D10") (pin "A") (pinfunction "A_A") (pintype "passive"))
      (node (ref "R9") (pin "2") (pinfunction "2_2") (pintype "passive"))
    )
    (net (code "107") (name "Net-(D11-PadA)") (class "Default")
      (node (ref "D11") (pin "A") (pinfunction "A_A") (pintype "passive"))
      (node (ref "R10") (pin "2") (pinfunction "2_2") (pintype "passive"))
    )
    (net (code "108") (name "Net-(D12-PadA)") (class "Default")
      (node (ref "D12") (pin "A") (pinfunction "A_A") (pintype "passive"))
      (node (ref "R11") (pin "2") (pinfunction "2_2") (pintype "passive"))
    )
    (net (code "109") (name "Net-(D13-PadA)") (class "Default")
      (node (ref "D13") (pin "A") (pinfunction "A_A") (pintype "passive"))
      (node (ref "R12") (pin "2") (pinfunction "2_2") (pintype "passive"))
    )
    (net (code "110") (name "Net-(D14-PadA)") (class "Default")
      (node (ref "D14") (pin "A") (pinfunction "A_A") (pintype "passive"))
      (node (ref "R13") (pin "2") (pinfunction "2_2") (pintype "passive"))
    )
    (net (code "111") (name "Net-(D15-PadA)") (class "Default")
      (node (ref "D15") (pin "A") (pinfunction "A_A") (pintype "passive"))
      (node (ref "R14") (pin "2") (pinfunction "2_2") (pintype "passive"))
    )
    (net (code "112") (name "Net-(D16-PadA)") (class "Default")
      (node (ref "D16") (pin "A") (pinfunction "A_A") (pintype "passive"))
      (node (ref "R15") (pin "2") (pinfunction "2_2") (pintype "passive"))
    )
    (net (code "113") (name "Net-(D17-PadA)") (class "Default")
      (node (ref "D17") (pin "A") (pinfunction "A_A") (pintype "passive"))
      (node (ref "R16") (pin "2") (pinfunction "2_2") (pintype "passive"))
    )
    (net (code "114") (name "Net-(D18-PadA)") (class "Default")
      (node (ref "D18") (pin "A") (pinfunction "A_A") (pintype "passive"))
      (node (ref "R17") (pin "2") (pinfunction "2_2") (pintype "passive"))
    )
    (net (code "115") (name "Net-(D19-PadA)") (class "Default")
      (node (ref "D19") (pin "A") (pinfunction "A_A") (pintype "passive"))
      (node (ref "R18") (pin "2") (pinfunction "2_2") (pintype "passive"))
    )
    (net (code "116") (name "Net-(D20-PadA)") (class "Default")
      (node (ref "D20") (pin "A") (pinfunction "A_A") (pintype "passive"))
      (node (ref "R19") (pin "2") (pinfunction "2_2") (pintype "passive"))
    )
    (net (code "117") (name "Net-(D21-PadA)") (class "Default")
      (node (ref "D21") (pin "A") (pinfunction "A_A") (pintype "passive"))
      (node (ref "R20") (pin "2") (pinfunction "2_2") (pintype "passive"))
    )
    (net (code "118") (name "Net-(D22-PadA)") (class "Default")
      (node (ref "D22") (pin "A") (pinfunction "A_A") (pintype "passive"))
      (node (ref "R21") (pin "2") (pinfunction "2_2") (pintype "passive"))
    )
    (net (code "119") (name "Net-(D23-PadA)") (class "Default")
      (node (ref "D23") (pin "A") (pinfunction "A_A") (pintype "passive"))
      (node (ref "R22") (pin "2") (pinfunction "2_2") (pintype "passive"))
    )
    (net (code "120") (name "Net-(D24-PadA)") (class "Default")
      (node (ref "D24") (pin "A") (pinfunction "A_A") (pintype "passive"))
      (node (ref "R23") (pin "2") (pinfunction "2_2") (pintype "passive"))
    )
    (net (code "121") (name "Net-(D25-PadA)") (class "Default")
      (node (ref "D25") (pin "A") (pinfunction "A_A") (pintype "passive"))
      (node (ref "R24") (pin "2") (pinfunction "2_2") (pintype "passive"))
    )
    (net (code "122") (name "Net-(D26-PadA)") (class "Default")
      (node (ref "D26") (pin "A") (pinfunction "A_A") (pintype "passive"))
      (node (ref "R25") (pin "2") (pinfunction "2_2") (pintype "passive"))
    )
    (net (code "123") (name "Net-(D27-PadA)") (class "Default")
      (node (ref "D27") (pin "A") (pinfunction "A_A") (pintype "passive"))
      (node (ref "R26") (pin "2") (pinfunction "2_2") (pintype "passive"))
    )
    (net (code "124") (name "Net-(D28-PadA)") (class "Default")
      (node (ref "D28") (pin "A") (pinfunction "A_A") (pintype "passive"))
      (node (ref "R27") (pin "2") (pinfunction "2_2") (pintype "passive"))
    )
    (net (code "125") (name "Net-(D29-PadA)") (class "Default")
      (node (ref "D29") (pin "A") (pinfunction "A_A") (pintype "passive"))
      (node (ref "R28") (pin "2") (pinfunction "2_2") (pintype "passive"))
    )
    (net (code "126") (name "Net-(D30-PadA)") (class "Default")
      (node (ref "D30") (pin "A") (pinfunction "A_A") (pintype "passive"))
      (node (ref "R29") (pin "2") (pinfunction "2_2") (pintype "passive"))
    )
    (net (code "127") (name "Net-(D31-PadA)") (class "Default")
      (node (ref "D31") (pin "A") (pinfunction "A_A") (pintype "passive"))
      (node (ref "R30") (pin "2") (pinfunction "2_2") (pintype "passive"))
    )
    (net (code "128") (name "Net-(D32-PadA)") (class "Default")
      (node (ref "D32") (pin "A") (pinfunction "A_A") (pintype "passive"))
      (node (ref "R31") (pin "2") (pinfunction "2_2") (pintype "passive"))
    )
    (net (code "129") (name "Net-(D33-PadA)") (class "Default")
      (node (ref "D33") (pin "A") (pinfunction "A_A") (pintype "passive"))
      (node (ref "R32") (pin "2") (pinfunction "2_2") (pintype "passive"))
    )
    (net (code "130") (name "Net-(D34-PadA)") (class "Default")
      (node (ref "D34") (pin "A") (pinfunction "A_A") (pintype "passive"))
      (node (ref "R33") (pin "2") (pinfunction "2_2") (pintype "passive"))
    )
    (net (code "131") (name "Net-(D35-PadA)") (class "Default")
      (node (ref "D35") (pin "A") (pinfunction "A_A") (pintype "passive"))
      (node (ref "R34") (pin "2") (pinfunction "2_2") (pintype "passive"))
    )
    (net (code "132") (name "Net-(D36-PadA)") (class "Default")
      (node (ref "D36") (pin "A") (pinfunction "A_A") (pintype "passive"))
      (node (ref "R35") (pin "2") (pinfunction "2_2") (pintype "passive"))
    )
    (net (code "133") (name "Net-(D37-PadA)") (class "Default")
      (node (ref "D37") (pin "A") (pinfunction "A_A") (pintype "passive"))
      (node (ref "R36") (pin "2") (pinfunction "2_2") (pintype "passive"))
    )
    (net (code "134") (name "Net-(D38-PadA)") (class "Default")
      (node (ref "D38") (pin "A") (pinfunction "A_A") (pintype "passive"))
      (node (ref "R37") (pin "2") (pinfunction "2_2") (pintype "passive"))
    )
    (net (code "135") (name "Net-(D39-PadA)") (class "Default")
      (node (ref "D39") (pin "A") (pinfunction "A_A") (pintype "passive"))
      (node (ref "R38") (pin "2") (pinfunction "2_2") (pintype "passive"))
    )
    (net (code "136") (name "Net-(D40-PadA)") (class "Default")
      (node (ref "D40") (pin "A") (pinfunction "A_A") (pintype "passive"))
      (node (ref "R39") (pin "2") (pinfunction "2_2") (pintype "passive"))
    )
    (net (code "137") (name "Net-(D41-PadA)") (class "Default")
      (node (ref "D41") (pin "A") (pinfunction "A_A") (pintype "passive"))
      (node (ref "R40") (pin "2") (pinfunction "2_2") (pintype "passive"))
    )
    (net (code "138") (name "Net-(D42-PadA)") (class "Default")
      (node (ref "D42") (pin "A") (pinfunction "A_A") (pintype "passive"))
      (node (ref "R41") (pin "2") (pinfunction "2_2") (pintype "passive"))
    )
    (net (code "139") (name "Net-(D43-PadA)") (class "Default")
      (node (ref "D43") (pin "A") (pinfunction "A_A") (pintype "passive"))
      (node (ref "R42") (pin "2") (pinfunction "2_2") (pintype "passive"))
    )
    (net (code "140") (name "Net-(D44-PadA)") (class "Default")
      (node (ref "D44") (pin "A") (pinfunction "A_A") (pintype "passive"))
      (node (ref "R43") (pin "2") (pinfunction "2_2") (pintype "passive"))
    )
    (net (code "141") (name "Net-(D45-PadA)") (class "Default")
      (node (ref "D45") (pin "A") (pinfunction "A_A") (pintype "passive"))
      (node (ref "R44") (pin "2") (pinfunction "2_2") (pintype "passive"))
    )
    (net (code "142") (name "Net-(D46-PadA)") (class "Default")
      (node (ref "D46") (pin "A") (pinfunction "A_A") (pintype "passive"))
      (node (ref "R45") (pin "2") (pinfunction "2_2") (pintype "passive"))
    )
    (net (code "143") (name "Net-(D47-PadA)") (class "Default")
      (node (ref "D47") (pin "A") (pinfunction "A_A") (pintype "passive"))
      (node (ref "R46") (pin "2") (pinfunction "2_2") (pintype "passive"))
    )
    (net (code "144") (name "Net-(D48-PadA)") (class "Default")
      (node (ref "D48") (pin "A") (pinfunction "A_A") (pintype "passive"))
      (node (ref "R47") (pin "2") (pinfunction "2_2") (pintype "passive"))
    )
    (net (code "145") (name "Net-(D49-PadA)") (class "Default")
      (node (ref "D49") (pin "A") (pinfunction "A_A") (pintype "passive"))
      (node (ref "R48") (pin "2") (pinfunction "2_2") (pintype "passive"))
    )
    (net (code "146") (name "Net-(D52-PadA)") (class "Default")
      (node (ref "D52") (pin "A") (pinfunction "A_A") (pintype "passive"))
      (node (ref "R121") (pin "1") (pinfunction "1_1") (pintype "passive"))
    )
    (net (code "147") (name "Net-(D53-PadA)") (class "Default")
      (node (ref "D53") (pin "A") (pinfunction "A_A") (pintype "passive"))
      (node (ref "R122") (pin "1") (pinfunction "1_1") (pintype "passive"))
    )
    (net (code "148") (name "Net-(D54-PadA)") (class "Default")
      (node (ref "D54") (pin "A") (pinfunction "A_A") (pintype "passive"))
      (node (ref "R126") (pin "2") (pinfunction "2_2") (pintype "passive"))
    )
    (net (code "149") (name "Net-(D103-PadA)") (class "Default")
      (node (ref "D103") (pin "A") (pinfunction "A_A") (pintype "passive"))
      (node (ref "R129") (pin "2") (pinfunction "2_2") (pintype "passive"))
    )
    (net (code "150") (name "Net-(D104-PadA)") (class "Default")
      (node (ref "D104") (pin "A") (pinfunction "A_A") (pintype "passive"))
      (node (ref "R132") (pin "2") (pinfunction "2_2") (pintype "passive"))
    )
    (net (code "151") (name "Net-(D105-PadA)") (class "Default")
      (node (ref "D105") (pin "A") (pinfunction "A_A") (pintype "passive"))
      (node (ref "R135") (pin "2") (pinfunction "2_2") (pintype "passive"))
    )
    (net (code "152") (name "Net-(D146-Pad+)") (class "Default")
      (node (ref "D146") (pin "+") (pinfunction "+_+") (pintype "passive"))
      (node (ref "R115") (pin "1") (pinfunction "1_1") (pintype "passive"))
    )
    (net (code "153") (name "Net-(IC1-A0)") (class "Default")
      (node (ref "IC1") (pin "15") (pinfunction "A0_15") (pintype "input"))
      (node (ref "R108") (pin "2") (pinfunction "2_2") (pintype "passive"))
    )
    (net (code "154") (name "Net-(IC1-A1)") (class "Default")
      (node (ref "IC1") (pin "16") (pinfunction "A1_16") (pintype "input"))
      (node (ref "R109") (pin "2") (pinfunction "2_2") (pintype "passive"))
    )
    (net (code "155") (name "Net-(IC1-A2)") (class "Default")
      (node (ref "IC1") (pin "17") (pinfunction "A2_17") (pintype "input"))
      (node (ref "R110") (pin "2") (pinfunction "2_2") (pintype "passive"))
    )
    (net (code "156") (name "Net-(IC4-A0)") (class "Default")
      (node (ref "IC4") (pin "15") (pinfunction "A0_15") (pintype "input"))
      (node (ref "R106") (pin "2") (pinfunction "2_2") (pintype "passive"))
    )
    (net (code "157") (name "Net-(IC4-A1)") (class "Default")
      (node (ref "IC4") (pin "16") (pinfunction "A1_16") (pintype "input"))
      (node (ref "R105") (pin "2") (pinfunction "2_2") (pintype "passive"))
    )
    (net (code "158") (name "Net-(IC4-A2)") (class "Default")
      (node (ref "IC4") (pin "17") (pinfunction "A2_17") (pintype "input"))
      (node (ref "R104") (pin "2") (pinfunction "2_2") (pintype "passive"))
    )
    (net (code "159") (name "Net-(IC5-A0)") (class "Default")
      (node (ref "IC5") (pin "15") (pinfunction "A0_15") (pintype "input"))
      (node (ref "R112") (pin "2") (pinfunction "2_2") (pintype "passive"))
    )
    (net (code "160") (name "Net-(IC5-A1)") (class "Default")
      (node (ref "IC5") (pin "16") (pinfunction "A1_16") (pintype "input"))
      (node (ref "R113") (pin "2") (pinfunction "2_2") (pintype "passive"))
    )
    (net (code "161") (name "Net-(IC5-A2)") (class "Default")
      (node (ref "IC5") (pin "17") (pinfunction "A2_17") (pintype "input"))
      (node (ref "R114") (pin "2") (pinfunction "2_2") (pintype "passive"))
    )
    (net (code "162") (name "Net-(K2A-2)") (class "Default")
      (node (ref "D107") (pin "A") (pinfunction "A_A") (pintype "passive"))
      (node (ref "K2") (pin "16") (pinfunction "2_16") (pintype "passive"))
      (node (ref "Q9") (pin "3") (pinfunction "C_3") (pintype "passive"))
    )
    (net (code "163") (name "Net-(OPTO1-A)") (class "Default")
      (node (ref "LED1") (pin "-") (pinfunction "-_-") (pintype "passive"))
      (node (ref "OPTO1") (pin "1") (pinfunction "A_1") (pintype "passive"))
      (node (ref "Z1") (pin "C") (pinfunction "C_C") (pintype "passive"))
    )
    (net (code "164") (name "Net-(OPTO2-A)") (class "Default")
      (node (ref "LED2") (pin "-") (pinfunction "-_-") (pintype "passive"))
      (node (ref "OPTO2") (pin "1") (pinfunction "A_1") (pintype "passive"))
      (node (ref "Z2") (pin "C") (pinfunction "C_C") (pintype "passive"))
    )
    (net (code "165") (name "Net-(OPTO3-A)") (class "Default")
      (node (ref "LED3") (pin "-") (pinfunction "-_-") (pintype "passive"))
      (node (ref "OPTO3") (pin "1") (pinfunction "A_1") (pintype "passive"))
      (node (ref "Z3") (pin "C") (pinfunction "C_C") (pintype "passive"))
    )
    (net (code "166") (name "Net-(OPTO4-A)") (class "Default")
      (node (ref "LED4") (pin "-") (pinfunction "-_-") (pintype "passive"))
      (node (ref "OPTO4") (pin "1") (pinfunction "A_1") (pintype "passive"))
      (node (ref "Z4") (pin "C") (pinfunction "C_C") (pintype "passive"))
    )
    (net (code "167") (name "Net-(OPTO5-A)") (class "Default")
      (node (ref "LED5") (pin "-") (pinfunction "-_-") (pintype "passive"))
      (node (ref "OPTO5") (pin "1") (pinfunction "A_1") (pintype "passive"))
      (node (ref "Z5") (pin "C") (pinfunction "C_C") (pintype "passive"))
    )
    (net (code "168") (name "Net-(OPTO6-A)") (class "Default")
      (node (ref "LED6") (pin "-") (pinfunction "-_-") (pintype "passive"))
      (node (ref "OPTO6") (pin "1") (pinfunction "A_1") (pintype "passive"))
      (node (ref "Z6") (pin "C") (pinfunction "C_C") (pintype "passive"))
    )
    (net (code "169") (name "Net-(OPTO7-A)") (class "Default")
      (node (ref "LED7") (pin "-") (pinfunction "-_-") (pintype "passive"))
      (node (ref "OPTO7") (pin "1") (pinfunction "A_1") (pintype "passive"))
      (node (ref "Z7") (pin "C") (pinfunction "C_C") (pintype "passive"))
    )
    (net (code "170") (name "Net-(OPTO8-A)") (class "Default")
      (node (ref "LED8") (pin "-") (pinfunction "-_-") (pintype "passive"))
      (node (ref "OPTO8") (pin "1") (pinfunction "A_1") (pintype "passive"))
      (node (ref "Z8") (pin "C") (pinfunction "C_C") (pintype "passive"))
    )
    (net (code "171") (name "Net-(OPTO9-A)") (class "Default")
      (node (ref "LED9") (pin "-") (pinfunction "-_-") (pintype "passive"))
      (node (ref "OPTO9") (pin "1") (pinfunction "A_1") (pintype "passive"))
      (node (ref "Z9") (pin "C") (pinfunction "C_C") (pintype "passive"))
    )
    (net (code "172") (name "Net-(OPTO10-A)") (class "Default")
      (node (ref "LED10") (pin "-") (pinfunction "-_-") (pintype "passive"))
      (node (ref "OPTO10") (pin "1") (pinfunction "A_1") (pintype "passive"))
      (node (ref "Z10") (pin "C") (pinfunction "C_C") (pintype "passive"))
    )
    (net (code "173") (name "Net-(OPTO11-A)") (class "Default")
      (node (ref "LED11") (pin "-") (pinfunction "-_-") (pintype "passive"))
      (node (ref "OPTO11") (pin "1") (pinfunction "A_1") (pintype "passive"))
      (node (ref "Z11") (pin "C") (pinfunction "C_C") (pintype "passive"))
    )
    (net (code "174") (name "Net-(OPTO12-A)") (class "Default")
      (node (ref "LED12") (pin "-") (pinfunction "-_-") (pintype "passive"))
      (node (ref "OPTO12") (pin "1") (pinfunction "A_1") (pintype "passive"))
      (node (ref "Z12") (pin "C") (pinfunction "C_C") (pintype "passive"))
    )
    (net (code "175") (name "Net-(OPTO13-A)") (class "Default")
      (node (ref "LED13") (pin "-") (pinfunction "-_-") (pintype "passive"))
      (node (ref "OPTO13") (pin "1") (pinfunction "A_1") (pintype "passive"))
      (node (ref "Z13") (pin "C") (pinfunction "C_C") (pintype "passive"))
    )
    (net (code "176") (name "Net-(OPTO14-A)") (class "Default")
      (node (ref "LED14") (pin "-") (pinfunction "-_-") (pintype "passive"))
      (node (ref "OPTO14") (pin "1") (pinfunction "A_1") (pintype "passive"))
      (node (ref "Z14") (pin "C") (pinfunction "C_C") (pintype "passive"))
    )
    (net (code "177") (name "Net-(OPTO15-A)") (class "Default")
      (node (ref "LED15") (pin "-") (pinfunction "-_-") (pintype "passive"))
      (node (ref "OPTO15") (pin "1") (pinfunction "A_1") (pintype "passive"))
      (node (ref "Z15") (pin "C") (pinfunction "C_C") (pintype "passive"))
    )
    (net (code "178") (name "Net-(OPTO16-A)") (class "Default")
      (node (ref "LED16") (pin "-") (pinfunction "-_-") (pintype "passive"))
      (node (ref "OPTO16") (pin "1") (pinfunction "A_1") (pintype "passive"))
      (node (ref "Z16") (pin "C") (pinfunction "C_C") (pintype "passive"))
    )
    (net (code "179") (name "Net-(OPTO17-A)") (class "Default")
      (node (ref "LED17") (pin "-") (pinfunction "-_-") (pintype "passive"))
      (node (ref "OPTO17") (pin "1") (pinfunction "A_1") (pintype "passive"))
      (node (ref "Z17") (pin "C") (pinfunction "C_C") (pintype "passive"))
    )
    (net (code "180") (name "Net-(OPTO18-A)") (class "Default")
      (node (ref "LED18") (pin "-") (pinfunction "-_-") (pintype "passive"))
      (node (ref "OPTO18") (pin "1") (pinfunction "A_1") (pintype "passive"))
      (node (ref "Z18") (pin "C") (pinfunction "C_C") (pintype "passive"))
    )
    (net (code "181") (name "Net-(OPTO19-A)") (class "Default")
      (node (ref "LED19") (pin "-") (pinfunction "-_-") (pintype "passive"))
      (node (ref "OPTO19") (pin "1") (pinfunction "A_1") (pintype "passive"))
      (node (ref "Z19") (pin "C") (pinfunction "C_C") (pintype "passive"))
    )
    (net (code "182") (name "Net-(OPTO20-A)") (class "Default")
      (node (ref "LED20") (pin "-") (pinfunction "-_-") (pintype "passive"))
      (node (ref "OPTO20") (pin "1") (pinfunction "A_1") (pintype "passive"))
      (node (ref "Z20") (pin "C") (pinfunction "C_C") (pintype "passive"))
    )
    (net (code "183") (name "Net-(OPTO21-A)") (class "Default")
      (node (ref "LED21") (pin "-") (pinfunction "-_-") (pintype "passive"))
      (node (ref "OPTO21") (pin "1") (pinfunction "A_1") (pintype "passive"))
      (node (ref "Z21") (pin "C") (pinfunction "C_C") (pintype "passive"))
    )
    (net (code "184") (name "Net-(OPTO22-A)") (class "Default")
      (node (ref "LED22") (pin "-") (pinfunction "-_-") (pintype "passive"))
      (node (ref "OPTO22") (pin "1") (pinfunction "A_1") (pintype "passive"))
      (node (ref "Z22") (pin "C") (pinfunction "C_C") (pintype "passive"))
    )
    (net (code "185") (name "Net-(OPTO23-A)") (class "Default")
      (node (ref "LED23") (pin "-") (pinfunction "-_-") (pintype "passive"))
      (node (ref "OPTO23") (pin "1") (pinfunction "A_1") (pintype "passive"))
      (node (ref "Z23") (pin "C") (pinfunction "C_C") (pintype "passive"))
    )
    (net (code "186") (name "Net-(OPTO24-A)") (class "Default")
      (node (ref "LED24") (pin "-") (pinfunction "-_-") (pintype "passive"))
      (node (ref "OPTO24") (pin "1") (pinfunction "A_1") (pintype "passive"))
      (node (ref "Z24") (pin "C") (pinfunction "C_C") (pintype "passive"))
    )
    (net (code "187") (name "Net-(OPTO25-A)") (class "Default")
      (node (ref "LED25") (pin "-") (pinfunction "-_-") (pintype "passive"))
      (node (ref "OPTO25") (pin "1") (pinfunction "A_1") (pintype "passive"))
      (node (ref "Z25") (pin "C") (pinfunction "C_C") (pintype "passive"))
    )
    (net (code "188") (name "Net-(OPTO26-A)") (class "Default")
      (node (ref "LED26") (pin "-") (pinfunction "-_-") (pintype "passive"))
      (node (ref "OPTO26") (pin "1") (pinfunction "A_1") (pintype "passive"))
      (node (ref "Z26") (pin "C") (pinfunction "C_C") (pintype "passive"))
    )
    (net (code "189") (name "Net-(OPTO27-A)") (class "Default")
      (node (ref "LED27") (pin "-") (pinfunction "-_-") (pintype "passive"))
      (node (ref "OPTO27") (pin "1") (pinfunction "A_1") (pintype "passive"))
      (node (ref "Z27") (pin "C") (pinfunction "C_C") (pintype "passive"))
    )
    (net (code "190") (name "Net-(OPTO28-A)") (class "Default")
      (node (ref "LED28") (pin "-") (pinfunction "-_-") (pintype "passive"))
      (node (ref "OPTO28") (pin "1") (pinfunction "A_1") (pintype "passive"))
      (node (ref "Z28") (pin "C") (pinfunction "C_C") (pintype "passive"))
    )
    (net (code "191") (name "Net-(OPTO29-A)") (class "Default")
      (node (ref "LED29") (pin "-") (pinfunction "-_-") (pintype "passive"))
      (node (ref "OPTO29") (pin "1") (pinfunction "A_1") (pintype "passive"))
      (node (ref "Z29") (pin "C") (pinfunction "C_C") (pintype "passive"))
    )
    (net (code "192") (name "Net-(OPTO30-A)") (class "Default")
      (node (ref "LED30") (pin "-") (pinfunction "-_-") (pintype "passive"))
      (node (ref "OPTO30") (pin "1") (pinfunction "A_1") (pintype "passive"))
      (node (ref "Z30") (pin "C") (pinfunction "C_C") (pintype "passive"))
    )
    (net (code "193") (name "Net-(OPTO31-A)") (class "Default")
      (node (ref "LED31") (pin "-") (pinfunction "-_-") (pintype "passive"))
      (node (ref "OPTO31") (pin "1") (pinfunction "A_1") (pintype "passive"))
      (node (ref "Z31") (pin "C") (pinfunction "C_C") (pintype "passive"))
    )
    (net (code "194") (name "Net-(OPTO32-A)") (class "Default")
      (node (ref "LED32") (pin "-") (pinfunction "-_-") (pintype "passive"))
      (node (ref "OPTO32") (pin "1") (pinfunction "A_1") (pintype "passive"))
      (node (ref "Z32") (pin "C") (pinfunction "C_C") (pintype "passive"))
    )
    (net (code "195") (name "Net-(OPTO33-A)") (class "Default")
      (node (ref "LED33") (pin "-") (pinfunction "-_-") (pintype "passive"))
      (node (ref "OPTO33") (pin "1") (pinfunction "A_1") (pintype "passive"))
      (node (ref "Z33") (pin "C") (pinfunction "C_C") (pintype "passive"))
    )
    (net (code "196") (name "Net-(OPTO34-A)") (class "Default")
      (node (ref "LED34") (pin "-") (pinfunction "-_-") (pintype "passive"))
      (node (ref "OPTO34") (pin "1") (pinfunction "A_1") (pintype "passive"))
      (node (ref "Z34") (pin "C") (pinfunction "C_C") (pintype "passive"))
    )
    (net (code "197") (name "Net-(OPTO35-A)") (class "Default")
      (node (ref "LED35") (pin "-") (pinfunction "-_-") (pintype "passive"))
      (node (ref "OPTO35") (pin "1") (pinfunction "A_1") (pintype "passive"))
      (node (ref "Z35") (pin "C") (pinfunction "C_C") (pintype "passive"))
    )
    (net (code "198") (name "Net-(OPTO36-A)") (class "Default")
      (node (ref "LED36") (pin "-") (pinfunction "-_-") (pintype "passive"))
      (node (ref "OPTO36") (pin "1") (pinfunction "A_1") (pintype "passive"))
      (node (ref "Z36") (pin "C") (pinfunction "C_C") (pintype "passive"))
    )
    (net (code "199") (name "Net-(OPTO37-A)") (class "Default")
      (node (ref "LED37") (pin "-") (pinfunction "-_-") (pintype "passive"))
      (node (ref "OPTO37") (pin "1") (pinfunction "A_1") (pintype "passive"))
      (node (ref "Z37") (pin "C") (pinfunction "C_C") (pintype "passive"))
    )
    (net (code "200") (name "Net-(OPTO38-A)") (class "Default")
      (node (ref "LED38") (pin "-") (pinfunction "-_-") (pintype "passive"))
      (node (ref "OPTO38") (pin "1") (pinfunction "A_1") (pintype "passive"))
      (node (ref "Z38") (pin "C") (pinfunction "C_C") (pintype "passive"))
    )
    (net (code "201") (name "Net-(OPTO39-A)") (class "Default")
      (node (ref "LED39") (pin "-") (pinfunction "-_-") (pintype "passive"))
      (node (ref "OPTO39") (pin "1") (pinfunction "A_1") (pintype "passive"))
      (node (ref "Z39") (pin "C") (pinfunction "C_C") (pintype "passive"))
    )
    (net (code "202") (name "Net-(OPTO40-A)") (class "Default")
      (node (ref "LED40") (pin "-") (pinfunction "-_-") (pintype "passive"))
      (node (ref "OPTO40") (pin "1") (pinfunction "A_1") (pintype "passive"))
      (node (ref "Z40") (pin "C") (pinfunction "C_C") (pintype "passive"))
    )
    (net (code "203") (name "Net-(OPTO41-A)") (class "Default")
      (node (ref "LED41") (pin "-") (pinfunction "-_-") (pintype "passive"))
      (node (ref "OPTO41") (pin "1") (pinfunction "A_1") (pintype "passive"))
      (node (ref "Z41") (pin "C") (pinfunction "C_C") (pintype "passive"))
    )
    (net (code "204") (name "Net-(OPTO42-A)") (class "Default")
      (node (ref "LED42") (pin "-") (pinfunction "-_-") (pintype "passive"))
      (node (ref "OPTO42") (pin "1") (pinfunction "A_1") (pintype "passive"))
      (node (ref "Z42") (pin "C") (pinfunction "C_C") (pintype "passive"))
    )
    (net (code "205") (name "Net-(OPTO43-A)") (class "Default")
      (node (ref "LED43") (pin "-") (pinfunction "-_-") (pintype "passive"))
      (node (ref "OPTO43") (pin "1") (pinfunction "A_1") (pintype "passive"))
      (node (ref "Z43") (pin "C") (pinfunction "C_C") (pintype "passive"))
    )
    (net (code "206") (name "Net-(OPTO44-A)") (class "Default")
      (node (ref "LED44") (pin "-") (pinfunction "-_-") (pintype "passive"))
      (node (ref "OPTO44") (pin "1") (pinfunction "A_1") (pintype "passive"))
      (node (ref "Z44") (pin "C") (pinfunction "C_C") (pintype "passive"))
    )
    (net (code "207") (name "Net-(OPTO45-A)") (class "Default")
      (node (ref "LED45") (pin "-") (pinfunction "-_-") (pintype "passive"))
      (node (ref "OPTO45") (pin "1") (pinfunction "A_1") (pintype "passive"))
      (node (ref "Z45") (pin "C") (pinfunction "C_C") (pintype "passive"))
    )
    (net (code "208") (name "Net-(OPTO46-A)") (class "Default")
      (node (ref "LED46") (pin "-") (pinfunction "-_-") (pintype "passive"))
      (node (ref "OPTO46") (pin "1") (pinfunction "A_1") (pintype "passive"))
      (node (ref "Z46") (pin "C") (pinfunction "C_C") (pintype "passive"))
    )
    (net (code "209") (name "Net-(OPTO47-A)") (class "Default")
      (node (ref "LED47") (pin "-") (pinfunction "-_-") (pintype "passive"))
      (node (ref "OPTO47") (pin "1") (pinfunction "A_1") (pintype "passive"))
      (node (ref "Z47") (pin "C") (pinfunction "C_C") (pintype "passive"))
    )
    (net (code "210") (name "Net-(OPTO48-A)") (class "Default")
      (node (ref "LED48") (pin "-") (pinfunction "-_-") (pintype "passive"))
      (node (ref "OPTO48") (pin "1") (pinfunction "A_1") (pintype "passive"))
      (node (ref "Z48") (pin "C") (pinfunction "C_C") (pintype "passive"))
    )
    (net (code "211") (name "Net-(POWER-PadA)") (class "Default")
      (node (ref "POWER") (pin "A") (pinfunction "A_A") (pintype "passive"))
      (node (ref "R123") (pin "1") (pinfunction "1_1") (pintype "passive"))
    )
    (net (code "212") (name "Net-(PROSES-PadA)") (class "Default")
      (node (ref "PROSES") (pin "A") (pinfunction "A_A") (pintype "passive"))
      (node (ref "R124") (pin "1") (pinfunction "1_1") (pintype "passive"))
    )
    (net (code "213") (name "Net-(PS2-+V0)") (class "Default")
      (node (ref "D50") (pin "A") (pinfunction "A_A") (pintype "passive"))
      (node (ref "PS2") (pin "4") (pinfunction "+V0_4") (pintype "bidirectional"))
    )
    (net (code "214") (name "Net-(Q1-B)") (class "Default")
      (node (ref "Q1") (pin "1") (pinfunction "B_1") (pintype "passive"))
      (node (ref "U49") (pin "3") (pinfunction "ET_3") (pintype "passive"))
    )
    (net (code "215") (name "Net-(Q1-C)") (class "Default")
      (node (ref "D1") (pin "A") (pinfunction "A_A") (pintype "passive"))
      (node (ref "K1") (pin "A2") (pinfunction "A2_A2") (pintype "passive"))
      (node (ref "Q1") (pin "3") (pinfunction "C_3") (pintype "passive"))
    )
    (net (code "216") (name "Net-(Q2-B)") (class "Default")
      (node (ref "Q2") (pin "1") (pinfunction "B_1") (pintype "passive"))
      (node (ref "R117") (pin "2") (pinfunction "2_2") (pintype "passive"))
    )
    (net (code "217") (name "Net-(Q3-B)") (class "Default")
      (node (ref "Q3") (pin "1") (pinfunction "B_1") (pintype "passive"))
      (node (ref "R118") (pin "2") (pinfunction "2_2") (pintype "passive"))
    )
    (net (code "218") (name "Net-(Q5-B)") (class "Default")
      (node (ref "Q5") (pin "1") (pinfunction "B_1") (pintype "passive"))
      (node (ref "U4") (pin "3") (pinfunction "ET_3") (pintype "passive"))
    )
    (net (code "219") (name "Net-(Q6-B)") (class "Default")
      (node (ref "Q6") (pin "1") (pinfunction "B_1") (pintype "passive"))
      (node (ref "U5") (pin "3") (pinfunction "ET_3") (pintype "passive"))
    )
    (net (code "220") (name "Net-(Q7-B)") (class "Default")
      (node (ref "Q7") (pin "1") (pinfunction "B_1") (pintype "passive"))
      (node (ref "U6") (pin "3") (pinfunction "ET_3") (pintype "passive"))
    )
    (net (code "221") (name "Net-(Q8-B)") (class "Default")
      (node (ref "Q8") (pin "1") (pinfunction "B_1") (pintype "passive"))
      (node (ref "U7") (pin "3") (pinfunction "ET_3") (pintype "passive"))
    )
    (net (code "222") (name "Net-(Q9-B)") (class "Default")
      (node (ref "Q9") (pin "1") (pinfunction "B_1") (pintype "passive"))
      (node (ref "U8") (pin "3") (pinfunction "ET_3") (pintype "passive"))
    )
    (net (code "223") (name "Net-(R125-Pad1)") (class "Default")
      (node (ref "R125") (pin "1") (pinfunction "1_1") (pintype "passive"))
      (node (ref "WARNING") (pin "A") (pinfunction "A_A") (pintype "passive"))
    )
    (net (code "224") (name "Net-(U1-V3)") (class "Default")
      (node (ref "C3") (pin "1") (pinfunction "1_1") (pintype "passive"))
      (node (ref "U1") (pin "4") (pinfunction "V3_4") (pintype "power_in"))
    )
    (net (code "225") (name "Net-(U1-XI)") (class "Default")
      (node (ref "C4") (pin "2") (pinfunction "2_2") (pintype "passive"))
      (node (ref "Q4") (pin "2") (pinfunction "2_2") (pintype "passive"))
      (node (ref "U1") (pin "7") (pinfunction "XI_7") (pintype "input"))
    )
    (net (code "226") (name "Net-(U1-XO)") (class "Default")
      (node (ref "C5") (pin "2") (pinfunction "2_2") (pintype "passive"))
      (node (ref "Q4") (pin "1") (pinfunction "1_1") (pintype "passive"))
      (node (ref "U1") (pin "8") (pinfunction "XO_8") (pintype "output"))
    )
    (net (code "227") (name "Net-(U4-A)") (class "Default")
      (node (ref "D54") (pin "C") (pinfunction "C_C") (pintype "passive"))
      (node (ref "U4") (pin "1") (pinfunction "A_1") (pintype "passive"))
    )
    (net (code "228") (name "Net-(U4-CT)") (class "Default")
      (node (ref "R127") (pin "1") (pinfunction "1_1") (pintype "passive"))
      (node (ref "U4") (pin "4") (pinfunction "CT_4") (pintype "passive"))
    )
    (net (code "229") (name "Net-(U5-A)") (class "Default")
      (node (ref "D103") (pin "C") (pinfunction "C_C") (pintype "passive"))
      (node (ref "U5") (pin "1") (pinfunction "A_1") (pintype "passive"))
    )
    (net (code "230") (name "Net-(U5-CT)") (class "Default")
      (node (ref "R130") (pin "1") (pinfunction "1_1") (pintype "passive"))
      (node (ref "U5") (pin "4") (pinfunction "CT_4") (pintype "passive"))
    )
    (net (code "231") (name "Net-(U6-A)") (class "Default")
      (node (ref "D104") (pin "C") (pinfunction "C_C") (pintype "passive"))
      (node (ref "U6") (pin "1") (pinfunction "A_1") (pintype "passive"))
    )
    (net (code "232") (name "Net-(U6-CT)") (class "Default")
      (node (ref "R133") (pin "1") (pinfunction "1_1") (pintype "passive"))
      (node (ref "U6") (pin "4") (pinfunction "CT_4") (pintype "passive"))
    )
    (net (code "233") (name "Net-(U7-A)") (class "Default")
      (node (ref "D105") (pin "C") (pinfunction "C_C") (pintype "passive"))
      (node (ref "U7") (pin "1") (pinfunction "A_1") (pintype "passive"))
    )
    (net (code "234") (name "Net-(U7-CT)") (class "Default")
      (node (ref "R136") (pin "1") (pinfunction "1_1") (pintype "passive"))
      (node (ref "U7") (pin "4") (pinfunction "CT_4") (pintype "passive"))
    )
    (net (code "235") (name "Net-(U8-A)") (class "Default")
      (node (ref "R138") (pin "2") (pinfunction "2_2") (pintype "passive"))
      (node (ref "U8") (pin "1") (pinfunction "A_1") (pintype "passive"))
    )
    (net (code "236") (name "Net-(U8-CT)") (class "Default")
      (node (ref "R139") (pin "1") (pinfunction "1_1") (pintype "passive"))
      (node (ref "U8") (pin "4") (pinfunction "CT_4") (pintype "passive"))
    )
    (net (code "237") (name "Net-(U49-A)") (class "Default")
      (node (ref "D146") (pin "-") (pinfunction "-_-") (pintype "passive"))
      (node (ref "U49") (pin "1") (pinfunction "A_1") (pintype "passive"))
    )
    (net (code "238") (name "Net-(U49-CT)") (class "Default")
      (node (ref "R116") (pin "1") (pinfunction "1_1") (pintype "passive"))
      (node (ref "U49") (pin "4") (pinfunction "CT_4") (pintype "passive"))
    )
    (net (code "239") (name "OUT+") (class "Default")
      (node (ref "C6") (pin "+") (pinfunction "+_+") (pintype "passive"))
      (node (ref "C7") (pin "1") (pinfunction "1_1") (pintype "passive"))
      (node (ref "C8") (pin "1") (pinfunction "1_1") (pintype "passive"))
      (node (ref "D1") (pin "C") (pinfunction "K_C") (pintype "passive"))
      (node (ref "D107") (pin "C") (pinfunction "K_C") (pintype "passive"))
      (node (ref "D50") (pin "C") (pinfunction "K_C") (pintype "passive"))
      (node (ref "D51") (pin "C") (pinfunction "K_C") (pintype "passive"))
      (node (ref "JP1") (pin "1") (pinfunction "1_1") (pintype "passive"))
      (node (ref "K1") (pin "A1") (pinfunction "A1_A1") (pintype "passive"))
      (node (ref "K2") (pin "1") (pinfunction "1_1") (pintype "passive"))
      (node (ref "MT1") (pin "VIN+") (pinfunction "VIN+_VIN+") (pintype "bidirectional"))
      (node (ref "Q5") (pin "3") (pinfunction "C_3") (pintype "passive"))
      (node (ref "Q6") (pin "3") (pinfunction "C_3") (pintype "passive"))
      (node (ref "Q7") (pin "3") (pinfunction "C_3") (pintype "passive"))
      (node (ref "Q8") (pin "3") (pinfunction "C_3") (pintype "passive"))
      (node (ref "R116") (pin "2") (pinfunction "2_2") (pintype "passive"))
      (node (ref "R123") (pin "2") (pinfunction "2_2") (pintype "passive"))
      (node (ref "R127") (pin "2") (pinfunction "2_2") (pintype "passive"))
      (node (ref "R130") (pin "2") (pinfunction "2_2") (pintype "passive"))
      (node (ref "R133") (pin "2") (pinfunction "2_2") (pintype "passive"))
      (node (ref "R136") (pin "2") (pinfunction "2_2") (pintype "passive"))
      (node (ref "R139") (pin "2") (pinfunction "2_2") (pintype "passive"))
      (node (ref "TTL-RS1") (pin "VCC") (pinfunction "VCC_VCC") (pintype "bidirectional"))
      (node (ref "U2") (pin "3") (pinfunction "VIN_3") (pintype "input"))
    )
    (net (code "240") (name "P30") (class "Default")
      (node (ref "HEADER-29P2") (pin "8") (pinfunction "8_8") (pintype "bidirectional"))
      (node (ref "R30") (pin "1") (pinfunction "1_1") (pintype "passive"))
    )
    (net (code "241") (name "P31") (class "Default")
      (node (ref "HEADER-29P2") (pin "9") (pinfunction "9_9") (pintype "bidirectional"))
      (node (ref "R31") (pin "1") (pinfunction "1_1") (pintype "passive"))
    )
    (net (code "242") (name "P32") (class "Default")
      (node (ref "HEADER-29P2") (pin "10") (pinfunction "10_10") (pintype "bidirectional"))
      (node (ref "R32") (pin "1") (pinfunction "1_1") (pintype "passive"))
    )
    (net (code "243") (name "P33") (class "Default")
      (node (ref "HEADER-29P2") (pin "11") (pinfunction "11_11") (pintype "bidirectional"))
      (node (ref "R33") (pin "1") (pinfunction "1_1") (pintype "passive"))
    )
    (net (code "244") (name "P34") (class "Default")
      (node (ref "HEADER-29P2") (pin "12") (pinfunction "12_12") (pintype "bidirectional"))
      (node (ref "R34") (pin "1") (pinfunction "1_1") (pintype "passive"))
    )
    (net (code "245") (name "P35") (class "Default")
      (node (ref "HEADER-29P2") (pin "13") (pinfunction "13_13") (pintype "bidirectional"))
      (node (ref "R35") (pin "1") (pinfunction "1_1") (pintype "passive"))
    )
    (net (code "246") (name "P36") (class "Default")
      (node (ref "HEADER-29P2") (pin "14") (pinfunction "14_14") (pintype "bidirectional"))
      (node (ref "R36") (pin "1") (pinfunction "1_1") (pintype "passive"))
    )
    (net (code "247") (name "P37") (class "Default")
      (node (ref "HEADER-29P2") (pin "15") (pinfunction "15_15") (pintype "bidirectional"))
      (node (ref "R37") (pin "1") (pinfunction "1_1") (pintype "passive"))
    )
    (net (code "248") (name "P38") (class "Default")
      (node (ref "HEADER-29P2") (pin "16") (pinfunction "16_16") (pintype "bidirectional"))
      (node (ref "R38") (pin "1") (pinfunction "1_1") (pintype "passive"))
    )
    (net (code "249") (name "P39") (class "Default")
      (node (ref "HEADER-29P2") (pin "17") (pinfunction "17_17") (pintype "bidirectional"))
      (node (ref "R39") (pin "1") (pinfunction "1_1") (pintype "passive"))
    )
    (net (code "250") (name "P40") (class "Default")
      (node (ref "HEADER-29P2") (pin "18") (pinfunction "18_18") (pintype "bidirectional"))
      (node (ref "R40") (pin "1") (pinfunction "1_1") (pintype "passive"))
    )
    (net (code "251") (name "P41") (class "Default")
      (node (ref "HEADER-29P2") (pin "19") (pinfunction "19_19") (pintype "bidirectional"))
      (node (ref "R41") (pin "1") (pinfunction "1_1") (pintype "passive"))
    )
    (net (code "252") (name "P42") (class "Default")
      (node (ref "HEADER-29P2") (pin "20") (pinfunction "20_20") (pintype "bidirectional"))
      (node (ref "R42") (pin "1") (pinfunction "1_1") (pintype "passive"))
    )
    (net (code "253") (name "P43") (class "Default")
      (node (ref "HEADER-29P2") (pin "21") (pinfunction "21_21") (pintype "bidirectional"))
      (node (ref "R43") (pin "1") (pinfunction "1_1") (pintype "passive"))
    )
    (net (code "254") (name "P44") (class "Default")
      (node (ref "HEADER-29P2") (pin "22") (pinfunction "22_22") (pintype "bidirectional"))
      (node (ref "R44") (pin "1") (pinfunction "1_1") (pintype "passive"))
    )
    (net (code "255") (name "P45") (class "Default")
      (node (ref "HEADER-29P2") (pin "23") (pinfunction "23_23") (pintype "bidirectional"))
      (node (ref "R45") (pin "1") (pinfunction "1_1") (pintype "passive"))
    )
    (net (code "256") (name "P46") (class "Default")
      (node (ref "HEADER-29P2") (pin "24") (pinfunction "24_24") (pintype "bidirectional"))
      (node (ref "R46") (pin "1") (pinfunction "1_1") (pintype "passive"))
    )
    (net (code "257") (name "P47") (class "Default")
      (node (ref "HEADER-29P2") (pin "25") (pinfunction "25_25") (pintype "bidirectional"))
      (node (ref "R47") (pin "1") (pinfunction "1_1") (pintype "passive"))
    )
    (net (code "258") (name "P48") (class "Default")
      (node (ref "HEADER-29P2") (pin "26") (pinfunction "26_26") (pintype "bidirectional"))
      (node (ref "R48") (pin "1") (pinfunction "1_1") (pintype "passive"))
    )
    (net (code "259") (name "RELAY") (class "Default")
      (node (ref "R115") (pin "2") (pinfunction "2_2") (pintype "passive"))
      (node (ref "U3") (pin "26") (pinfunction "IO4_26") (pintype "bidirectional"))
    )
    (net (code "260") (name "RTS") (class "Default")
      (node (ref "Q2") (pin "2") (pinfunction "E_2") (pintype "passive"))
      (node (ref "R118") (pin "1") (pinfunction "1_1") (pintype "passive"))
      (node (ref "U1") (pin "14") (pinfunction "~{RTS}_14") (pintype "output"))
    )
    (net (code "261") (name "RX") (class "Default")
      (node (ref "D53") (pin "C") (pinfunction "C_C") (pintype "passive"))
      (node (ref "U1") (pin "3") (pinfunction "RXD_3") (pintype "input"))
      (node (ref "U3") (pin "35") (pinfunction "TXD0_35") (pintype "bidirectional"))
    )
    (net (code "262") (name "RX-RS485") (class "Default")
      (node (ref "TTL-RS1") (pin "RX") (pinfunction "RX_RX") (pintype "bidirectional"))
      (node (ref "U3") (pin "28") (pinfunction "IO17_28") (pintype "bidirectional"))
    )
    (net (code "263") (name "RX_BACKUP") (class "Default")
      (node (ref "JP1") (pin "2") (pinfunction "2_2") (pintype "passive"))
      (node (ref "U3") (pin "9") (pinfunction "IO33_9") (pintype "bidirectional"))
    )
    (net (code "264") (name "SCK_VSPI") (class "Default")
      (node (ref "U$1") (pin "SCLK") (pinfunction "SCLK_SCLK") (pintype "bidirectional"))
      (node (ref "U3") (pin "30") (pinfunction "IO18_30") (pintype "bidirectional"))
    )
    (net (code "265") (name "SCL") (class "Default")
      (node (ref "IC1") (pin "12") (pinfunction "SCL_12") (pintype "input"))
      (node (ref "IC4") (pin "12") (pinfunction "SCL_12") (pintype "input"))
      (node (ref "IC5") (pin "12") (pinfunction "SCL_12") (pintype "input"))
      (node (ref "R101") (pin "1") (pinfunction "1_1") (pintype "passive"))
      (node (ref "R97") (pin "1") (pinfunction "1_1") (pintype "passive"))
      (node (ref "R99") (pin "1") (pinfunction "1_1") (pintype "passive"))
      (node (ref "RTC1") (pin "SCL") (pinfunction "SCL_SCL") (pintype "bidirectional"))
      (node (ref "U3") (pin "36") (pinfunction "IO22_36") (pintype "bidirectional"))
    )
    (net (code "266") (name "SDA") (class "Default")
      (node (ref "IC1") (pin "13") (pinfunction "SDA_13") (pintype "bidirectional"))
      (node (ref "IC4") (pin "13") (pinfunction "SDA_13") (pintype "bidirectional"))
      (node (ref "IC5") (pin "13") (pinfunction "SDA_13") (pintype "bidirectional"))
      (node (ref "R100") (pin "1") (pinfunction "1_1") (pintype "passive"))
      (node (ref "R102") (pin "1") (pinfunction "1_1") (pintype "passive"))
      (node (ref "R98") (pin "1") (pinfunction "1_1") (pintype "passive"))
      (node (ref "RTC1") (pin "SDA") (pinfunction "SDA_SDA") (pintype "bidirectional"))
      (node (ref "U3") (pin "33") (pinfunction "IO21_33") (pintype "bidirectional"))
    )
    (net (code "267") (name "SS_LAN") (class "Default")
      (node (ref "U$1") (pin "CS") (pinfunction "CS_CS") (pintype "bidirectional"))
      (node (ref "U3") (pin "29") (pinfunction "IO5_29") (pintype "bidirectional"))
    )
    (net (code "268") (name "TESTING") (class "Default")
      (node (ref "R126") (pin "1") (pinfunction "1_1") (pintype "passive"))
      (node (ref "U3") (pin "14") (pinfunction "IO12_14") (pintype "bidirectional"))
    )
    (net (code "269") (name "TESTING1") (class "Default")
      (node (ref "R129") (pin "1") (pinfunction "1_1") (pintype "passive"))
      (node (ref "U3") (pin "16") (pinfunction "IO13_16") (pintype "bidirectional"))
    )
    (net (code "270") (name "TESTING2") (class "Default")
      (node (ref "R132") (pin "1") (pinfunction "1_1") (pintype "passive"))
      (node (ref "U3") (pin "13") (pinfunction "IO14_13") (pintype "bidirectional"))
    )
    (net (code "271") (name "TESTING3") (class "Default")
      (node (ref "R135") (pin "1") (pinfunction "1_1") (pintype "passive"))
      (node (ref "U3") (pin "23") (pinfunction "IO15_23") (pintype "bidirectional"))
    )
    (net (code "272") (name "TX") (class "Default")
      (node (ref "D52") (pin "C") (pinfunction "C_C") (pintype "passive"))
      (node (ref "U1") (pin "2") (pinfunction "TXD_2") (pintype "output"))
      (node (ref "U3") (pin "34") (pinfunction "RXD0_34") (pintype "bidirectional"))
    )
    (net (code "273") (name "TX-RS485") (class "Default")
      (node (ref "TTL-RS1") (pin "TX") (pinfunction "TX_TX") (pintype "bidirectional"))
      (node (ref "U3") (pin "27") (pinfunction "IO16_27") (pintype "bidirectional"))
    )
    (net (code "274") (name "TX_BACKUP") (class "Default")
      (node (ref "JP1") (pin "3") (pinfunction "3_3") (pintype "passive"))
      (node (ref "U3") (pin "8") (pinfunction "IO32_8") (pintype "bidirectional"))
    )
    (net (code "275") (name "UJIDEVICE000") (class "Default")
      (node (ref "D79") (pin "A") (pinfunction "A_A") (pintype "passive"))
      (node (ref "D80") (pin "A") (pinfunction "A_A") (pintype "passive"))
      (node (ref "D81") (pin "A") (pinfunction "A_A") (pintype "passive"))
      (node (ref "D82") (pin "A") (pinfunction "A_A") (pintype "passive"))
      (node (ref "D83") (pin "A") (pinfunction "A_A") (pintype "passive"))
      (node (ref "D84") (pin "A") (pinfunction "A_A") (pintype "passive"))
      (node (ref "D85") (pin "A") (pinfunction "A_A") (pintype "passive"))
      (node (ref "D86") (pin "A") (pinfunction "A_A") (pintype "passive"))
      (node (ref "D87") (pin "A") (pinfunction "A_A") (pintype "passive"))
      (node (ref "D88") (pin "A") (pinfunction "A_A") (pintype "passive"))
      (node (ref "D89") (pin "A") (pinfunction "A_A") (pintype "passive"))
      (node (ref "D90") (pin "A") (pinfunction "A_A") (pintype "passive"))
      (node (ref "Q7") (pin "2") (pinfunction "E_2") (pintype "passive"))
      (node (ref "R134") (pin "2") (pinfunction "2_2") (pintype "passive"))
    )
    (net (code "276") (name "UJIDEVICE0000") (class "Default")
      (node (ref "D100") (pin "A") (pinfunction "A_A") (pintype "passive"))
      (node (ref "D101") (pin "A") (pinfunction "A_A") (pintype "passive"))
      (node (ref "D102") (pin "A") (pinfunction "A_A") (pintype "passive"))
      (node (ref "D91") (pin "A") (pinfunction "A_A") (pintype "passive"))
      (node (ref "D92") (pin "A") (pinfunction "A_A") (pintype "passive"))
      (node (ref "D93") (pin "A") (pinfunction "A_A") (pintype "passive"))
      (node (ref "D94") (pin "A") (pinfunction "A_A") (pintype "passive"))
      (node (ref "D95") (pin "A") (pinfunction "A_A") (pintype "passive"))
      (node (ref "D96") (pin "A") (pinfunction "A_A") (pintype "passive"))
      (node (ref "D97") (pin "A") (pinfunction "A_A") (pintype "passive"))
      (node (ref "D98") (pin "A") (pinfunction "A_A") (pintype "passive"))
      (node (ref "D99") (pin "A") (pinfunction "A_A") (pintype "passive"))
      (node (ref "Q8") (pin "2") (pinfunction "E_2") (pintype "passive"))
      (node (ref "R137") (pin "2") (pinfunction "2_2") (pintype "passive"))
    )
    (net (code "277") (name "UJIDEVICE00") (class "Default")
      (node (ref "D67") (pin "A") (pinfunction "A_A") (pintype "passive"))
      (node (ref "D68") (pin "A") (pinfunction "A_A") (pintype "passive"))
      (node (ref "D69") (pin "A") (pinfunction "A_A") (pintype "passive"))
      (node (ref "D70") (pin "A") (pinfunction "A_A") (pintype "passive"))
      (node (ref "D71") (pin "A") (pinfunction "A_A") (pintype "passive"))
      (node (ref "D72") (pin "A") (pinfunction "A_A") (pintype "passive"))
      (node (ref "D73") (pin "A") (pinfunction "A_A") (pintype "passive"))
      (node (ref "D74") (pin "A") (pinfunction "A_A") (pintype "passive"))
      (node (ref "D75") (pin "A") (pinfunction "A_A") (pintype "passive"))
      (node (ref "D76") (pin "A") (pinfunction "A_A") (pintype "passive"))
      (node (ref "D77") (pin "A") (pinfunction "A_A") (pintype "passive"))
      (node (ref "D78") (pin "A") (pinfunction "A_A") (pintype "passive"))
      (node (ref "Q6") (pin "2") (pinfunction "E_2") (pintype "passive"))
      (node (ref "R131") (pin "2") (pinfunction "2_2") (pintype "passive"))
    )
    (net (code "278") (name "UJIDEVICE0") (class "Default")
      (node (ref "D55") (pin "A") (pinfunction "A_A") (pintype "passive"))
      (node (ref "D56") (pin "A") (pinfunction "A_A") (pintype "passive"))
      (node (ref "D57") (pin "A") (pinfunction "A_A") (pintype "passive"))
      (node (ref "D58") (pin "A") (pinfunction "A_A") (pintype "passive"))
      (node (ref "D59") (pin "A") (pinfunction "A_A") (pintype "passive"))
      (node (ref "D60") (pin "A") (pinfunction "A_A") (pintype "passive"))
      (node (ref "D61") (pin "A") (pinfunction "A_A") (pintype "passive"))
      (node (ref "D62") (pin "A") (pinfunction "A_A") (pintype "passive"))
      (node (ref "D63") (pin "A") (pinfunction "A_A") (pintype "passive"))
      (node (ref "D64") (pin "A") (pinfunction "A_A") (pintype "passive"))
      (node (ref "D65") (pin "A") (pinfunction "A_A") (pintype "passive"))
      (node (ref "D66") (pin "A") (pinfunction "A_A") (pintype "passive"))
      (node (ref "Q5") (pin "2") (pinfunction "E_2") (pintype "passive"))
      (node (ref "R128") (pin "2") (pinfunction "2_2") (pintype "passive"))
    )
    (net (code "279") (name "UJIDEVICE1") (class "Default")
      (node (ref "D2") (pin "C") (pinfunction "K_C") (pintype "passive"))
      (node (ref "D55") (pin "C") (pinfunction "K_C") (pintype "passive"))
      (node (ref "LED1") (pin "+") (pinfunction "+_+") (pintype "passive"))
    )
    (net (code "280") (name "UJIDEVICE2") (class "Default")
      (node (ref "D3") (pin "C") (pinfunction "K_C") (pintype "passive"))
      (node (ref "D56") (pin "C") (pinfunction "K_C") (pintype "passive"))
      (node (ref "LED2") (pin "+") (pinfunction "+_+") (pintype "passive"))
    )
    (net (code "281") (name "UJIDEVICE3") (class "Default")
      (node (ref "D4") (pin "C") (pinfunction "K_C") (pintype "passive"))
      (node (ref "D57") (pin "C") (pinfunction "K_C") (pintype "passive"))
      (node (ref "LED3") (pin "+") (pinfunction "+_+") (pintype "passive"))
    )
    (net (code "282") (name "UJIDEVICE4") (class "Default")
      (node (ref "D5") (pin "C") (pinfunction "K_C") (pintype "passive"))
      (node (ref "D58") (pin "C") (pinfunction "K_C") (pintype "passive"))
      (node (ref "LED4") (pin "+") (pinfunction "+_+") (pintype "passive"))
    )
    (net (code "283") (name "UJIDEVICE5") (class "Default")
      (node (ref "D59") (pin "C") (pinfunction "K_C") (pintype "passive"))
      (node (ref "D6") (pin "C") (pinfunction "K_C") (pintype "passive"))
      (node (ref "LED5") (pin "+") (pinfunction "+_+") (pintype "passive"))
    )
    (net (code "284") (name "UJIDEVICE6") (class "Default")
      (node (ref "D60") (pin "C") (pinfunction "K_C") (pintype "passive"))
      (node (ref "D7") (pin "C") (pinfunction "K_C") (pintype "passive"))
      (node (ref "LED6") (pin "+") (pinfunction "+_+") (pintype "passive"))
    )
    (net (code "285") (name "UJIDEVICE7") (class "Default")
      (node (ref "D61") (pin "C") (pinfunction "K_C") (pintype "passive"))
      (node (ref "D8") (pin "C") (pinfunction "K_C") (pintype "passive"))
      (node (ref "LED7") (pin "+") (pinfunction "+_+") (pintype "passive"))
    )
    (net (code "286") (name "UJIDEVICE8") (class "Default")
      (node (ref "D62") (pin "C") (pinfunction "K_C") (pintype "passive"))
      (node (ref "D9") (pin "C") (pinfunction "K_C") (pintype "passive"))
      (node (ref "LED8") (pin "+") (pinfunction "+_+") (pintype "passive"))
    )
    (net (code "287") (name "UJIDEVICE9") (class "Default")
      (node (ref "D10") (pin "C") (pinfunction "K_C") (pintype "passive"))
      (node (ref "D63") (pin "C") (pinfunction "K_C") (pintype "passive"))
      (node (ref "LED9") (pin "+") (pinfunction "+_+") (pintype "passive"))
    )
    (net (code "288") (name "UJIDEVICE10") (class "Default")
      (node (ref "D11") (pin "C") (pinfunction "K_C") (pintype "passive"))
      (node (ref "D64") (pin "C") (pinfunction "K_C") (pintype "passive"))
      (node (ref "LED10") (pin "+") (pinfunction "+_+") (pintype "passive"))
    )
    (net (code "289") (name "UJIDEVICE11") (class "Default")
      (node (ref "D12") (pin "C") (pinfunction "K_C") (pintype "passive"))
      (node (ref "D65") (pin "C") (pinfunction "K_C") (pintype "passive"))
      (node (ref "LED11") (pin "+") (pinfunction "+_+") (pintype "passive"))
    )
    (net (code "290") (name "UJIDEVICE12") (class "Default")
      (node (ref "D13") (pin "C") (pinfunction "K_C") (pintype "passive"))
      (node (ref "D66") (pin "C") (pinfunction "K_C") (pintype "passive"))
      (node (ref "LED12") (pin "+") (pinfunction "+_+") (pintype "passive"))
    )
    (net (code "291") (name "UJIDEVICE13") (class "Default")
      (node (ref "D14") (pin "C") (pinfunction "K_C") (pintype "passive"))
      (node (ref "D67") (pin "C") (pinfunction "K_C") (pintype "passive"))
      (node (ref "LED13") (pin "+") (pinfunction "+_+") (pintype "passive"))
    )
    (net (code "292") (name "UJIDEVICE14") (class "Default")
      (node (ref "D15") (pin "C") (pinfunction "K_C") (pintype "passive"))
      (node (ref "D68") (pin "C") (pinfunction "K_C") (pintype "passive"))
      (node (ref "LED14") (pin "+") (pinfunction "+_+") (pintype "passive"))
    )
    (net (code "293") (name "UJIDEVICE15") (class "Default")
      (node (ref "D16") (pin "C") (pinfunction "K_C") (pintype "passive"))
      (node (ref "D69") (pin "C") (pinfunction "K_C") (pintype "passive"))
      (node (ref "LED15") (pin "+") (pinfunction "+_+") (pintype "passive"))
    )
    (net (code "294") (name "UJIDEVICE16") (class "Default")
      (node (ref "D17") (pin "C") (pinfunction "K_C") (pintype "passive"))
      (node (ref "D70") (pin "C") (pinfunction "K_C") (pintype "passive"))
      (node (ref "LED16") (pin "+") (pinfunction "+_+") (pintype "passive"))
    )
    (net (code "295") (name "UJIDEVICE17") (class "Default")
      (node (ref "D18") (pin "C") (pinfunction "K_C") (pintype "passive"))
      (node (ref "D71") (pin "C") (pinfunction "K_C") (pintype "passive"))
      (node (ref "LED17") (pin "+") (pinfunction "+_+") (pintype "passive"))
    )
    (net (code "296") (name "UJIDEVICE18") (class "Default")
      (node (ref "D19") (pin "C") (pinfunction "K_C") (pintype "passive"))
      (node (ref "D72") (pin "C") (pinfunction "K_C") (pintype "passive"))
      (node (ref "LED18") (pin "+") (pinfunction "+_+") (pintype "passive"))
    )
    (net (code "297") (name "UJIDEVICE19") (class "Default")
      (node (ref "D20") (pin "C") (pinfunction "K_C") (pintype "passive"))
      (node (ref "D73") (pin "C") (pinfunction "K_C") (pintype "passive"))
      (node (ref "LED19") (pin "+") (pinfunction "+_+") (pintype "passive"))
    )
    (net (code "298") (name "UJIDEVICE20") (class "Default")
      (node (ref "D21") (pin "C") (pinfunction "K_C") (pintype "passive"))
      (node (ref "D74") (pin "C") (pinfunction "K_C") (pintype "passive"))
      (node (ref "LED20") (pin "+") (pinfunction "+_+") (pintype "passive"))
    )
    (net (code "299") (name "UJIDEVICE21") (class "Default")
      (node (ref "D22") (pin "C") (pinfunction "K_C") (pintype "passive"))
      (node (ref "D75") (pin "C") (pinfunction "K_C") (pintype "passive"))
      (node (ref "LED21") (pin "+") (pinfunction "+_+") (pintype "passive"))
    )
    (net (code "300") (name "UJIDEVICE22") (class "Default")
      (node (ref "D23") (pin "C") (pinfunction "K_C") (pintype "passive"))
      (node (ref "D76") (pin "C") (pinfunction "K_C") (pintype "passive"))
      (node (ref "LED22") (pin "+") (pinfunction "+_+") (pintype "passive"))
    )
    (net (code "301") (name "UJIDEVICE23") (class "Default")
      (node (ref "D24") (pin "C") (pinfunction "K_C") (pintype "passive"))
      (node (ref "D77") (pin "C") (pinfunction "K_C") (pintype "passive"))
      (node (ref "LED23") (pin "+") (pinfunction "+_+") (pintype "passive"))
    )
    (net (code "302") (name "UJIDEVICE24") (class "Default")
      (node (ref "D25") (pin "C") (pinfunction "K_C") (pintype "passive"))
      (node (ref "D78") (pin "C") (pinfunction "K_C") (pintype "passive"))
      (node (ref "LED24") (pin "+") (pinfunction "+_+") (pintype "passive"))
    )
    (net (code "303") (name "UJIDEVICE25") (class "Default")
      (node (ref "D26") (pin "C") (pinfunction "K_C") (pintype "passive"))
      (node (ref "D79") (pin "C") (pinfunction "K_C") (pintype "passive"))
      (node (ref "LED25") (pin "+") (pinfunction "+_+") (pintype "passive"))
    )
    (net (code "304") (name "UJIDEVICE26") (class "Default")
      (node (ref "D27") (pin "C") (pinfunction "K_C") (pintype "passive"))
      (node (ref "D80") (pin "C") (pinfunction "K_C") (pintype "passive"))
      (node (ref "LED26") (pin "+") (pinfunction "+_+") (pintype "passive"))
    )
    (net (code "305") (name "UJIDEVICE27") (class "Default")
      (node (ref "D28") (pin "C") (pinfunction "K_C") (pintype "passive"))
      (node (ref "D81") (pin "C") (pinfunction "K_C") (pintype "passive"))
      (node (ref "LED27") (pin "+") (pinfunction "+_+") (pintype "passive"))
    )
    (net (code "306") (name "UJIDEVICE28") (class "Default")
      (node (ref "D29") (pin "C") (pinfunction "K_C") (pintype "passive"))
      (node (ref "D82") (pin "C") (pinfunction "K_C") (pintype "passive"))
      (node (ref "LED28") (pin "+") (pinfunction "+_+") (pintype "passive"))
    )
    (net (code "307") (name "UJIDEVICE29") (class "Default")
      (node (ref "D30") (pin "C") (pinfunction "K_C") (pintype "passive"))
      (node (ref "D83") (pin "C") (pinfunction "K_C") (pintype "passive"))
      (node (ref "LED29") (pin "+") (pinfunction "+_+") (pintype "passive"))
    )
    (net (code "308") (name "UJIDEVICE30") (class "Default")
      (node (ref "D31") (pin "C") (pinfunction "K_C") (pintype "passive"))
      (node (ref "D84") (pin "C") (pinfunction "K_C") (pintype "passive"))
      (node (ref "LED30") (pin "+") (pinfunction "+_+") (pintype "passive"))
    )
    (net (code "309") (name "UJIDEVICE31") (class "Default")
      (node (ref "D32") (pin "C") (pinfunction "K_C") (pintype "passive"))
      (node (ref "D85") (pin "C") (pinfunction "K_C") (pintype "passive"))
      (node (ref "LED31") (pin "+") (pinfunction "+_+") (pintype "passive"))
    )
    (net (code "310") (name "UJIDEVICE32") (class "Default")
      (node (ref "D33") (pin "C") (pinfunction "K_C") (pintype "passive"))
      (node (ref "D86") (pin "C") (pinfunction "K_C") (pintype "passive"))
      (node (ref "LED32") (pin "+") (pinfunction "+_+") (pintype "passive"))
    )
    (net (code "311") (name "UJIDEVICE33") (class "Default")
      (node (ref "D34") (pin "C") (pinfunction "K_C") (pintype "passive"))
      (node (ref "D87") (pin "C") (pinfunction "K_C") (pintype "passive"))
      (node (ref "LED33") (pin "+") (pinfunction "+_+") (pintype "passive"))
    )
    (net (code "312") (name "UJIDEVICE34") (class "Default")
      (node (ref "D35") (pin "C") (pinfunction "K_C") (pintype "passive"))
      (node (ref "D88") (pin "C") (pinfunction "K_C") (pintype "passive"))
      (node (ref "LED34") (pin "+") (pinfunction "+_+") (pintype "passive"))
    )
    (net (code "313") (name "UJIDEVICE35") (class "Default")
      (node (ref "D36") (pin "C") (pinfunction "K_C") (pintype "passive"))
      (node (ref "D89") (pin "C") (pinfunction "K_C") (pintype "passive"))
      (node (ref "LED35") (pin "+") (pinfunction "+_+") (pintype "passive"))
    )
    (net (code "314") (name "UJIDEVICE36") (class "Default")
      (node (ref "D37") (pin "C") (pinfunction "K_C") (pintype "passive"))
      (node (ref "D90") (pin "C") (pinfunction "K_C") (pintype "passive"))
      (node (ref "LED36") (pin "+") (pinfunction "+_+") (pintype "passive"))
    )
    (net (code "315") (name "UJIDEVICE37") (class "Default")
      (node (ref "D38") (pin "C") (pinfunction "K_C") (pintype "passive"))
      (node (ref "D91") (pin "C") (pinfunction "K_C") (pintype "passive"))
      (node (ref "LED37") (pin "+") (pinfunction "+_+") (pintype "passive"))
    )
    (net (code "316") (name "UJIDEVICE38") (class "Default")
      (node (ref "D39") (pin "C") (pinfunction "K_C") (pintype "passive"))
      (node (ref "D92") (pin "C") (pinfunction "K_C") (pintype "passive"))
      (node (ref "LED38") (pin "+") (pinfunction "+_+") (pintype "passive"))
    )
    (net (code "317") (name "UJIDEVICE39") (class "Default")
      (node (ref "D40") (pin "C") (pinfunction "K_C") (pintype "passive"))
      (node (ref "D93") (pin "C") (pinfunction "K_C") (pintype "passive"))
      (node (ref "LED39") (pin "+") (pinfunction "+_+") (pintype "passive"))
    )
    (net (code "318") (name "UJIDEVICE40") (class "Default")
      (node (ref "D41") (pin "C") (pinfunction "K_C") (pintype "passive"))
      (node (ref "D94") (pin "C") (pinfunction "K_C") (pintype "passive"))
      (node (ref "LED40") (pin "+") (pinfunction "+_+") (pintype "passive"))
    )
    (net (code "319") (name "UJIDEVICE41") (class "Default")
      (node (ref "D42") (pin "C") (pinfunction "K_C") (pintype "passive"))
      (node (ref "D95") (pin "C") (pinfunction "K_C") (pintype "passive"))
      (node (ref "LED41") (pin "+") (pinfunction "+_+") (pintype "passive"))
    )
    (net (code "320") (name "UJIDEVICE42") (class "Default")
      (node (ref "D43") (pin "C") (pinfunction "K_C") (pintype "passive"))
      (node (ref "D96") (pin "C") (pinfunction "K_C") (pintype "passive"))
      (node (ref "LED42") (pin "+") (pinfunction "+_+") (pintype "passive"))
    )
    (net (code "321") (name "UJIDEVICE43") (class "Default")
      (node (ref "D44") (pin "C") (pinfunction "K_C") (pintype "passive"))
      (node (ref "D97") (pin "C") (pinfunction "K_C") (pintype "passive"))
      (node (ref "LED43") (pin "+") (pinfunction "+_+") (pintype "passive"))
    )
    (net (code "322") (name "UJIDEVICE44") (class "Default")
      (node (ref "D45") (pin "C") (pinfunction "K_C") (pintype "passive"))
      (node (ref "D98") (pin "C") (pinfunction "K_C") (pintype "passive"))
      (node (ref "LED44") (pin "+") (pinfunction "+_+") (pintype "passive"))
    )
    (net (code "323") (name "UJIDEVICE45") (class "Default")
      (node (ref "D46") (pin "C") (pinfunction "K_C") (pintype "passive"))
      (node (ref "D99") (pin "C") (pinfunction "K_C") (pintype "passive"))
      (node (ref "LED45") (pin "+") (pinfunction "+_+") (pintype "passive"))
    )
    (net (code "324") (name "UJIDEVICE46") (class "Default")
      (node (ref "D100") (pin "C") (pinfunction "K_C") (pintype "passive"))
      (node (ref "D47") (pin "C") (pinfunction "K_C") (pintype "passive"))
      (node (ref "LED46") (pin "+") (pinfunction "+_+") (pintype "passive"))
    )
    (net (code "325") (name "UJIDEVICE47") (class "Default")
      (node (ref "D101") (pin "C") (pinfunction "K_C") (pintype "passive"))
      (node (ref "D48") (pin "C") (pinfunction "K_C") (pintype "passive"))
      (node (ref "LED47") (pin "+") (pinfunction "+_+") (pintype "passive"))
    )
    (net (code "326") (name "UJIDEVICE48") (class "Default")
      (node (ref "D102") (pin "C") (pinfunction "K_C") (pintype "passive"))
      (node (ref "D49") (pin "C") (pinfunction "K_C") (pintype "passive"))
      (node (ref "LED48") (pin "+") (pinfunction "+_+") (pintype "passive"))
    )
    (net (code "327") (name "USB_N") (class "Default")
      (node (ref "J3") (pin "2") (pinfunction "D-_2") (pintype "passive"))
      (node (ref "U1") (pin "6") (pinfunction "UD-_6") (pintype "bidirectional"))
    )
    (net (code "328") (name "USB_P") (class "Default")
      (node (ref "J3") (pin "3") (pinfunction "D+_3") (pintype "passive"))
      (node (ref "U1") (pin "5") (pinfunction "UD+_5") (pintype "bidirectional"))
    )
    (net (code "329") (name "VCC") (class "Default")
      (node (ref "C9") (pin "1") (pinfunction "1_1") (pintype "passive"))
      (node (ref "IC1") (pin "9") (pinfunction "VDD_9") (pintype "power_in"))
      (node (ref "IC4") (pin "9") (pinfunction "VDD_9") (pintype "power_in"))
      (node (ref "IC5") (pin "9") (pinfunction "VDD_9") (pintype "power_in"))
      (node (ref "R100") (pin "2") (pinfunction "2_2") (pintype "passive"))
      (node (ref "R101") (pin "2") (pinfunction "2_2") (pintype "passive"))
      (node (ref "R102") (pin "2") (pinfunction "2_2") (pintype "passive"))
      (node (ref "R103") (pin "1") (pinfunction "1_1") (pintype "passive"))
      (node (ref "R107") (pin "2") (pinfunction "2_2") (pintype "passive"))
      (node (ref "R108") (pin "1") (pinfunction "1_1") (pintype "passive"))
      (node (ref "R111") (pin "1") (pinfunction "1_1") (pintype "passive"))
      (node (ref "R113") (pin "1") (pinfunction "1_1") (pintype "passive"))
      (node (ref "R119") (pin "2") (pinfunction "2_2") (pintype "passive"))
      (node (ref "R120") (pin "2") (pinfunction "2_2") (pintype "passive"))
      (node (ref "R121") (pin "2") (pinfunction "2_2") (pintype "passive"))
      (node (ref "R122") (pin "2") (pinfunction "2_2") (pintype "passive"))
      (node (ref "R49") (pin "2") (pinfunction "2_2") (pintype "passive"))
      (node (ref "R50") (pin "2") (pinfunction "2_2") (pintype "passive"))
      (node (ref "R51") (pin "2") (pinfunction "2_2") (pintype "passive"))
      (node (ref "R52") (pin "2") (pinfunction "2_2") (pintype "passive"))
      (node (ref "R53") (pin "2") (pinfunction "2_2") (pintype "passive"))
      (node (ref "R54") (pin "2") (pinfunction "2_2") (pintype "passive"))
      (node (ref "R55") (pin "2") (pinfunction "2_2") (pintype "passive"))
      (node (ref "R56") (pin "2") (pinfunction "2_2") (pintype "passive"))
      (node (ref "R57") (pin "2") (pinfunction "2_2") (pintype "passive"))
      (node (ref "R58") (pin "2") (pinfunction "2_2") (pintype "passive"))
      (node (ref "R59") (pin "2") (pinfunction "2_2") (pintype "passive"))
      (node (ref "R60") (pin "2") (pinfunction "2_2") (pintype "passive"))
      (node (ref "R61") (pin "2") (pinfunction "2_2") (pintype "passive"))
      (node (ref "R62") (pin "2") (pinfunction "2_2") (pintype "passive"))
      (node (ref "R63") (pin "2") (pinfunction "2_2") (pintype "passive"))
      (node (ref "R64") (pin "2") (pinfunction "2_2") (pintype "passive"))
      (node (ref "R65") (pin "2") (pinfunction "2_2") (pintype "passive"))
      (node (ref "R66") (pin "2") (pinfunction "2_2") (pintype "passive"))
      (node (ref "R67") (pin "2") (pinfunction "2_2") (pintype "passive"))
      (node (ref "R68") (pin "2") (pinfunction "2_2") (pintype "passive"))
      (node (ref "R69") (pin "2") (pinfunction "2_2") (pintype "passive"))
      (node (ref "R70") (pin "2") (pinfunction "2_2") (pintype "passive"))
      (node (ref "R71") (pin "2") (pinfunction "2_2") (pintype "passive"))
      (node (ref "R72") (pin "2") (pinfunction "2_2") (pintype "passive"))
      (node (ref "R73") (pin "2") (pinfunction "2_2") (pintype "passive"))
      (node (ref "R74") (pin "2") (pinfunction "2_2") (pintype "passive"))
      (node (ref "R75") (pin "2") (pinfunction "2_2") (pintype "passive"))
      (node (ref "R76") (pin "2") (pinfunction "2_2") (pintype "passive"))
      (node (ref "R77") (pin "2") (pinfunction "2_2") (pintype "passive"))
      (node (ref "R78") (pin "2") (pinfunction "2_2") (pintype "passive"))
      (node (ref "R79") (pin "2") (pinfunction "2_2") (pintype "passive"))
      (node (ref "R80") (pin "2") (pinfunction "2_2") (pintype "passive"))
      (node (ref "R81") (pin "2") (pinfunction "2_2") (pintype "passive"))
      (node (ref "R82") (pin "2") (pinfunction "2_2") (pintype "passive"))
      (node (ref "R83") (pin "2") (pinfunction "2_2") (pintype "passive"))
      (node (ref "R84") (pin "2") (pinfunction "2_2") (pintype "passive"))
      (node (ref "R85") (pin "2") (pinfunction "2_2") (pintype "passive"))
      (node (ref "R86") (pin "2") (pinfunction "2_2") (pintype "passive"))
      (node (ref "R87") (pin "2") (pinfunction "2_2") (pintype "passive"))
      (node (ref "R88") (pin "2") (pinfunction "2_2") (pintype "passive"))
      (node (ref "R89") (pin "2") (pinfunction "2_2") (pintype "passive"))
      (node (ref "R90") (pin "2") (pinfunction "2_2") (pintype "passive"))
      (node (ref "R91") (pin "2") (pinfunction "2_2") (pintype "passive"))
      (node (ref "R92") (pin "2") (pinfunction "2_2") (pintype "passive"))
      (node (ref "R93") (pin "2") (pinfunction "2_2") (pintype "passive"))
      (node (ref "R94") (pin "2") (pinfunction "2_2") (pintype "passive"))
      (node (ref "R95") (pin "2") (pinfunction "2_2") (pintype "passive"))
      (node (ref "R96") (pin "2") (pinfunction "2_2") (pintype "passive"))
      (node (ref "R97") (pin "2") (pinfunction "2_2") (pintype "passive"))
      (node (ref "R98") (pin "2") (pinfunction "2_2") (pintype "passive"))
      (node (ref "R99") (pin "2") (pinfunction "2_2") (pintype "passive"))
      (node (ref "RTC1") (pin "VCC") (pinfunction "VCC_VCC") (pintype "bidirectional"))
      (node (ref "U$1") (pin "3V3") (pinfunction "3V3_3V3") (pintype "bidirectional"))
      (node (ref "U$1") (pin "3V3.2") (pinfunction "3V3.2_3V3.2") (pintype "bidirectional"))
      (node (ref "U2") (pin "2") (pinfunction "VOUT_2") (pintype "output"))
      (node (ref "U2") (pin "4") (pinfunction "VOUT_4") (pintype "output"))
      (node (ref "U3") (pin "2") (pinfunction "3V3_2") (pintype "power_in"))
    )
    (net (code "330") (name "VUSB") (class "Default")
      (node (ref "C1") (pin "1") (pinfunction "1_1") (pintype "passive"))
      (node (ref "C2") (pin "+") (pinfunction "+_+") (pintype "passive"))
      (node (ref "D51") (pin "A") (pinfunction "A_A") (pintype "passive"))
      (node (ref "J3") (pin "1") (pinfunction "VUSB_1") (pintype "passive"))
      (node (ref "U1") (pin "16") (pinfunction "VCC_16") (pintype "power_in"))
    )
    (net (code "331") (name "unconnected-(HEADER-29P2-Pad7)") (class "Default")
      (node (ref "HEADER-29P2") (pin "7") (pinfunction "7_7") (pintype "bidirectional"))
    )
    (net (code "332") (name "unconnected-(IC1-INTA-Pad20)") (class "Default")
      (node (ref "IC1") (pin "20") (pinfunction "INTA_20") (pintype "output"))
    )
    (net (code "333") (name "unconnected-(IC1-INTB-Pad19)") (class "Default")
      (node (ref "IC1") (pin "19") (pinfunction "INTB_19") (pintype "output"))
    )
    (net (code "334") (name "unconnected-(IC4-INTA-Pad20)") (class "Default")
      (node (ref "IC4") (pin "20") (pinfunction "INTA_20") (pintype "output"))
    )
    (net (code "335") (name "unconnected-(IC4-INTB-Pad19)") (class "Default")
      (node (ref "IC4") (pin "19") (pinfunction "INTB_19") (pintype "output"))
    )
    (net (code "336") (name "unconnected-(IC5-INTA-Pad20)") (class "Default")
      (node (ref "IC5") (pin "20") (pinfunction "INTA_20") (pintype "output"))
    )
    (net (code "337") (name "unconnected-(IC5-INTB-Pad19)") (class "Default")
      (node (ref "IC5") (pin "19") (pinfunction "INTB_19") (pintype "output"))
    )
    (net (code "338") (name "unconnected-(J3-ID-Pad4)") (class "Default")
      (node (ref "J3") (pin "4") (pinfunction "ID_4") (pintype "passive"))
    )
    (net (code "339") (name "unconnected-(K2C-O-PadO2)") (class "Default")
      (node (ref "K2") (pin "O2") (pinfunction "O_O2") (pintype "passive"))
    )
    (net (code "340") (name "unconnected-(K2C-P-PadP2)") (class "Default")
      (node (ref "K2") (pin "P2") (pinfunction "P_P2") (pintype "passive"))
    )
    (net (code "341") (name "unconnected-(K2C-S-PadS2)") (class "Default")
      (node (ref "K2") (pin "S2") (pinfunction "S_S2") (pintype "passive"))
    )
    (net (code "342") (name "unconnected-(RTC1-Pad32K)") (class "Default")
      (node (ref "RTC1") (pin "32K") (pinfunction "32K_32K") (pintype "bidirectional"))
    )
    (net (code "343") (name "unconnected-(RTC1-PadGND1)") (class "Default")
      (node (ref "RTC1") (pin "GND1") (pinfunction "GND1_GND1") (pintype "bidirectional"))
    )
    (net (code "344") (name "unconnected-(RTC1-PadSCL1)") (class "Default")
      (node (ref "RTC1") (pin "SCL1") (pinfunction "SCL1_SCL1") (pintype "bidirectional"))
    )
    (net (code "345") (name "unconnected-(RTC1-PadSDA1)") (class "Default")
      (node (ref "RTC1") (pin "SDA1") (pinfunction "SDA1_SDA1") (pintype "bidirectional"))
    )
    (net (code "346") (name "unconnected-(RTC1-PadSQW)") (class "Default")
      (node (ref "RTC1") (pin "SQW") (pinfunction "SQW_SQW") (pintype "bidirectional"))
    )
    (net (code "347") (name "unconnected-(RTC1-PadVCC1)") (class "Default")
      (node (ref "RTC1") (pin "VCC1") (pinfunction "VCC1_VCC1") (pintype "bidirectional"))
    )
    (net (code "348") (name "unconnected-(U$1-PadINT)") (class "Default")
      (node (ref "U$1") (pin "INT") (pinfunction "INT_INT") (pintype "bidirectional"))
    )
    (net (code "349") (name "unconnected-(U$1-PadNC)") (class "Default")
      (node (ref "U$1") (pin "NC") (pinfunction "NC_NC") (pintype "bidirectional"))
    )
    (net (code "350") (name "unconnected-(U$1-PadRST)") (class "Default")
      (node (ref "U$1") (pin "RST") (pinfunction "RST_RST") (pintype "bidirectional"))
    )
    (net (code "351") (name "unconnected-(U1-RS232-Pad15)") (class "Default")
      (node (ref "U1") (pin "15") (pinfunction "RS232_15") (pintype "input"))
    )
    (net (code "352") (name "unconnected-(U1-~{CTS}-Pad9)") (class "Default")
      (node (ref "U1") (pin "9") (pinfunction "~{CTS}_9") (pintype "input"))
    )
    (net (code "353") (name "unconnected-(U1-~{DCD}-Pad12)") (class "Default")
      (node (ref "U1") (pin "12") (pinfunction "~{DCD}_12") (pintype "input"))
    )
    (net (code "354") (name "unconnected-(U1-~{DSR}-Pad10)") (class "Default")
      (node (ref "U1") (pin "10") (pinfunction "~{DSR}_10") (pintype "input"))
    )
    (net (code "355") (name "unconnected-(U1-~{RI}-Pad11)") (class "Default")
      (node (ref "U1") (pin "11") (pinfunction "~{RI}_11") (pintype "input"))
    )
    (net (code "356") (name "unconnected-(U3-IO2-Pad24)") (class "Default")
      (node (ref "U3") (pin "24") (pinfunction "IO2_24") (pintype "bidirectional"))
    )
    (net (code "357") (name "unconnected-(U3-IO34-Pad6)") (class "Default")
      (node (ref "U3") (pin "6") (pinfunction "IO34_6") (pintype "input"))
    )
    (net (code "358") (name "unconnected-(U3-IO35-Pad7)") (class "Default")
      (node (ref "U3") (pin "7") (pinfunction "IO35_7") (pintype "input"))
    )
    (net (code "359") (name "unconnected-(U3-SCK{slash}CLK-Pad20)") (class "Default")
      (node (ref "U3") (pin "20") (pinfunction "SCK/CLK_20") (pintype "bidirectional"))
    )
    (net (code "360") (name "unconnected-(U3-SCS{slash}CMD-Pad19)") (class "Default")
      (node (ref "U3") (pin "19") (pinfunction "SCS/CMD_19") (pintype "bidirectional"))
    )
    (net (code "361") (name "unconnected-(U3-SDI{slash}SD1-Pad22)") (class "Default")
      (node (ref "U3") (pin "22") (pinfunction "SDI/SD1_22") (pintype "bidirectional"))
    )
    (net (code "362") (name "unconnected-(U3-SDO{slash}SD0-Pad21)") (class "Default")
      (node (ref "U3") (pin "21") (pinfunction "SDO/SD0_21") (pintype "bidirectional"))
    )
    (net (code "363") (name "unconnected-(U3-SENSOR_VN-Pad5)") (class "Default")
      (node (ref "U3") (pin "5") (pinfunction "SENSOR_VN_5") (pintype "input"))
    )
    (net (code "364") (name "unconnected-(U3-SENSOR_VP-Pad4)") (class "Default")
      (node (ref "U3") (pin "4") (pinfunction "SENSOR_VP_4") (pintype "input"))
    )
    (net (code "365") (name "unconnected-(U3-SHD{slash}SD2-Pad17)") (class "Default")
      (node (ref "U3") (pin "17") (pinfunction "SHD/SD2_17") (pintype "bidirectional"))
    )
    (net (code "366") (name "unconnected-(U3-SWP{slash}SD3-Pad18)") (class "Default")
      (node (ref "U3") (pin "18") (pinfunction "SWP/SD3_18") (pintype "bidirectional"))
    )
    (net (code "367") (name "unconnected-(X1B-S-Pad2)") (class "Default")
      (node (ref "X1") (pin "2") (pinfunction "S_2") (pintype "passive"))
    )
  )
)
